# BMS_Slave.net
KiCad netlist of a schematic drawn in Altium Designer
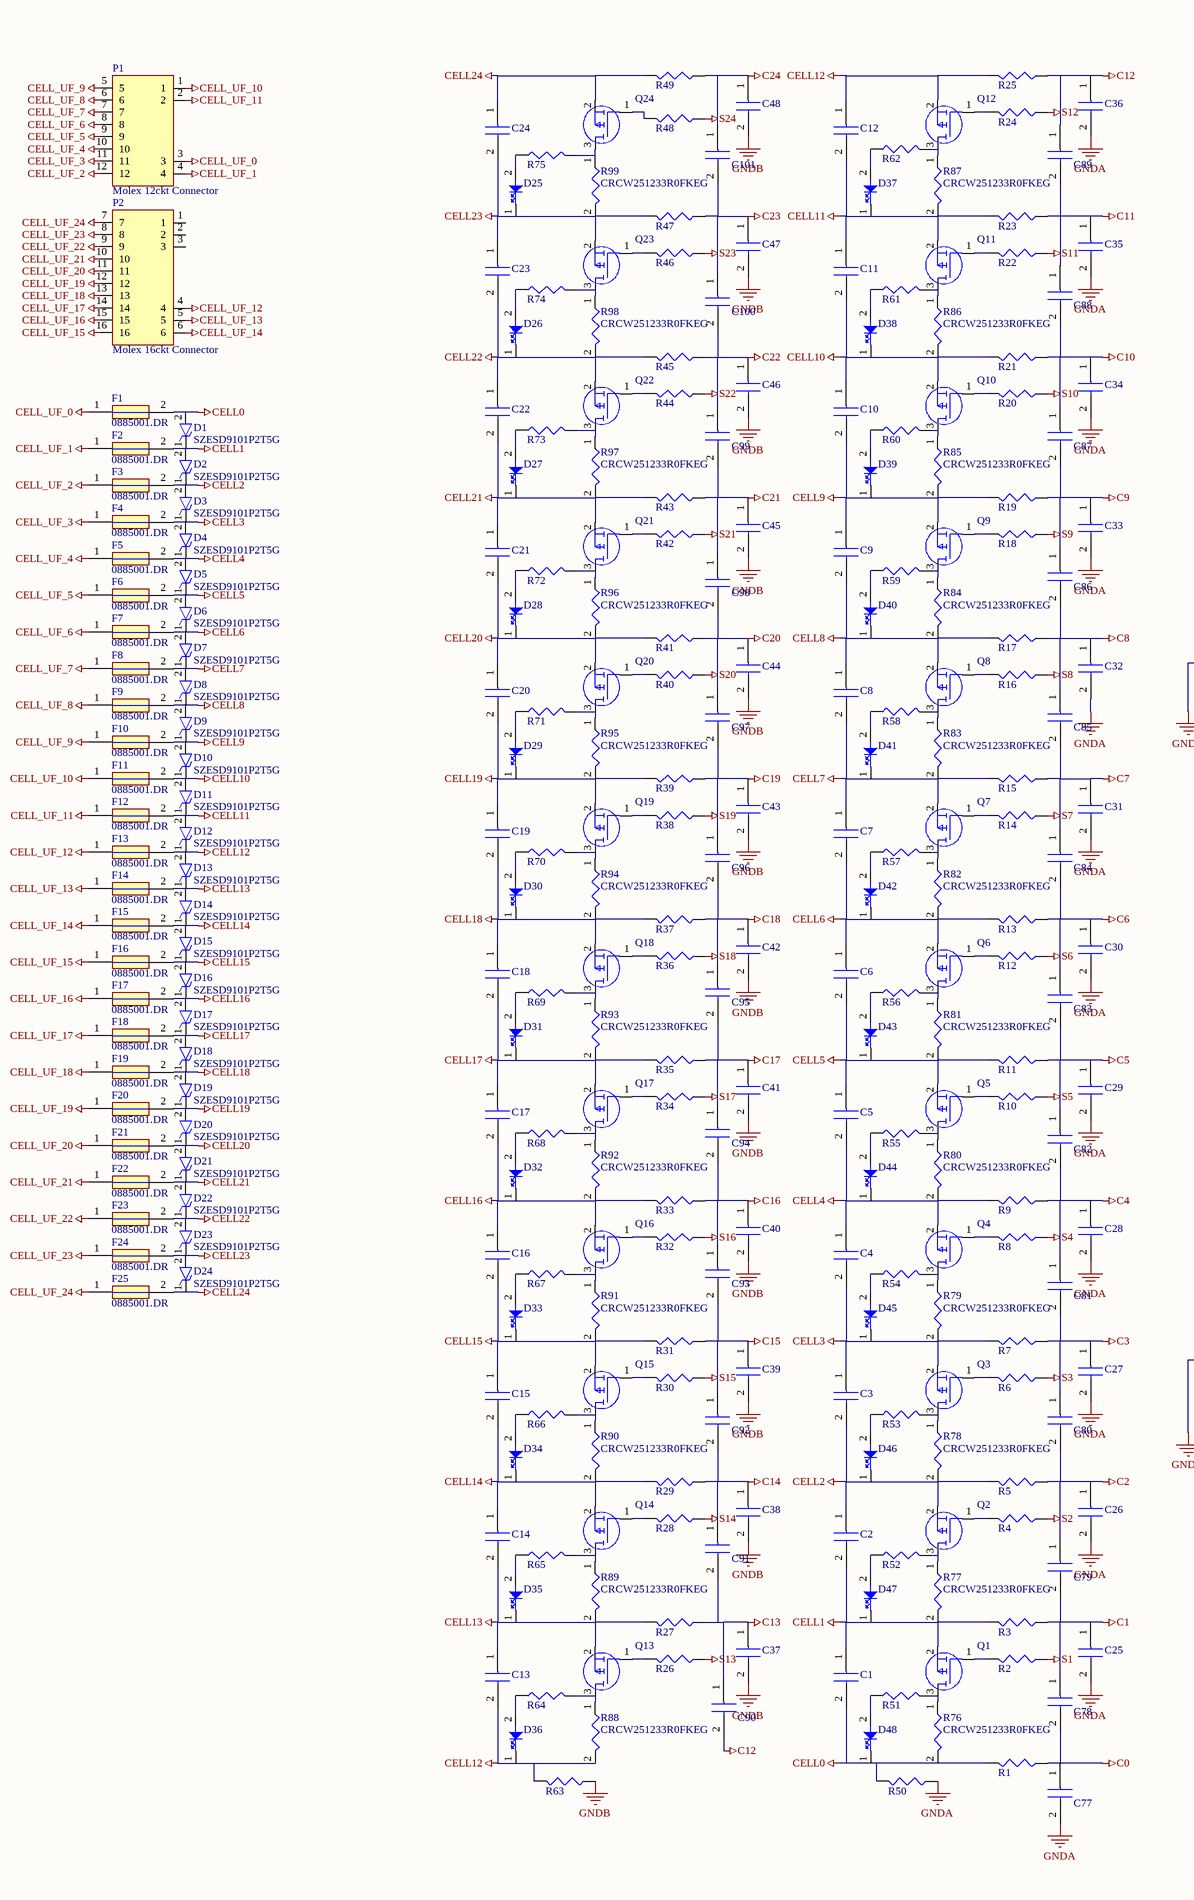
[diagram p0: BMS_Slave.SchDoc, left]
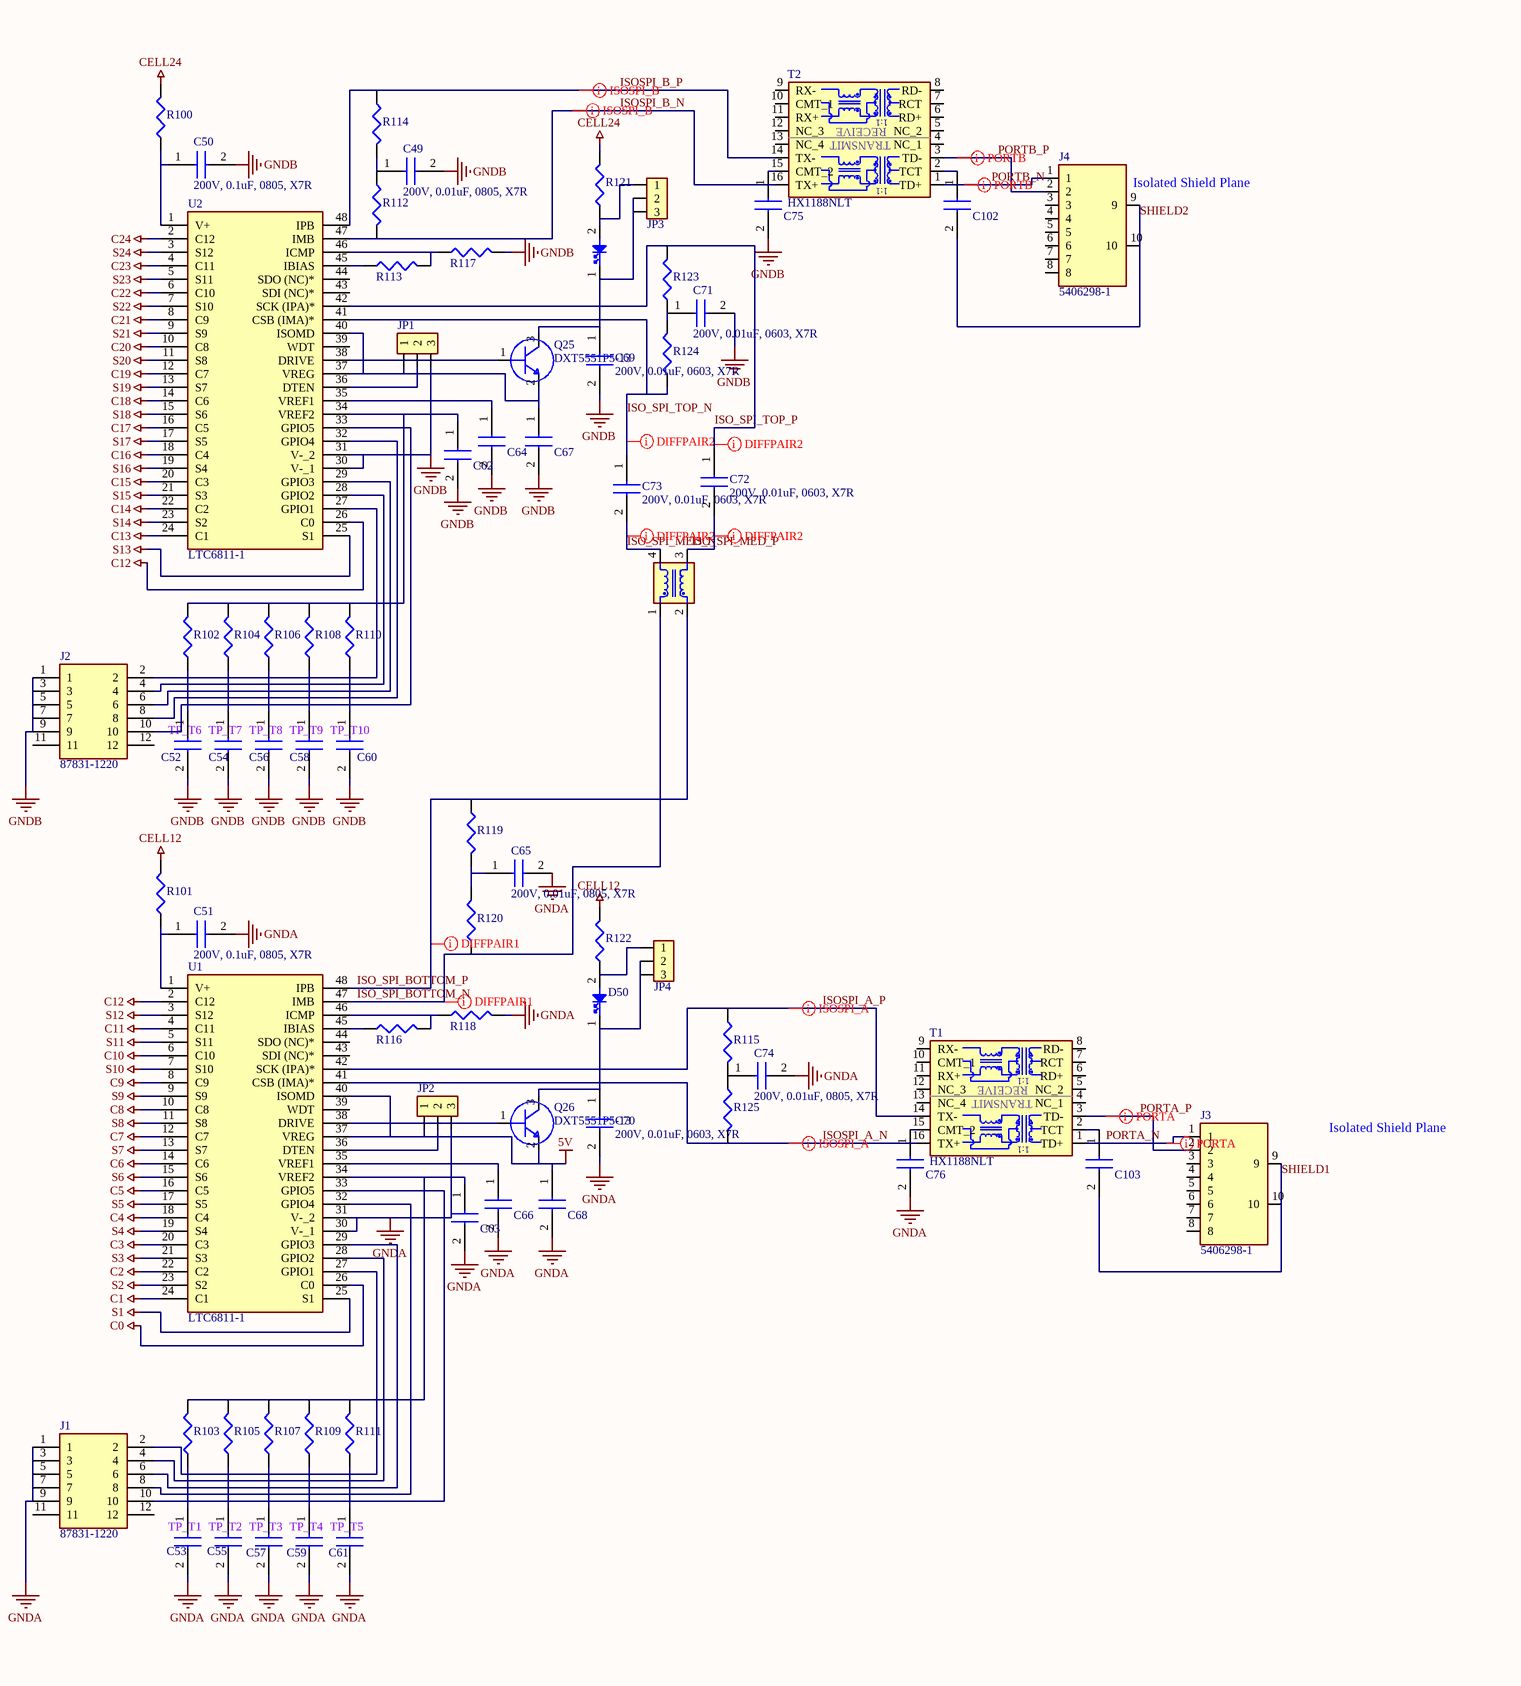
[diagram p1: BMS_Slave.SchDoc, right]

(export (version "E")
  (design (tool "Eeschema 10.0.6"))
  (components
    (comp (ref "C1")
      (value "25V 0.1uF X7R 0805 10%, MLCC")
      (footprint "CAPC2012X88N")
      (fields
        (field (name "MANUFACTURER_PART_NUMBER") "C0805C103K2RACTU")
        (field (name "MOUSER PART NUMBER") "80-C0805C103K2R")
      )
      (libsource (lib "BMS_Slave") (part "C0805C103K2RACTU"))
    )
    (comp (ref "C2")
      (value "25V 0.1uF X7R 0805 10%, MLCC")
      (footprint "CAPC2012X88N")
      (fields
        (field (name "MANUFACTURER_PART_NUMBER") "C0805C103K2RACTU")
        (field (name "MOUSER PART NUMBER") "80-C0805C103K2R")
      )
      (libsource (lib "BMS_Slave") (part "C0805C103K2RACTU"))
    )
    (comp (ref "C3")
      (value "25V 0.1uF X7R 0805 10%, MLCC")
      (footprint "CAPC2012X88N")
      (fields
        (field (name "MANUFACTURER_PART_NUMBER") "C0805C103K2RACTU")
        (field (name "MOUSER PART NUMBER") "80-C0805C103K2R")
      )
      (libsource (lib "BMS_Slave") (part "C0805C103K2RACTU"))
    )
    (comp (ref "C4")
      (value "25V 0.1uF X7R 0805 10%, MLCC")
      (footprint "CAPC2012X88N")
      (fields
        (field (name "MANUFACTURER_PART_NUMBER") "C0805C103K2RACTU")
        (field (name "MOUSER PART NUMBER") "80-C0805C103K2R")
      )
      (libsource (lib "BMS_Slave") (part "C0805C103K2RACTU"))
    )
    (comp (ref "C5")
      (value "25V 0.1uF X7R 0805 10%, MLCC")
      (footprint "CAPC2012X88N")
      (fields
        (field (name "MANUFACTURER_PART_NUMBER") "C0805C103K2RACTU")
        (field (name "MOUSER PART NUMBER") "80-C0805C103K2R")
      )
      (libsource (lib "BMS_Slave") (part "C0805C103K2RACTU"))
    )
    (comp (ref "C6")
      (value "25V 0.1uF X7R 0805 10%, MLCC")
      (footprint "CAPC2012X88N")
      (fields
        (field (name "MANUFACTURER_PART_NUMBER") "C0805C103K2RACTU")
        (field (name "MOUSER PART NUMBER") "80-C0805C103K2R")
      )
      (libsource (lib "BMS_Slave") (part "C0805C103K2RACTU"))
    )
    (comp (ref "C7")
      (value "25V 0.1uF X7R 0805 10%, MLCC")
      (footprint "CAPC2012X88N")
      (fields
        (field (name "MANUFACTURER_PART_NUMBER") "C0805C103K2RACTU")
        (field (name "MOUSER PART NUMBER") "80-C0805C103K2R")
      )
      (libsource (lib "BMS_Slave") (part "C0805C103K2RACTU"))
    )
    (comp (ref "C8")
      (value "25V 0.1uF X7R 0805 10%, MLCC")
      (footprint "CAPC2012X88N")
      (fields
        (field (name "MANUFACTURER_PART_NUMBER") "C0805C103K2RACTU")
        (field (name "MOUSER PART NUMBER") "80-C0805C103K2R")
      )
      (libsource (lib "BMS_Slave") (part "C0805C103K2RACTU"))
    )
    (comp (ref "C9")
      (value "25V 0.1uF X7R 0805 10%, MLCC")
      (footprint "CAPC2012X88N")
      (fields
        (field (name "MANUFACTURER_PART_NUMBER") "C0805C103K2RACTU")
        (field (name "MOUSER PART NUMBER") "80-C0805C103K2R")
      )
      (libsource (lib "BMS_Slave") (part "C0805C103K2RACTU"))
    )
    (comp (ref "C10")
      (value "25V 0.1uF X7R 0805 10%, MLCC")
      (footprint "CAPC2012X88N")
      (fields
        (field (name "MANUFACTURER_PART_NUMBER") "C0805C103K2RACTU")
        (field (name "MOUSER PART NUMBER") "80-C0805C103K2R")
      )
      (libsource (lib "BMS_Slave") (part "C0805C103K2RACTU"))
    )
    (comp (ref "C11")
      (value "25V 0.1uF X7R 0805 10%, MLCC")
      (footprint "CAPC2012X88N")
      (fields
        (field (name "MANUFACTURER_PART_NUMBER") "C0805C103K2RACTU")
        (field (name "MOUSER PART NUMBER") "80-C0805C103K2R")
      )
      (libsource (lib "BMS_Slave") (part "C0805C103K2RACTU"))
    )
    (comp (ref "C12")
      (value "25V 0.1uF X7R 0805 10%, MLCC")
      (footprint "CAPC2012X88N")
      (fields
        (field (name "MANUFACTURER_PART_NUMBER") "C0805C103K2RACTU")
        (field (name "MOUSER PART NUMBER") "80-C0805C103K2R")
      )
      (libsource (lib "BMS_Slave") (part "C0805C103K2RACTU"))
    )
    (comp (ref "C13")
      (value "25V 0.1uF X7R 0805 10%, MLCC")
      (footprint "CAPC2012X88N")
      (fields
        (field (name "MANUFACTURER_PART_NUMBER") "C0805C103K2RACTU")
        (field (name "MOUSER PART NUMBER") "80-C0805C103K2R")
      )
      (libsource (lib "BMS_Slave") (part "C0805C103K2RACTU"))
    )
    (comp (ref "C14")
      (value "25V 0.1uF X7R 0805 10%, MLCC")
      (footprint "CAPC2012X88N")
      (fields
        (field (name "MANUFACTURER_PART_NUMBER") "C0805C103K2RACTU")
        (field (name "MOUSER PART NUMBER") "80-C0805C103K2R")
      )
      (libsource (lib "BMS_Slave") (part "C0805C103K2RACTU"))
    )
    (comp (ref "C15")
      (value "25V 0.1uF X7R 0805 10%, MLCC")
      (footprint "CAPC2012X88N")
      (fields
        (field (name "MANUFACTURER_PART_NUMBER") "C0805C103K2RACTU")
        (field (name "MOUSER PART NUMBER") "80-C0805C103K2R")
      )
      (libsource (lib "BMS_Slave") (part "C0805C103K2RACTU"))
    )
    (comp (ref "C16")
      (value "25V 0.1uF X7R 0805 10%, MLCC")
      (footprint "CAPC2012X88N")
      (fields
        (field (name "MANUFACTURER_PART_NUMBER") "C0805C103K2RACTU")
        (field (name "MOUSER PART NUMBER") "80-C0805C103K2R")
      )
      (libsource (lib "BMS_Slave") (part "C0805C103K2RACTU"))
    )
    (comp (ref "C17")
      (value "25V 0.1uF X7R 0805 10%, MLCC")
      (footprint "CAPC2012X88N")
      (fields
        (field (name "MANUFACTURER_PART_NUMBER") "C0805C103K2RACTU")
        (field (name "MOUSER PART NUMBER") "80-C0805C103K2R")
      )
      (libsource (lib "BMS_Slave") (part "C0805C103K2RACTU"))
    )
    (comp (ref "C18")
      (value "25V 0.1uF X7R 0805 10%, MLCC")
      (footprint "CAPC2012X88N")
      (fields
        (field (name "MANUFACTURER_PART_NUMBER") "C0805C103K2RACTU")
        (field (name "MOUSER PART NUMBER") "80-C0805C103K2R")
      )
      (libsource (lib "BMS_Slave") (part "C0805C103K2RACTU"))
    )
    (comp (ref "C19")
      (value "25V 0.1uF X7R 0805 10%, MLCC")
      (footprint "CAPC2012X88N")
      (fields
        (field (name "MANUFACTURER_PART_NUMBER") "C0805C103K2RACTU")
        (field (name "MOUSER PART NUMBER") "80-C0805C103K2R")
      )
      (libsource (lib "BMS_Slave") (part "C0805C103K2RACTU"))
    )
    (comp (ref "C20")
      (value "25V 0.1uF X7R 0805 10%, MLCC")
      (footprint "CAPC2012X88N")
      (fields
        (field (name "MANUFACTURER_PART_NUMBER") "C0805C103K2RACTU")
        (field (name "MOUSER PART NUMBER") "80-C0805C103K2R")
      )
      (libsource (lib "BMS_Slave") (part "C0805C103K2RACTU"))
    )
    (comp (ref "C21")
      (value "25V 0.1uF X7R 0805 10%, MLCC")
      (footprint "CAPC2012X88N")
      (fields
        (field (name "MANUFACTURER_PART_NUMBER") "C0805C103K2RACTU")
        (field (name "MOUSER PART NUMBER") "80-C0805C103K2R")
      )
      (libsource (lib "BMS_Slave") (part "C0805C103K2RACTU"))
    )
    (comp (ref "C22")
      (value "25V 0.1uF X7R 0805 10%, MLCC")
      (footprint "CAPC2012X88N")
      (fields
        (field (name "MANUFACTURER_PART_NUMBER") "C0805C103K2RACTU")
        (field (name "MOUSER PART NUMBER") "80-C0805C103K2R")
      )
      (libsource (lib "BMS_Slave") (part "C0805C103K2RACTU"))
    )
    (comp (ref "C23")
      (value "25V 0.1uF X7R 0805 10%, MLCC")
      (footprint "CAPC2012X88N")
      (fields
        (field (name "MANUFACTURER_PART_NUMBER") "C0805C103K2RACTU")
        (field (name "MOUSER PART NUMBER") "80-C0805C103K2R")
      )
      (libsource (lib "BMS_Slave") (part "C0805C103K2RACTU"))
    )
    (comp (ref "C24")
      (value "25V 0.1uF X7R 0805 10%, MLCC")
      (footprint "CAPC2012X88N")
      (fields
        (field (name "MANUFACTURER_PART_NUMBER") "C0805C103K2RACTU")
        (field (name "MOUSER PART NUMBER") "80-C0805C103K2R")
      )
      (libsource (lib "BMS_Slave") (part "C0805C103K2RACTU"))
    )
    (comp (ref "C25")
      (value "200V, 0.01uF, 0805, X7R")
      (footprint "BMS_Slave:CAPC2012X88N")
      (description "Capacitor")
      (fields
        (field (name "MANUFACTURER_PART_NUMBER") "C0805C103K2RACTU")
        (field (name "MOUSER PART NUMBER") "80-C0805C103K2R")
      )
      (libsource (lib "BMS_Slave") (part "C0805C103K2RACTU"))
    )
    (comp (ref "C26")
      (value "200V, 0.01uF, 0805, X7R")
      (footprint "BMS_Slave:CAPC2012X88N")
      (description "Capacitor")
      (fields
        (field (name "MANUFACTURER_PART_NUMBER") "C0805C103K2RACTU")
        (field (name "MOUSER PART NUMBER") "80-C0805C103K2R")
      )
      (libsource (lib "BMS_Slave") (part "C0805C103K2RACTU"))
    )
    (comp (ref "C27")
      (value "200V, 0.01uF, 0805, X7R")
      (footprint "BMS_Slave:CAPC2012X88N")
      (description "Capacitor")
      (fields
        (field (name "MANUFACTURER_PART_NUMBER") "C0805C103K2RACTU")
        (field (name "MOUSER PART NUMBER") "80-C0805C103K2R")
      )
      (libsource (lib "BMS_Slave") (part "C0805C103K2RACTU"))
    )
    (comp (ref "C28")
      (value "200V, 0.01uF, 0805, X7R")
      (footprint "BMS_Slave:CAPC2012X88N")
      (description "Capacitor")
      (fields
        (field (name "MANUFACTURER_PART_NUMBER") "C0805C103K2RACTU")
        (field (name "MOUSER PART NUMBER") "80-C0805C103K2R")
      )
      (libsource (lib "BMS_Slave") (part "C0805C103K2RACTU"))
    )
    (comp (ref "C29")
      (value "200V, 0.01uF, 0805, X7R")
      (footprint "BMS_Slave:CAPC2012X88N")
      (description "Capacitor")
      (fields
        (field (name "MANUFACTURER_PART_NUMBER") "C0805C103K2RACTU")
        (field (name "MOUSER PART NUMBER") "80-C0805C103K2R")
      )
      (libsource (lib "BMS_Slave") (part "C0805C103K2RACTU"))
    )
    (comp (ref "C30")
      (value "200V, 0.01uF, 0805, X7R")
      (footprint "BMS_Slave:CAPC2012X88N")
      (description "Capacitor")
      (fields
        (field (name "MANUFACTURER_PART_NUMBER") "C0805C103K2RACTU")
        (field (name "MOUSER PART NUMBER") "80-C0805C103K2R")
      )
      (libsource (lib "BMS_Slave") (part "C0805C103K2RACTU"))
    )
    (comp (ref "C31")
      (value "200V, 0.01uF, 0805, X7R")
      (footprint "BMS_Slave:CAPC2012X88N")
      (description "Capacitor")
      (fields
        (field (name "MANUFACTURER_PART_NUMBER") "C0805C103K2RACTU")
        (field (name "MOUSER PART NUMBER") "80-C0805C103K2R")
      )
      (libsource (lib "BMS_Slave") (part "C0805C103K2RACTU"))
    )
    (comp (ref "C32")
      (value "200V, 0.01uF, 0805, X7R")
      (footprint "BMS_Slave:CAPC2012X88N")
      (description "Capacitor")
      (fields
        (field (name "MANUFACTURER_PART_NUMBER") "C0805C103K2RACTU")
        (field (name "MOUSER PART NUMBER") "80-C0805C103K2R")
      )
      (libsource (lib "BMS_Slave") (part "C0805C103K2RACTU"))
    )
    (comp (ref "C33")
      (value "200V, 0.01uF, 0805, X7R")
      (footprint "BMS_Slave:CAPC2012X88N")
      (description "Capacitor")
      (fields
        (field (name "MANUFACTURER_PART_NUMBER") "C0805C103K2RACTU")
        (field (name "MOUSER PART NUMBER") "80-C0805C103K2R")
      )
      (libsource (lib "BMS_Slave") (part "C0805C103K2RACTU"))
    )
    (comp (ref "C34")
      (value "200V, 0.01uF, 0805, X7R")
      (footprint "BMS_Slave:CAPC2012X88N")
      (description "Capacitor")
      (fields
        (field (name "MANUFACTURER_PART_NUMBER") "C0805C103K2RACTU")
        (field (name "MOUSER PART NUMBER") "80-C0805C103K2R")
      )
      (libsource (lib "BMS_Slave") (part "C0805C103K2RACTU"))
    )
    (comp (ref "C35")
      (value "200V, 0.01uF, 0805, X7R")
      (footprint "BMS_Slave:CAPC2012X88N")
      (description "Capacitor")
      (fields
        (field (name "MANUFACTURER_PART_NUMBER") "C0805C103K2RACTU")
        (field (name "MOUSER PART NUMBER") "80-C0805C103K2R")
      )
      (libsource (lib "BMS_Slave") (part "C0805C103K2RACTU"))
    )
    (comp (ref "C36")
      (value "200V, 0.01uF, 0805, X7R")
      (footprint "BMS_Slave:CAPC2012X88N")
      (description "Capacitor")
      (fields
        (field (name "MANUFACTURER_PART_NUMBER") "C0805C103K2RACTU")
        (field (name "MOUSER PART NUMBER") "80-C0805C103K2R")
      )
      (libsource (lib "BMS_Slave") (part "C0805C103K2RACTU"))
    )
    (comp (ref "C37")
      (value "200V, 0.01uF, 0805, X7R")
      (footprint "BMS_Slave:CAPC2012X88N")
      (description "Capacitor")
      (fields
        (field (name "MANUFACTURER_PART_NUMBER") "C0805C103K2RACTU")
        (field (name "MOUSER PART NUMBER") "80-C0805C103K2R")
      )
      (libsource (lib "BMS_Slave") (part "C0805C103K2RACTU"))
    )
    (comp (ref "C38")
      (value "200V, 0.01uF, 0805, X7R")
      (footprint "BMS_Slave:CAPC2012X88N")
      (description "Capacitor")
      (fields
        (field (name "MANUFACTURER_PART_NUMBER") "C0805C103K2RACTU")
        (field (name "MOUSER PART NUMBER") "80-C0805C103K2R")
      )
      (libsource (lib "BMS_Slave") (part "C0805C103K2RACTU"))
    )
    (comp (ref "C39")
      (value "200V, 0.01uF, 0805, X7R")
      (footprint "BMS_Slave:CAPC2012X88N")
      (description "Capacitor")
      (fields
        (field (name "MANUFACTURER_PART_NUMBER") "C0805C103K2RACTU")
        (field (name "MOUSER PART NUMBER") "80-C0805C103K2R")
      )
      (libsource (lib "BMS_Slave") (part "C0805C103K2RACTU"))
    )
    (comp (ref "C40")
      (value "200V, 0.01uF, 0805, X7R")
      (footprint "BMS_Slave:CAPC2012X88N")
      (description "Capacitor")
      (fields
        (field (name "MANUFACTURER_PART_NUMBER") "C0805C103K2RACTU")
        (field (name "MOUSER PART NUMBER") "80-C0805C103K2R")
      )
      (libsource (lib "BMS_Slave") (part "C0805C103K2RACTU"))
    )
    (comp (ref "C41")
      (value "200V, 0.01uF, 0805, X7R")
      (footprint "BMS_Slave:CAPC2012X88N")
      (description "Capacitor")
      (fields
        (field (name "MANUFACTURER_PART_NUMBER") "C0805C103K2RACTU")
        (field (name "MOUSER PART NUMBER") "80-C0805C103K2R")
      )
      (libsource (lib "BMS_Slave") (part "C0805C103K2RACTU"))
    )
    (comp (ref "C42")
      (value "200V, 0.01uF, 0805, X7R")
      (footprint "BMS_Slave:CAPC2012X88N")
      (description "Capacitor")
      (fields
        (field (name "MANUFACTURER_PART_NUMBER") "C0805C103K2RACTU")
        (field (name "MOUSER PART NUMBER") "80-C0805C103K2R")
      )
      (libsource (lib "BMS_Slave") (part "C0805C103K2RACTU"))
    )
    (comp (ref "C43")
      (value "200V, 0.01uF, 0805, X7R")
      (footprint "BMS_Slave:CAPC2012X88N")
      (description "Capacitor")
      (fields
        (field (name "MANUFACTURER_PART_NUMBER") "C0805C103K2RACTU")
        (field (name "MOUSER PART NUMBER") "80-C0805C103K2R")
      )
      (libsource (lib "BMS_Slave") (part "C0805C103K2RACTU"))
    )
    (comp (ref "C44")
      (value "200V, 0.01uF, 0805, X7R")
      (footprint "BMS_Slave:CAPC2012X88N")
      (description "Capacitor")
      (fields
        (field (name "MANUFACTURER_PART_NUMBER") "C0805C103K2RACTU")
        (field (name "MOUSER PART NUMBER") "80-C0805C103K2R")
      )
      (libsource (lib "BMS_Slave") (part "C0805C103K2RACTU"))
    )
    (comp (ref "C45")
      (value "200V, 0.01uF, 0805, X7R")
      (footprint "BMS_Slave:CAPC2012X88N")
      (description "Capacitor")
      (fields
        (field (name "MANUFACTURER_PART_NUMBER") "C0805C103K2RACTU")
        (field (name "MOUSER PART NUMBER") "80-C0805C103K2R")
      )
      (libsource (lib "BMS_Slave") (part "C0805C103K2RACTU"))
    )
    (comp (ref "C46")
      (value "200V, 0.01uF, 0805, X7R")
      (footprint "BMS_Slave:CAPC2012X88N")
      (description "Capacitor")
      (fields
        (field (name "MANUFACTURER_PART_NUMBER") "C0805C103K2RACTU")
        (field (name "MOUSER PART NUMBER") "80-C0805C103K2R")
      )
      (libsource (lib "BMS_Slave") (part "C0805C103K2RACTU"))
    )
    (comp (ref "C47")
      (value "200V, 0.01uF, 0805, X7R")
      (footprint "BMS_Slave:CAPC2012X88N")
      (description "Capacitor")
      (fields
        (field (name "MANUFACTURER_PART_NUMBER") "C0805C103K2RACTU")
        (field (name "MOUSER PART NUMBER") "80-C0805C103K2R")
      )
      (libsource (lib "BMS_Slave") (part "C0805C103K2RACTU"))
    )
    (comp (ref "C48")
      (value "200V, 0.01uF, 0805, X7R")
      (footprint "BMS_Slave:CAPC2012X88N")
      (description "Capacitor")
      (fields
        (field (name "MANUFACTURER_PART_NUMBER") "C0805C103K2RACTU")
        (field (name "MOUSER PART NUMBER") "80-C0805C103K2R")
      )
      (libsource (lib "BMS_Slave") (part "C0805C103K2RACTU"))
    )
    (comp (ref "C49")
      (value "200V, 0.01uF, 0805, X7R")
      (footprint "CAPC2012X88N")
      (description "Capacitor")
      (fields
        (field (name "MANUFACTURER_PART_NUMBER") "C0805C103K2RACTU")
        (field (name "MOUSER PART NUMBER") "80-C0805C103K2R")
      )
      (libsource (lib "BMS_Slave") (part "C0805C103K2RACTU"))
    )
    (comp (ref "C50")
      (value "200V, 0.1uF, 0805, X7R")
      (footprint "CAPC2012X88N")
      (description "Capacitor")
      (fields
        (field (name "MANUFACTURER_PART_NUMBER") "C0805C103K2RACTU")
        (field (name "MOUSER PART NUMBER") "80-C0805C103K2R")
      )
      (libsource (lib "BMS_Slave") (part "C0805C103K2RACTU"))
    )
    (comp (ref "C51")
      (value "200V, 0.1uF, 0805, X7R")
      (footprint "CAPC2012X88N")
      (description "Capacitor")
      (fields
        (field (name "MANUFACTURER_PART_NUMBER") "C0805C103K2RACTU")
        (field (name "MOUSER PART NUMBER") "80-C0805C103K2R")
      )
      (libsource (lib "BMS_Slave") (part "C0805C103K2RACTU"))
    )
    (comp (ref "C52")
      (value "CGA3E1X7R1E105K080AC")
      (footprint "BMS_Slave:CAPC1608X90N")
      (description "0603 25V 1uF X7R 10% AEC-Q200")
      (fields
        (field (name "MANUFACTURER_PART_NUMBER") "CGA3E1X7R1C105K080AC")
        (field (name "MOUSER PART NUMBER") "810-CGA3E1X7R1C105AC")
      )
      (libsource (lib "BMS_Slave") (part "CGA3E1X7R1E105K080AC"))
    )
    (comp (ref "C53")
      (value "CGA3E1X7R1E105K080AC")
      (footprint "BMS_Slave:CAPC1608X90N")
      (description "0603 25V 1uF X7R 10% AEC-Q200")
      (fields
        (field (name "MANUFACTURER_PART_NUMBER") "CGA3E1X7R1C105K080AC")
        (field (name "MOUSER PART NUMBER") "810-CGA3E1X7R1C105AC")
      )
      (libsource (lib "BMS_Slave") (part "CGA3E1X7R1E105K080AC"))
    )
    (comp (ref "C54")
      (value "CGA3E1X7R1E105K080AC")
      (footprint "BMS_Slave:CAPC1608X90N")
      (description "0603 25V 1uF X7R 10% AEC-Q200")
      (fields
        (field (name "MANUFACTURER_PART_NUMBER") "CGA3E1X7R1C105K080AC")
        (field (name "MOUSER PART NUMBER") "810-CGA3E1X7R1C105AC")
      )
      (libsource (lib "BMS_Slave") (part "CGA3E1X7R1E105K080AC"))
    )
    (comp (ref "C55")
      (value "CGA3E1X7R1E105K080AC")
      (footprint "BMS_Slave:CAPC1608X90N")
      (description "0603 25V 1uF X7R 10% AEC-Q200")
      (fields
        (field (name "MANUFACTURER_PART_NUMBER") "CGA3E1X7R1C105K080AC")
        (field (name "MOUSER PART NUMBER") "810-CGA3E1X7R1C105AC")
      )
      (libsource (lib "BMS_Slave") (part "CGA3E1X7R1E105K080AC"))
    )
    (comp (ref "C56")
      (value "CGA3E1X7R1E105K080AC")
      (footprint "BMS_Slave:CAPC1608X90N")
      (description "0603 25V 1uF X7R 10% AEC-Q200")
      (fields
        (field (name "MANUFACTURER_PART_NUMBER") "CGA3E1X7R1C105K080AC")
        (field (name "MOUSER PART NUMBER") "810-CGA3E1X7R1C105AC")
      )
      (libsource (lib "BMS_Slave") (part "CGA3E1X7R1E105K080AC"))
    )
    (comp (ref "C57")
      (value "CGA3E1X7R1E105K080AC")
      (footprint "BMS_Slave:CAPC1608X90N")
      (description "0603 25V 1uF X7R 10% AEC-Q200")
      (fields
        (field (name "MANUFACTURER_PART_NUMBER") "CGA3E1X7R1C105K080AC")
        (field (name "MOUSER PART NUMBER") "810-CGA3E1X7R1C105AC")
      )
      (libsource (lib "BMS_Slave") (part "CGA3E1X7R1E105K080AC"))
    )
    (comp (ref "C58")
      (value "CGA3E1X7R1E105K080AC")
      (footprint "BMS_Slave:CAPC1608X90N")
      (description "0603 25V 1uF X7R 10% AEC-Q200")
      (fields
        (field (name "MANUFACTURER_PART_NUMBER") "CGA3E1X7R1C105K080AC")
        (field (name "MOUSER PART NUMBER") "810-CGA3E1X7R1C105AC")
      )
      (libsource (lib "BMS_Slave") (part "CGA3E1X7R1E105K080AC"))
    )
    (comp (ref "C59")
      (value "CGA3E1X7R1E105K080AC")
      (footprint "BMS_Slave:CAPC1608X90N")
      (description "0603 25V 1uF X7R 10% AEC-Q200")
      (fields
        (field (name "MANUFACTURER_PART_NUMBER") "CGA3E1X7R1C105K080AC")
        (field (name "MOUSER PART NUMBER") "810-CGA3E1X7R1C105AC")
      )
      (libsource (lib "BMS_Slave") (part "CGA3E1X7R1E105K080AC"))
    )
    (comp (ref "C60")
      (value "CGA3E1X7R1E105K080AC")
      (footprint "BMS_Slave:CAPC1608X90N")
      (description "0603 25V 1uF X7R 10% AEC-Q200")
      (fields
        (field (name "MANUFACTURER_PART_NUMBER") "CGA3E1X7R1C105K080AC")
        (field (name "MOUSER PART NUMBER") "810-CGA3E1X7R1C105AC")
      )
      (libsource (lib "BMS_Slave") (part "CGA3E1X7R1E105K080AC"))
    )
    (comp (ref "C61")
      (value "CGA3E1X7R1E105K080AC")
      (footprint "BMS_Slave:CAPC1608X90N")
      (description "0603 25V 1uF X7R 10% AEC-Q200")
      (fields
        (field (name "MANUFACTURER_PART_NUMBER") "CGA3E1X7R1C105K080AC")
        (field (name "MOUSER PART NUMBER") "810-CGA3E1X7R1C105AC")
      )
      (libsource (lib "BMS_Slave") (part "CGA3E1X7R1E105K080AC"))
    )
    (comp (ref "C62")
      (value "CGA3E1X7R1E105K080AC")
      (footprint "BMS_Slave:CAPC1608X90N")
      (description "0603 25V 1uF X7R 10% AEC-Q200")
      (fields
        (field (name "MANUFACTURER_PART_NUMBER") "CGA3E1X7R1C105K080AC")
        (field (name "MOUSER PART NUMBER") "810-CGA3E1X7R1C105AC")
      )
      (libsource (lib "BMS_Slave") (part "CGA3E1X7R1E105K080AC"))
    )
    (comp (ref "C63")
      (value "CGA3E1X7R1E105K080AC")
      (footprint "BMS_Slave:CAPC1608X90N")
      (description "0603 25V 1uF X7R 10% AEC-Q200")
      (fields
        (field (name "MANUFACTURER_PART_NUMBER") "CGA3E1X7R1C105K080AC")
        (field (name "MOUSER PART NUMBER") "810-CGA3E1X7R1C105AC")
      )
      (libsource (lib "BMS_Slave") (part "CGA3E1X7R1E105K080AC"))
    )
    (comp (ref "C64")
      (value "CGA3E1X7R1E105K080AC")
      (footprint "BMS_Slave:CAPC1608X90N")
      (description "0603 25V 1uF X7R 10% AEC-Q200")
      (fields
        (field (name "MANUFACTURER_PART_NUMBER") "CGA3E1X7R1C105K080AC")
        (field (name "MOUSER PART NUMBER") "810-CGA3E1X7R1C105AC")
      )
      (libsource (lib "BMS_Slave") (part "CGA3E1X7R1E105K080AC"))
    )
    (comp (ref "C65")
      (value "200V, 0.01uF, 0805, X7R")
      (footprint "CAPC2012X88N")
      (description "Capacitor")
      (fields
        (field (name "MANUFACTURER_PART_NUMBER") "C0805C103K2RACTU")
        (field (name "MOUSER PART NUMBER") "80-C0805C103K2R")
      )
      (libsource (lib "BMS_Slave") (part "C0805C103K2RACTU"))
    )
    (comp (ref "C66")
      (value "CGA3E1X7R1E105K080AC")
      (footprint "BMS_Slave:CAPC1608X90N")
      (description "0603 25V 1uF X7R 10% AEC-Q200")
      (fields
        (field (name "MANUFACTURER_PART_NUMBER") "CGA3E1X7R1C105K080AC")
        (field (name "MOUSER PART NUMBER") "810-CGA3E1X7R1C105AC")
      )
      (libsource (lib "BMS_Slave") (part "CGA3E1X7R1E105K080AC"))
    )
    (comp (ref "C67")
      (value "CGA3E1X7R1E105K080AC")
      (footprint "BMS_Slave:CAPC1608X90N")
      (description "0603 25V 1uF X7R 10% AEC-Q200")
      (fields
        (field (name "MANUFACTURER_PART_NUMBER") "CGA3E1X7R1C105K080AC")
        (field (name "MOUSER PART NUMBER") "810-CGA3E1X7R1C105AC")
      )
      (libsource (lib "BMS_Slave") (part "CGA3E1X7R1E105K080AC"))
    )
    (comp (ref "C68")
      (value "CGA3E1X7R1E105K080AC")
      (footprint "BMS_Slave:CAPC1608X90N")
      (description "0603 25V 1uF X7R 10% AEC-Q200")
      (fields
        (field (name "MANUFACTURER_PART_NUMBER") "CGA3E1X7R1C105K080AC")
        (field (name "MOUSER PART NUMBER") "810-CGA3E1X7R1C105AC")
      )
      (libsource (lib "BMS_Slave") (part "CGA3E1X7R1E105K080AC"))
    )
    (comp (ref "C69")
      (value "200V, 0.01uF, 0603, X7R")
      (footprint "CAPC2012X88N")
      (description "Capacitor")
      (fields
        (field (name "MANUFACTURER_PART_NUMBER") "C0805C103K2RACTU")
        (field (name "MOUSER PART NUMBER") "80-C0805C103K2R")
      )
      (libsource (lib "BMS_Slave") (part "C0805C103K2RACTU"))
    )
    (comp (ref "C70")
      (value "200V, 0.01uF, 0603, X7R")
      (footprint "CAPC2012X88N")
      (description "Capacitor")
      (fields
        (field (name "MANUFACTURER_PART_NUMBER") "C0805C103K2RACTU")
        (field (name "MOUSER PART NUMBER") "80-C0805C103K2R")
      )
      (libsource (lib "BMS_Slave") (part "C0805C103K2RACTU"))
    )
    (comp (ref "C71")
      (value "200V, 0.01uF, 0603, X7R")
      (footprint "CAPC2012X88N")
      (description "Capacitor")
      (fields
        (field (name "MANUFACTURER_PART_NUMBER") "C0805C103K2RACTU")
        (field (name "MOUSER PART NUMBER") "80-C0805C103K2R")
      )
      (libsource (lib "BMS_Slave") (part "C0805C103K2RACTU"))
    )
    (comp (ref "C72")
      (value "200V, 0.01uF, 0603, X7R")
      (footprint "CAPC2012X88N")
      (description "Capacitor")
      (fields
        (field (name "MANUFACTURER_PART_NUMBER") "C0805C103K2RACTU")
        (field (name "MOUSER PART NUMBER") "80-C0805C103K2R")
      )
      (libsource (lib "BMS_Slave") (part "C0805C103K2RACTU"))
    )
    (comp (ref "C73")
      (value "200V, 0.01uF, 0603, X7R")
      (footprint "CAPC2012X88N")
      (description "Capacitor")
      (fields
        (field (name "MANUFACTURER_PART_NUMBER") "C0805C103K2RACTU")
        (field (name "MOUSER PART NUMBER") "80-C0805C103K2R")
      )
      (libsource (lib "BMS_Slave") (part "C0805C103K2RACTU"))
    )
    (comp (ref "C74")
      (value "200V, 0.01uF, 0805, X7R")
      (footprint "CAPC2012X88N")
      (description "Capacitor")
      (fields
        (field (name "MANUFACTURER_PART_NUMBER") "C0805C103K2RACTU")
        (field (name "MOUSER PART NUMBER") "80-C0805C103K2R")
      )
      (libsource (lib "BMS_Slave") (part "C0805C103K2RACTU"))
    )
    (comp (ref "C75")
      (value "200V, 0.01uF, 0603, X7R")
      (footprint "CAPC1608X85N")
      (description "200V, 0.01uF, 0603, X7R, 10%, Capacitor")
      (fields
        (field (name "MANUFACTURER_PART_NUMBER") "C0805X103M2RACAUTO")
        (field (name "MOUSER PART NUMBER") "80-C0805X103M2RAUTO")
      )
      (libsource (lib "BMS_Slave") (part "C0603C103K2RECTU"))
    )
    (comp (ref "C76")
      (value "200V, 0.01uF, 0603, X7R")
      (footprint "CAPC1608X85N")
      (description "200V, 0.01uF, 0603, X7R, 10%, Capacitor")
      (fields
        (field (name "MANUFACTURER_PART_NUMBER") "C0805X103M2RACAUTO")
        (field (name "MOUSER PART NUMBER") "80-C0805X103M2RAUTO")
      )
      (libsource (lib "BMS_Slave") (part "C0603C103K2RECTU_1"))
    )
    (comp (ref "C77")
      (value "200V, 0.01uF, 0603, X7R")
      (footprint "CAPC1608X85N")
      (description "200V, 0.01uF, 0603, X7R, 10%, Capacitor")
      (fields
        (field (name "MANUFACTURER_PART_NUMBER") "C0805X103M2RACAUTO")
        (field (name "MOUSER PART NUMBER") "80-C0805X103M2RAUTO")
      )
      (libsource (lib "BMS_Slave") (part "C0603C103K2RECTU"))
    )
    (comp (ref "C78")
      (value "200V, 0.01uF, 0603, X7R")
      (footprint "CAPC1608X85N")
      (description "200V, 0.01uF, 0603, X7R, 10%, Capacitor")
      (fields
        (field (name "MANUFACTURER_PART_NUMBER") "C0805X103M2RACAUTO")
        (field (name "MOUSER PART NUMBER") "80-C0805X103M2RAUTO")
      )
      (libsource (lib "BMS_Slave") (part "C0603C103K2RECTU"))
    )
    (comp (ref "C79")
      (value "200V, 0.01uF, 0603, X7R")
      (footprint "CAPC1608X85N")
      (description "200V, 0.01uF, 0603, X7R, 10%, Capacitor")
      (fields
        (field (name "MANUFACTURER_PART_NUMBER") "C0805X103M2RACAUTO")
        (field (name "MOUSER PART NUMBER") "80-C0805X103M2RAUTO")
      )
      (libsource (lib "BMS_Slave") (part "C0603C103K2RECTU"))
    )
    (comp (ref "C80")
      (value "200V, 0.01uF, 0603, X7R")
      (footprint "CAPC1608X85N")
      (description "200V, 0.01uF, 0603, X7R, 10%, Capacitor")
      (fields
        (field (name "MANUFACTURER_PART_NUMBER") "C0805X103M2RACAUTO")
        (field (name "MOUSER PART NUMBER") "80-C0805X103M2RAUTO")
      )
      (libsource (lib "BMS_Slave") (part "C0603C103K2RECTU"))
    )
    (comp (ref "C81")
      (value "200V, 0.01uF, 0603, X7R")
      (footprint "CAPC1608X85N")
      (description "200V, 0.01uF, 0603, X7R, 10%, Capacitor")
      (fields
        (field (name "MANUFACTURER_PART_NUMBER") "C0805X103M2RACAUTO")
        (field (name "MOUSER PART NUMBER") "80-C0805X103M2RAUTO")
      )
      (libsource (lib "BMS_Slave") (part "C0603C103K2RECTU"))
    )
    (comp (ref "C82")
      (value "200V, 0.01uF, 0603, X7R")
      (footprint "CAPC1608X85N")
      (description "200V, 0.01uF, 0603, X7R, 10%, Capacitor")
      (fields
        (field (name "MANUFACTURER_PART_NUMBER") "C0805X103M2RACAUTO")
        (field (name "MOUSER PART NUMBER") "80-C0805X103M2RAUTO")
      )
      (libsource (lib "BMS_Slave") (part "C0603C103K2RECTU"))
    )
    (comp (ref "C83")
      (value "200V, 0.01uF, 0603, X7R")
      (footprint "CAPC1608X85N")
      (description "200V, 0.01uF, 0603, X7R, 10%, Capacitor")
      (fields
        (field (name "MANUFACTURER_PART_NUMBER") "C0805X103M2RACAUTO")
        (field (name "MOUSER PART NUMBER") "80-C0805X103M2RAUTO")
      )
      (libsource (lib "BMS_Slave") (part "C0603C103K2RECTU"))
    )
    (comp (ref "C84")
      (value "200V, 0.01uF, 0603, X7R")
      (footprint "CAPC1608X85N")
      (description "200V, 0.01uF, 0603, X7R, 10%, Capacitor")
      (fields
        (field (name "MANUFACTURER_PART_NUMBER") "C0805X103M2RACAUTO")
        (field (name "MOUSER PART NUMBER") "80-C0805X103M2RAUTO")
      )
      (libsource (lib "BMS_Slave") (part "C0603C103K2RECTU"))
    )
    (comp (ref "C85")
      (value "200V, 0.01uF, 0603, X7R")
      (footprint "CAPC1608X85N")
      (description "200V, 0.01uF, 0603, X7R, 10%, Capacitor")
      (fields
        (field (name "MANUFACTURER_PART_NUMBER") "C0805X103M2RACAUTO")
        (field (name "MOUSER PART NUMBER") "80-C0805X103M2RAUTO")
      )
      (libsource (lib "BMS_Slave") (part "C0603C103K2RECTU"))
    )
    (comp (ref "C86")
      (value "200V, 0.01uF, 0603, X7R")
      (footprint "CAPC1608X85N")
      (description "200V, 0.01uF, 0603, X7R, 10%, Capacitor")
      (fields
        (field (name "MANUFACTURER_PART_NUMBER") "C0805X103M2RACAUTO")
        (field (name "MOUSER PART NUMBER") "80-C0805X103M2RAUTO")
      )
      (libsource (lib "BMS_Slave") (part "C0603C103K2RECTU"))
    )
    (comp (ref "C87")
      (value "200V, 0.01uF, 0603, X7R")
      (footprint "CAPC1608X85N")
      (description "200V, 0.01uF, 0603, X7R, 10%, Capacitor")
      (fields
        (field (name "MANUFACTURER_PART_NUMBER") "C0805X103M2RACAUTO")
        (field (name "MOUSER PART NUMBER") "80-C0805X103M2RAUTO")
      )
      (libsource (lib "BMS_Slave") (part "C0603C103K2RECTU"))
    )
    (comp (ref "C88")
      (value "200V, 0.01uF, 0603, X7R")
      (footprint "CAPC1608X85N")
      (description "200V, 0.01uF, 0603, X7R, 10%, Capacitor")
      (fields
        (field (name "MANUFACTURER_PART_NUMBER") "C0805X103M2RACAUTO")
        (field (name "MOUSER PART NUMBER") "80-C0805X103M2RAUTO")
      )
      (libsource (lib "BMS_Slave") (part "C0603C103K2RECTU"))
    )
    (comp (ref "C89")
      (value "200V, 0.01uF, 0603, X7R")
      (footprint "CAPC1608X85N")
      (description "200V, 0.01uF, 0603, X7R, 10%, Capacitor")
      (fields
        (field (name "MANUFACTURER_PART_NUMBER") "C0805X103M2RACAUTO")
        (field (name "MOUSER PART NUMBER") "80-C0805X103M2RAUTO")
      )
      (libsource (lib "BMS_Slave") (part "C0603C103K2RECTU"))
    )
    (comp (ref "C90")
      (value "200V, 0.01uF, 0603, X7R")
      (footprint "CAPC1608X85N")
      (description "200V, 0.01uF, 0603, X7R, 10%, Capacitor")
      (fields
        (field (name "MANUFACTURER_PART_NUMBER") "C0805X103M2RACAUTO")
        (field (name "MOUSER PART NUMBER") "80-C0805X103M2RAUTO")
      )
      (libsource (lib "BMS_Slave") (part "C0603C103K2RECTU"))
    )
    (comp (ref "C91")
      (value "200V, 0.01uF, 0603, X7R")
      (footprint "CAPC1608X85N")
      (description "200V, 0.01uF, 0603, X7R, 10%, Capacitor")
      (fields
        (field (name "MANUFACTURER_PART_NUMBER") "C0805X103M2RACAUTO")
        (field (name "MOUSER PART NUMBER") "80-C0805X103M2RAUTO")
      )
      (libsource (lib "BMS_Slave") (part "C0603C103K2RECTU"))
    )
    (comp (ref "C92")
      (value "200V, 0.01uF, 0603, X7R")
      (footprint "CAPC1608X85N")
      (description "200V, 0.01uF, 0603, X7R, 10%, Capacitor")
      (fields
        (field (name "MANUFACTURER_PART_NUMBER") "C0805X103M2RACAUTO")
        (field (name "MOUSER PART NUMBER") "80-C0805X103M2RAUTO")
      )
      (libsource (lib "BMS_Slave") (part "C0603C103K2RECTU"))
    )
    (comp (ref "C93")
      (value "200V, 0.01uF, 0603, X7R")
      (footprint "CAPC1608X85N")
      (description "200V, 0.01uF, 0603, X7R, 10%, Capacitor")
      (fields
        (field (name "MANUFACTURER_PART_NUMBER") "C0805X103M2RACAUTO")
        (field (name "MOUSER PART NUMBER") "80-C0805X103M2RAUTO")
      )
      (libsource (lib "BMS_Slave") (part "C0603C103K2RECTU"))
    )
    (comp (ref "C94")
      (value "200V, 0.01uF, 0603, X7R")
      (footprint "CAPC1608X85N")
      (description "200V, 0.01uF, 0603, X7R, 10%, Capacitor")
      (fields
        (field (name "MANUFACTURER_PART_NUMBER") "C0805X103M2RACAUTO")
        (field (name "MOUSER PART NUMBER") "80-C0805X103M2RAUTO")
      )
      (libsource (lib "BMS_Slave") (part "C0603C103K2RECTU"))
    )
    (comp (ref "C95")
      (value "200V, 0.01uF, 0603, X7R")
      (footprint "CAPC1608X85N")
      (description "200V, 0.01uF, 0603, X7R, 10%, Capacitor")
      (fields
        (field (name "MANUFACTURER_PART_NUMBER") "C0805X103M2RACAUTO")
        (field (name "MOUSER PART NUMBER") "80-C0805X103M2RAUTO")
      )
      (libsource (lib "BMS_Slave") (part "C0603C103K2RECTU"))
    )
    (comp (ref "C96")
      (value "200V, 0.01uF, 0603, X7R")
      (footprint "CAPC1608X85N")
      (description "200V, 0.01uF, 0603, X7R, 10%, Capacitor")
      (fields
        (field (name "MANUFACTURER_PART_NUMBER") "C0805X103M2RACAUTO")
        (field (name "MOUSER PART NUMBER") "80-C0805X103M2RAUTO")
      )
      (libsource (lib "BMS_Slave") (part "C0603C103K2RECTU"))
    )
    (comp (ref "C97")
      (value "200V, 0.01uF, 0603, X7R")
      (footprint "CAPC1608X85N")
      (description "200V, 0.01uF, 0603, X7R, 10%, Capacitor")
      (fields
        (field (name "MANUFACTURER_PART_NUMBER") "C0805X103M2RACAUTO")
        (field (name "MOUSER PART NUMBER") "80-C0805X103M2RAUTO")
      )
      (libsource (lib "BMS_Slave") (part "C0603C103K2RECTU"))
    )
    (comp (ref "C98")
      (value "200V, 0.01uF, 0603, X7R")
      (footprint "CAPC1608X85N")
      (description "200V, 0.01uF, 0603, X7R, 10%, Capacitor")
      (fields
        (field (name "MANUFACTURER_PART_NUMBER") "C0805X103M2RACAUTO")
        (field (name "MOUSER PART NUMBER") "80-C0805X103M2RAUTO")
      )
      (libsource (lib "BMS_Slave") (part "C0603C103K2RECTU"))
    )
    (comp (ref "C99")
      (value "200V, 0.01uF, 0603, X7R")
      (footprint "CAPC1608X85N")
      (description "200V, 0.01uF, 0603, X7R, 10%, Capacitor")
      (fields
        (field (name "MANUFACTURER_PART_NUMBER") "C0805X103M2RACAUTO")
        (field (name "MOUSER PART NUMBER") "80-C0805X103M2RAUTO")
      )
      (libsource (lib "BMS_Slave") (part "C0603C103K2RECTU"))
    )
    (comp (ref "C100")
      (value "200V, 0.01uF, 0603, X7R")
      (footprint "CAPC1608X85N")
      (description "200V, 0.01uF, 0603, X7R, 10%, Capacitor")
      (fields
        (field (name "MANUFACTURER_PART_NUMBER") "C0805X103M2RACAUTO")
        (field (name "MOUSER PART NUMBER") "80-C0805X103M2RAUTO")
      )
      (libsource (lib "BMS_Slave") (part "C0603C103K2RECTU"))
    )
    (comp (ref "C101")
      (value "200V, 0.01uF, 0603, X7R")
      (footprint "CAPC1608X85N")
      (description "200V, 0.01uF, 0603, X7R, 10%, Capacitor")
      (fields
        (field (name "MANUFACTURER_PART_NUMBER") "C0805X103M2RACAUTO")
        (field (name "MOUSER PART NUMBER") "80-C0805X103M2RAUTO")
      )
      (libsource (lib "BMS_Slave") (part "C0603C103K2RECTU"))
    )
    (comp (ref "C102")
      (value "200V, 0.01uF, 0603, X7R")
      (footprint "CAPC1608X85N")
      (description "200V, 0.01uF, 0603, X7R, 10%, Capacitor")
      (fields
        (field (name "MANUFACTURER_PART_NUMBER") "C0805X103M2RACAUTO")
        (field (name "MOUSER PART NUMBER") "80-C0805X103M2RAUTO")
      )
      (libsource (lib "BMS_Slave") (part "C0603C103K2RECTU"))
    )
    (comp (ref "C103")
      (value "200V, 0.01uF, 0603, X7R")
      (footprint "CAPC1608X85N")
      (description "200V, 0.01uF, 0603, X7R, 10%, Capacitor")
      (fields
        (field (name "MANUFACTURER_PART_NUMBER") "C0805X103M2RACAUTO")
        (field (name "MOUSER PART NUMBER") "80-C0805X103M2RAUTO")
      )
      (libsource (lib "BMS_Slave") (part "C0603C103K2RECTU"))
    )
    (comp (ref "D1")
      (value "SZESD9101P2T5G")
      (footprint "SODFL1006X40N")
      (description "TVS Diode (Uni-directional)")
      (fields (field (name "MOUSER PART NUMBER") "863-SZESD9101P2T5G"))
      (libsource (lib "BMS_Slave") (part "SZESD9101P2T5G"))
    )
    (comp (ref "D2")
      (value "SZESD9101P2T5G")
      (footprint "SODFL1006X40N")
      (description "TVS Diode (Uni-directional)")
      (fields (field (name "MOUSER PART NUMBER") "863-SZESD9101P2T5G"))
      (libsource (lib "BMS_Slave") (part "SZESD9101P2T5G"))
    )
    (comp (ref "D3")
      (value "SZESD9101P2T5G")
      (footprint "SODFL1006X40N")
      (description "TVS Diode (Uni-directional)")
      (fields (field (name "MOUSER PART NUMBER") "863-SZESD9101P2T5G"))
      (libsource (lib "BMS_Slave") (part "SZESD9101P2T5G"))
    )
    (comp (ref "D4")
      (value "SZESD9101P2T5G")
      (footprint "SODFL1006X40N")
      (description "TVS Diode (Uni-directional)")
      (fields (field (name "MOUSER PART NUMBER") "863-SZESD9101P2T5G"))
      (libsource (lib "BMS_Slave") (part "SZESD9101P2T5G"))
    )
    (comp (ref "D5")
      (value "SZESD9101P2T5G")
      (footprint "SODFL1006X40N")
      (description "TVS Diode (Uni-directional)")
      (fields (field (name "MOUSER PART NUMBER") "863-SZESD9101P2T5G"))
      (libsource (lib "BMS_Slave") (part "SZESD9101P2T5G"))
    )
    (comp (ref "D6")
      (value "SZESD9101P2T5G")
      (footprint "SODFL1006X40N")
      (description "TVS Diode (Uni-directional)")
      (fields (field (name "MOUSER PART NUMBER") "863-SZESD9101P2T5G"))
      (libsource (lib "BMS_Slave") (part "SZESD9101P2T5G"))
    )
    (comp (ref "D7")
      (value "SZESD9101P2T5G")
      (footprint "SODFL1006X40N")
      (description "TVS Diode (Uni-directional)")
      (fields (field (name "MOUSER PART NUMBER") "863-SZESD9101P2T5G"))
      (libsource (lib "BMS_Slave") (part "SZESD9101P2T5G"))
    )
    (comp (ref "D8")
      (value "SZESD9101P2T5G")
      (footprint "SODFL1006X40N")
      (description "TVS Diode (Uni-directional)")
      (fields (field (name "MOUSER PART NUMBER") "863-SZESD9101P2T5G"))
      (libsource (lib "BMS_Slave") (part "SZESD9101P2T5G"))
    )
    (comp (ref "D9")
      (value "SZESD9101P2T5G")
      (footprint "SODFL1006X40N")
      (description "TVS Diode (Uni-directional)")
      (fields (field (name "MOUSER PART NUMBER") "863-SZESD9101P2T5G"))
      (libsource (lib "BMS_Slave") (part "SZESD9101P2T5G"))
    )
    (comp (ref "D10")
      (value "SZESD9101P2T5G")
      (footprint "SODFL1006X40N")
      (description "TVS Diode (Uni-directional)")
      (fields (field (name "MOUSER PART NUMBER") "863-SZESD9101P2T5G"))
      (libsource (lib "BMS_Slave") (part "SZESD9101P2T5G"))
    )
    (comp (ref "D11")
      (value "SZESD9101P2T5G")
      (footprint "SODFL1006X40N")
      (description "TVS Diode (Uni-directional)")
      (fields (field (name "MOUSER PART NUMBER") "863-SZESD9101P2T5G"))
      (libsource (lib "BMS_Slave") (part "SZESD9101P2T5G"))
    )
    (comp (ref "D12")
      (value "SZESD9101P2T5G")
      (footprint "SODFL1006X40N")
      (description "TVS Diode (Uni-directional)")
      (fields (field (name "MOUSER PART NUMBER") "863-SZESD9101P2T5G"))
      (libsource (lib "BMS_Slave") (part "SZESD9101P2T5G"))
    )
    (comp (ref "D13")
      (value "SZESD9101P2T5G")
      (footprint "SODFL1006X40N")
      (description "TVS Diode (Uni-directional)")
      (fields (field (name "MOUSER PART NUMBER") "863-SZESD9101P2T5G"))
      (libsource (lib "BMS_Slave") (part "SZESD9101P2T5G"))
    )
    (comp (ref "D14")
      (value "SZESD9101P2T5G")
      (footprint "SODFL1006X40N")
      (description "TVS Diode (Uni-directional)")
      (fields (field (name "MOUSER PART NUMBER") "863-SZESD9101P2T5G"))
      (libsource (lib "BMS_Slave") (part "SZESD9101P2T5G"))
    )
    (comp (ref "D15")
      (value "SZESD9101P2T5G")
      (footprint "SODFL1006X40N")
      (description "TVS Diode (Uni-directional)")
      (fields (field (name "MOUSER PART NUMBER") "863-SZESD9101P2T5G"))
      (libsource (lib "BMS_Slave") (part "SZESD9101P2T5G"))
    )
    (comp (ref "D16")
      (value "SZESD9101P2T5G")
      (footprint "SODFL1006X40N")
      (description "TVS Diode (Uni-directional)")
      (fields (field (name "MOUSER PART NUMBER") "863-SZESD9101P2T5G"))
      (libsource (lib "BMS_Slave") (part "SZESD9101P2T5G"))
    )
    (comp (ref "D17")
      (value "SZESD9101P2T5G")
      (footprint "SODFL1006X40N")
      (description "TVS Diode (Uni-directional)")
      (fields (field (name "MOUSER PART NUMBER") "863-SZESD9101P2T5G"))
      (libsource (lib "BMS_Slave") (part "SZESD9101P2T5G"))
    )
    (comp (ref "D18")
      (value "SZESD9101P2T5G")
      (footprint "SODFL1006X40N")
      (description "TVS Diode (Uni-directional)")
      (fields (field (name "MOUSER PART NUMBER") "863-SZESD9101P2T5G"))
      (libsource (lib "BMS_Slave") (part "SZESD9101P2T5G"))
    )
    (comp (ref "D19")
      (value "SZESD9101P2T5G")
      (footprint "SODFL1006X40N")
      (description "TVS Diode (Uni-directional)")
      (fields (field (name "MOUSER PART NUMBER") "863-SZESD9101P2T5G"))
      (libsource (lib "BMS_Slave") (part "SZESD9101P2T5G"))
    )
    (comp (ref "D20")
      (value "SZESD9101P2T5G")
      (footprint "SODFL1006X40N")
      (description "TVS Diode (Uni-directional)")
      (fields (field (name "MOUSER PART NUMBER") "863-SZESD9101P2T5G"))
      (libsource (lib "BMS_Slave") (part "SZESD9101P2T5G"))
    )
    (comp (ref "D21")
      (value "SZESD9101P2T5G")
      (footprint "SODFL1006X40N")
      (description "TVS Diode (Uni-directional)")
      (fields (field (name "MOUSER PART NUMBER") "863-SZESD9101P2T5G"))
      (libsource (lib "BMS_Slave") (part "SZESD9101P2T5G"))
    )
    (comp (ref "D22")
      (value "SZESD9101P2T5G")
      (footprint "SODFL1006X40N")
      (description "TVS Diode (Uni-directional)")
      (fields (field (name "MOUSER PART NUMBER") "863-SZESD9101P2T5G"))
      (libsource (lib "BMS_Slave") (part "SZESD9101P2T5G"))
    )
    (comp (ref "D23")
      (value "SZESD9101P2T5G")
      (footprint "SODFL1006X40N")
      (description "TVS Diode (Uni-directional)")
      (fields (field (name "MOUSER PART NUMBER") "863-SZESD9101P2T5G"))
      (libsource (lib "BMS_Slave") (part "SZESD9101P2T5G"))
    )
    (comp (ref "D24")
      (value "SZESD9101P2T5G")
      (footprint "SODFL1006X40N")
      (description "TVS Diode (Uni-directional)")
      (fields (field (name "MOUSER PART NUMBER") "863-SZESD9101P2T5G"))
      (libsource (lib "BMS_Slave") (part "SZESD9101P2T5G"))
    )
    (comp (ref "D25")
      (value "SML-210VTT86")
      (footprint "SamacSys:LEDC2012X80N")
      (description "LED")
      (fields
        (field (name "MOUSER PART NUMBER") "755-SML-210VTT86")
        (field (name "RS PART NUMBER") "7007893P")
      )
      (libsource (lib "BMS_Slave") (part "SML-210VTT86"))
    )
    (comp (ref "D26")
      (value "SML-210VTT86")
      (footprint "SamacSys:LEDC2012X80N")
      (description "LED")
      (fields
        (field (name "MOUSER PART NUMBER") "755-SML-210VTT86")
        (field (name "RS PART NUMBER") "7007893P")
      )
      (libsource (lib "BMS_Slave") (part "SML-210VTT86"))
    )
    (comp (ref "D27")
      (value "SML-210VTT86")
      (footprint "SamacSys:LEDC2012X80N")
      (description "LED")
      (fields
        (field (name "MOUSER PART NUMBER") "755-SML-210VTT86")
        (field (name "RS PART NUMBER") "7007893P")
      )
      (libsource (lib "BMS_Slave") (part "SML-210VTT86"))
    )
    (comp (ref "D28")
      (value "SML-210VTT86")
      (footprint "SamacSys:LEDC2012X80N")
      (description "LED")
      (fields
        (field (name "MOUSER PART NUMBER") "755-SML-210VTT86")
        (field (name "RS PART NUMBER") "7007893P")
      )
      (libsource (lib "BMS_Slave") (part "SML-210VTT86"))
    )
    (comp (ref "D29")
      (value "SML-210VTT86")
      (footprint "SamacSys:LEDC2012X80N")
      (description "LED")
      (fields
        (field (name "MOUSER PART NUMBER") "755-SML-210VTT86")
        (field (name "RS PART NUMBER") "7007893P")
      )
      (libsource (lib "BMS_Slave") (part "SML-210VTT86"))
    )
    (comp (ref "D30")
      (value "SML-210VTT86")
      (footprint "SamacSys:LEDC2012X80N")
      (description "LED")
      (fields
        (field (name "MOUSER PART NUMBER") "755-SML-210VTT86")
        (field (name "RS PART NUMBER") "7007893P")
      )
      (libsource (lib "BMS_Slave") (part "SML-210VTT86"))
    )
    (comp (ref "D31")
      (value "SML-210VTT86")
      (footprint "SamacSys:LEDC2012X80N")
      (description "LED")
      (fields
        (field (name "MOUSER PART NUMBER") "755-SML-210VTT86")
        (field (name "RS PART NUMBER") "7007893P")
      )
      (libsource (lib "BMS_Slave") (part "SML-210VTT86"))
    )
    (comp (ref "D32")
      (value "SML-210VTT86")
      (footprint "SamacSys:LEDC2012X80N")
      (description "LED")
      (fields
        (field (name "MOUSER PART NUMBER") "755-SML-210VTT86")
        (field (name "RS PART NUMBER") "7007893P")
      )
      (libsource (lib "BMS_Slave") (part "SML-210VTT86"))
    )
    (comp (ref "D33")
      (value "SML-210VTT86")
      (footprint "SamacSys:LEDC2012X80N")
      (description "LED")
      (fields
        (field (name "MOUSER PART NUMBER") "755-SML-210VTT86")
        (field (name "RS PART NUMBER") "7007893P")
      )
      (libsource (lib "BMS_Slave") (part "SML-210VTT86"))
    )
    (comp (ref "D34")
      (value "SML-210VTT86")
      (footprint "SamacSys:LEDC2012X80N")
      (description "LED")
      (fields
        (field (name "MOUSER PART NUMBER") "755-SML-210VTT86")
        (field (name "RS PART NUMBER") "7007893P")
      )
      (libsource (lib "BMS_Slave") (part "SML-210VTT86"))
    )
    (comp (ref "D35")
      (value "SML-210VTT86")
      (footprint "SamacSys:LEDC2012X80N")
      (description "LED")
      (fields
        (field (name "MOUSER PART NUMBER") "755-SML-210VTT86")
        (field (name "RS PART NUMBER") "7007893P")
      )
      (libsource (lib "BMS_Slave") (part "SML-210VTT86"))
    )
    (comp (ref "D36")
      (value "SML-210VTT86")
      (footprint "SamacSys:LEDC2012X80N")
      (description "LED")
      (fields
        (field (name "MOUSER PART NUMBER") "755-SML-210VTT86")
        (field (name "RS PART NUMBER") "7007893P")
      )
      (libsource (lib "BMS_Slave") (part "SML-210VTT86"))
    )
    (comp (ref "D37")
      (value "SML-210VTT86")
      (footprint "SamacSys:LEDC2012X80N")
      (description "LED")
      (fields
        (field (name "MOUSER PART NUMBER") "755-SML-210VTT86")
        (field (name "RS PART NUMBER") "7007893P")
      )
      (libsource (lib "BMS_Slave") (part "SML-210VTT86"))
    )
    (comp (ref "D38")
      (value "SML-210VTT86")
      (footprint "SamacSys:LEDC2012X80N")
      (description "LED")
      (fields
        (field (name "MOUSER PART NUMBER") "755-SML-210VTT86")
        (field (name "RS PART NUMBER") "7007893P")
      )
      (libsource (lib "BMS_Slave") (part "SML-210VTT86"))
    )
    (comp (ref "D39")
      (value "SML-210VTT86")
      (footprint "SamacSys:LEDC2012X80N")
      (description "LED")
      (fields
        (field (name "MOUSER PART NUMBER") "755-SML-210VTT86")
        (field (name "RS PART NUMBER") "7007893P")
      )
      (libsource (lib "BMS_Slave") (part "SML-210VTT86"))
    )
    (comp (ref "D40")
      (value "SML-210VTT86")
      (footprint "SamacSys:LEDC2012X80N")
      (description "LED")
      (fields
        (field (name "MOUSER PART NUMBER") "755-SML-210VTT86")
        (field (name "RS PART NUMBER") "7007893P")
      )
      (libsource (lib "BMS_Slave") (part "SML-210VTT86"))
    )
    (comp (ref "D41")
      (value "SML-210VTT86")
      (footprint "SamacSys:LEDC2012X80N")
      (description "LED")
      (fields
        (field (name "MOUSER PART NUMBER") "755-SML-210VTT86")
        (field (name "RS PART NUMBER") "7007893P")
      )
      (libsource (lib "BMS_Slave") (part "SML-210VTT86"))
    )
    (comp (ref "D42")
      (value "SML-210VTT86")
      (footprint "SamacSys:LEDC2012X80N")
      (description "LED")
      (fields
        (field (name "MOUSER PART NUMBER") "755-SML-210VTT86")
        (field (name "RS PART NUMBER") "7007893P")
      )
      (libsource (lib "BMS_Slave") (part "SML-210VTT86"))
    )
    (comp (ref "D43")
      (value "SML-210VTT86")
      (footprint "SamacSys:LEDC2012X80N")
      (description "LED")
      (fields
        (field (name "MOUSER PART NUMBER") "755-SML-210VTT86")
        (field (name "RS PART NUMBER") "7007893P")
      )
      (libsource (lib "BMS_Slave") (part "SML-210VTT86"))
    )
    (comp (ref "D44")
      (value "SML-210VTT86")
      (footprint "SamacSys:LEDC2012X80N")
      (description "LED")
      (fields
        (field (name "MOUSER PART NUMBER") "755-SML-210VTT86")
        (field (name "RS PART NUMBER") "7007893P")
      )
      (libsource (lib "BMS_Slave") (part "SML-210VTT86"))
    )
    (comp (ref "D45")
      (value "SML-210VTT86")
      (footprint "SamacSys:LEDC2012X80N")
      (description "LED")
      (fields
        (field (name "MOUSER PART NUMBER") "755-SML-210VTT86")
        (field (name "RS PART NUMBER") "7007893P")
      )
      (libsource (lib "BMS_Slave") (part "SML-210VTT86"))
    )
    (comp (ref "D46")
      (value "SML-210VTT86")
      (footprint "SamacSys:LEDC2012X80N")
      (description "LED")
      (fields
        (field (name "MOUSER PART NUMBER") "755-SML-210VTT86")
        (field (name "RS PART NUMBER") "7007893P")
      )
      (libsource (lib "BMS_Slave") (part "SML-210VTT86"))
    )
    (comp (ref "D47")
      (value "SML-210VTT86")
      (footprint "SamacSys:LEDC2012X80N")
      (description "LED")
      (fields
        (field (name "MOUSER PART NUMBER") "755-SML-210VTT86")
        (field (name "RS PART NUMBER") "7007893P")
      )
      (libsource (lib "BMS_Slave") (part "SML-210VTT86"))
    )
    (comp (ref "D48")
      (value "SML-210VTT86")
      (footprint "SamacSys:LEDC2012X80N")
      (description "LED")
      (fields
        (field (name "MOUSER PART NUMBER") "755-SML-210VTT86")
        (field (name "RS PART NUMBER") "7007893P")
      )
      (libsource (lib "BMS_Slave") (part "SML-210VTT86"))
    )
    (comp (ref "D49")
      (value "SML-210VTT86")
      (footprint "SamacSys:LEDC2012X80N")
      (description "LED")
      (fields
        (field (name "MOUSER PART NUMBER") "755-SML-210VTT86")
        (field (name "RS PART NUMBER") "7007893P")
      )
      (libsource (lib "BMS_Slave") (part "SML-210VTT86"))
    )
    (comp (ref "D50")
      (value "SML-210VTT86")
      (footprint "SamacSys:LEDC2012X80N")
      (description "LED")
      (fields
        (field (name "MOUSER PART NUMBER") "755-SML-210VTT86")
        (field (name "RS PART NUMBER") "7007893P")
      )
      (libsource (lib "BMS_Slave") (part "SML-210VTT86"))
    )
    (comp (ref "F1")
      (value "0885001.DR")
      (footprint "0679L0250-05_fuse_SMD")
      (description "Fuse")
      (fields (field (name "MOUSER PART NUMBER") "576-0885001.DR"))
      (libsource (lib "BMS_Slave") (part "0885001.DR"))
    )
    (comp (ref "F2")
      (value "0885001.DR")
      (footprint "0679L0250-05_fuse_SMD")
      (description "Fuse")
      (fields (field (name "MOUSER PART NUMBER") "576-0885001.DR"))
      (libsource (lib "BMS_Slave") (part "0885001.DR"))
    )
    (comp (ref "F3")
      (value "0885001.DR")
      (footprint "0679L0250-05_fuse_SMD")
      (description "Fuse")
      (fields (field (name "MOUSER PART NUMBER") "576-0885001.DR"))
      (libsource (lib "BMS_Slave") (part "0885001.DR"))
    )
    (comp (ref "F4")
      (value "0885001.DR")
      (footprint "0679L0250-05_fuse_SMD")
      (description "Fuse")
      (fields (field (name "MOUSER PART NUMBER") "576-0885001.DR"))
      (libsource (lib "BMS_Slave") (part "0885001.DR"))
    )
    (comp (ref "F5")
      (value "0885001.DR")
      (footprint "0679L0250-05_fuse_SMD")
      (description "Fuse")
      (fields (field (name "MOUSER PART NUMBER") "576-0885001.DR"))
      (libsource (lib "BMS_Slave") (part "0885001.DR"))
    )
    (comp (ref "F6")
      (value "0885001.DR")
      (footprint "0679L0250-05_fuse_SMD")
      (description "Fuse")
      (fields (field (name "MOUSER PART NUMBER") "576-0885001.DR"))
      (libsource (lib "BMS_Slave") (part "0885001.DR"))
    )
    (comp (ref "F7")
      (value "0885001.DR")
      (footprint "0679L0250-05_fuse_SMD")
      (description "Fuse")
      (fields (field (name "MOUSER PART NUMBER") "576-0885001.DR"))
      (libsource (lib "BMS_Slave") (part "0885001.DR"))
    )
    (comp (ref "F8")
      (value "0885001.DR")
      (footprint "0679L0250-05_fuse_SMD")
      (description "Fuse")
      (fields (field (name "MOUSER PART NUMBER") "576-0885001.DR"))
      (libsource (lib "BMS_Slave") (part "0885001.DR"))
    )
    (comp (ref "F9")
      (value "0885001.DR")
      (footprint "0679L0250-05_fuse_SMD")
      (description "Fuse")
      (fields (field (name "MOUSER PART NUMBER") "576-0885001.DR"))
      (libsource (lib "BMS_Slave") (part "0885001.DR"))
    )
    (comp (ref "F10")
      (value "0885001.DR")
      (footprint "0679L0250-05_fuse_SMD")
      (description "Fuse")
      (fields (field (name "MOUSER PART NUMBER") "576-0885001.DR"))
      (libsource (lib "BMS_Slave") (part "0885001.DR"))
    )
    (comp (ref "F11")
      (value "0885001.DR")
      (footprint "0679L0250-05_fuse_SMD")
      (description "Fuse")
      (fields (field (name "MOUSER PART NUMBER") "576-0885001.DR"))
      (libsource (lib "BMS_Slave") (part "0885001.DR"))
    )
    (comp (ref "F12")
      (value "0885001.DR")
      (footprint "0679L0250-05_fuse_SMD")
      (description "Fuse")
      (fields (field (name "MOUSER PART NUMBER") "576-0885001.DR"))
      (libsource (lib "BMS_Slave") (part "0885001.DR"))
    )
    (comp (ref "F13")
      (value "0885001.DR")
      (footprint "0679L0250-05_fuse_SMD")
      (description "Fuse")
      (fields (field (name "MOUSER PART NUMBER") "576-0885001.DR"))
      (libsource (lib "BMS_Slave") (part "0885001.DR"))
    )
    (comp (ref "F14")
      (value "0885001.DR")
      (footprint "0679L0250-05_fuse_SMD")
      (description "Fuse")
      (fields (field (name "MOUSER PART NUMBER") "576-0885001.DR"))
      (libsource (lib "BMS_Slave") (part "0885001.DR"))
    )
    (comp (ref "F15")
      (value "0885001.DR")
      (footprint "0679L0250-05_fuse_SMD")
      (description "Fuse")
      (fields (field (name "MOUSER PART NUMBER") "576-0885001.DR"))
      (libsource (lib "BMS_Slave") (part "0885001.DR"))
    )
    (comp (ref "F16")
      (value "0885001.DR")
      (footprint "0679L0250-05_fuse_SMD")
      (description "Fuse")
      (fields (field (name "MOUSER PART NUMBER") "576-0885001.DR"))
      (libsource (lib "BMS_Slave") (part "0885001.DR"))
    )
    (comp (ref "F17")
      (value "0885001.DR")
      (footprint "0679L0250-05_fuse_SMD")
      (description "Fuse")
      (fields (field (name "MOUSER PART NUMBER") "576-0885001.DR"))
      (libsource (lib "BMS_Slave") (part "0885001.DR"))
    )
    (comp (ref "F18")
      (value "0885001.DR")
      (footprint "0679L0250-05_fuse_SMD")
      (description "Fuse")
      (fields (field (name "MOUSER PART NUMBER") "576-0885001.DR"))
      (libsource (lib "BMS_Slave") (part "0885001.DR"))
    )
    (comp (ref "F19")
      (value "0885001.DR")
      (footprint "0679L0250-05_fuse_SMD")
      (description "Fuse")
      (fields (field (name "MOUSER PART NUMBER") "576-0885001.DR"))
      (libsource (lib "BMS_Slave") (part "0885001.DR"))
    )
    (comp (ref "F20")
      (value "0885001.DR")
      (footprint "0679L0250-05_fuse_SMD")
      (description "Fuse")
      (fields (field (name "MOUSER PART NUMBER") "576-0885001.DR"))
      (libsource (lib "BMS_Slave") (part "0885001.DR"))
    )
    (comp (ref "F21")
      (value "0885001.DR")
      (footprint "0679L0250-05_fuse_SMD")
      (description "Fuse")
      (fields (field (name "MOUSER PART NUMBER") "576-0885001.DR"))
      (libsource (lib "BMS_Slave") (part "0885001.DR"))
    )
    (comp (ref "F22")
      (value "0885001.DR")
      (footprint "0679L0250-05_fuse_SMD")
      (description "Fuse")
      (fields (field (name "MOUSER PART NUMBER") "576-0885001.DR"))
      (libsource (lib "BMS_Slave") (part "0885001.DR"))
    )
    (comp (ref "F23")
      (value "0885001.DR")
      (footprint "0679L0250-05_fuse_SMD")
      (description "Fuse")
      (fields (field (name "MOUSER PART NUMBER") "576-0885001.DR"))
      (libsource (lib "BMS_Slave") (part "0885001.DR"))
    )
    (comp (ref "F24")
      (value "0885001.DR")
      (footprint "0679L0250-05_fuse_SMD")
      (description "Fuse")
      (fields (field (name "MOUSER PART NUMBER") "576-0885001.DR"))
      (libsource (lib "BMS_Slave") (part "0885001.DR"))
    )
    (comp (ref "F25")
      (value "0885001.DR")
      (footprint "0679L0250-05_fuse_SMD")
      (description "Fuse")
      (fields (field (name "MOUSER PART NUMBER") "576-0885001.DR"))
      (libsource (lib "BMS_Slave") (part "0885001.DR"))
    )
    (comp (ref "FL1")
      (value "ACT45B-101-2P-TL003")
      (footprint "BMS_Slave:ACT45B1012PTL003")
      (description "Filter")
      (fields (field (name "MOUSER PART NUMBER") "810-ACT45B1012PTL003"))
      (libsource (lib "BMS_Slave") (part "ACT45B-101-2P-TL003"))
    )
    (comp (ref "J1")
      (value "87831-1220")
      (footprint "BMS_Slave:SHDR12W55P200_2X6_1465X630X640P")
      (description "Connector")
      (fields (field (name "MOUSER PART NUMBER") "538-87831-1220"))
      (libsource (lib "BMS_Slave") (part "87831-1220"))
    )
    (comp (ref "J2")
      (value "87831-1220")
      (footprint "BMS_Slave:SHDR12W55P200_2X6_1465X630X640P")
      (description "Connector")
      (fields (field (name "MOUSER PART NUMBER") "538-87831-1220"))
      (libsource (lib "BMS_Slave") (part "87831-1220"))
    )
    (comp (ref "J3")
      (value "5406298-1")
      (footprint "BMS_Slave:54062981")
      (description "Connector")
      (fields (field (name "MOUSER PART NUMBER") "571-5406298-1"))
      (libsource (lib "BMS_Slave") (part "5406298-1"))
    )
    (comp (ref "J4")
      (value "5406298-1")
      (footprint "BMS_Slave:54062981")
      (description "Connector")
      (fields (field (name "MOUSER PART NUMBER") "571-5406298-1"))
      (libsource (lib "BMS_Slave") (part "5406298-1"))
    )
    (comp (ref "JP1")
      (value "2355045-3")
      (footprint "BMS_Slave:23550453")
      (description "2mm, 3POS Jumper Socket")
      (fields (field (name "MOUSER PART NUMBER") "571-2355045-3"))
      (libsource (lib "") (part "2355045-3_1"))
    )
    (comp (ref "JP2")
      (value "2355045-3")
      (footprint "BMS_Slave:23550453")
      (description "2mm, 3POS Jumper Socket")
      (fields (field (name "MOUSER PART NUMBER") "571-2355045-3"))
      (libsource (lib "") (part "2355045-3_1"))
    )
    (comp (ref "JP3")
      (value "2355045-3")
      (footprint "BMS_Slave:23550453")
      (description "2mm, 3POS Jumper Socket")
      (fields (field (name "MOUSER PART NUMBER") "571-2355045-3"))
      (libsource (lib "BMS_Slave") (part "2355045-3"))
    )
    (comp (ref "JP4")
      (value "2355045-3")
      (footprint "BMS_Slave:23550453")
      (description "2mm, 3POS Jumper Socket")
      (fields (field (name "MOUSER PART NUMBER") "571-2355045-3"))
      (libsource (lib "BMS_Slave") (part "2355045-3"))
    )
    (comp (ref "P1")
      (value "Molex 12ckt Connector")
      (footprint "34826-0125")
      (description "Molex Mini50, 12ckt")
      (libsource (lib "BMS_Slave") (part "34826-0125"))
    )
    (comp (ref "P2")
      (value "Molex 16ckt Connector")
      (footprint "34826-0160")
      (description "Molex Mini50, 16ckt")
      (libsource (lib "BMS_Slave") (part "34826-0160"))
    )
    (comp (ref "Q1")
      (value "BSS308PE_H6327")
      (footprint "BMS_Slave:SOT95P260X110-3N")
      (description "MOSFET (P-Channel)")
      (fields
        (field (name "MANUFACTURER_PART_NUMBER") "BSS308PE H6327")
        (field (name "MOUSER PART NUMBER") "726-BSS308PEH6327")
      )
      (libsource (lib "BMS_Slave") (part "BSS308PE_H6327"))
    )
    (comp (ref "Q2")
      (value "BSS308PE_H6327")
      (footprint "BMS_Slave:SOT95P260X110-3N")
      (description "MOSFET (P-Channel)")
      (fields
        (field (name "MANUFACTURER_PART_NUMBER") "BSS308PE H6327")
        (field (name "MOUSER PART NUMBER") "726-BSS308PEH6327")
      )
      (libsource (lib "BMS_Slave") (part "BSS308PE_H6327"))
    )
    (comp (ref "Q3")
      (value "BSS308PE_H6327")
      (footprint "BMS_Slave:SOT95P260X110-3N")
      (description "MOSFET (P-Channel)")
      (fields
        (field (name "MANUFACTURER_PART_NUMBER") "BSS308PE H6327")
        (field (name "MOUSER PART NUMBER") "726-BSS308PEH6327")
      )
      (libsource (lib "BMS_Slave") (part "BSS308PE_H6327"))
    )
    (comp (ref "Q4")
      (value "BSS308PE_H6327")
      (footprint "BMS_Slave:SOT95P260X110-3N")
      (description "MOSFET (P-Channel)")
      (fields
        (field (name "MANUFACTURER_PART_NUMBER") "BSS308PE H6327")
        (field (name "MOUSER PART NUMBER") "726-BSS308PEH6327")
      )
      (libsource (lib "BMS_Slave") (part "BSS308PE_H6327"))
    )
    (comp (ref "Q5")
      (value "BSS308PE_H6327")
      (footprint "BMS_Slave:SOT95P260X110-3N")
      (description "MOSFET (P-Channel)")
      (fields
        (field (name "MANUFACTURER_PART_NUMBER") "BSS308PE H6327")
        (field (name "MOUSER PART NUMBER") "726-BSS308PEH6327")
      )
      (libsource (lib "BMS_Slave") (part "BSS308PE_H6327"))
    )
    (comp (ref "Q6")
      (value "BSS308PE_H6327")
      (footprint "BMS_Slave:SOT95P260X110-3N")
      (description "MOSFET (P-Channel)")
      (fields
        (field (name "MANUFACTURER_PART_NUMBER") "BSS308PE H6327")
        (field (name "MOUSER PART NUMBER") "726-BSS308PEH6327")
      )
      (libsource (lib "BMS_Slave") (part "BSS308PE_H6327"))
    )
    (comp (ref "Q7")
      (value "BSS308PE_H6327")
      (footprint "BMS_Slave:SOT95P260X110-3N")
      (description "MOSFET (P-Channel)")
      (fields
        (field (name "MANUFACTURER_PART_NUMBER") "BSS308PE H6327")
        (field (name "MOUSER PART NUMBER") "726-BSS308PEH6327")
      )
      (libsource (lib "BMS_Slave") (part "BSS308PE_H6327"))
    )
    (comp (ref "Q8")
      (value "BSS308PE_H6327")
      (footprint "BMS_Slave:SOT95P260X110-3N")
      (description "MOSFET (P-Channel)")
      (fields
        (field (name "MANUFACTURER_PART_NUMBER") "BSS308PE H6327")
        (field (name "MOUSER PART NUMBER") "726-BSS308PEH6327")
      )
      (libsource (lib "BMS_Slave") (part "BSS308PE_H6327"))
    )
    (comp (ref "Q9")
      (value "BSS308PE_H6327")
      (footprint "BMS_Slave:SOT95P260X110-3N")
      (description "MOSFET (P-Channel)")
      (fields
        (field (name "MANUFACTURER_PART_NUMBER") "BSS308PE H6327")
        (field (name "MOUSER PART NUMBER") "726-BSS308PEH6327")
      )
      (libsource (lib "BMS_Slave") (part "BSS308PE_H6327"))
    )
    (comp (ref "Q10")
      (value "BSS308PE_H6327")
      (footprint "BMS_Slave:SOT95P260X110-3N")
      (description "MOSFET (P-Channel)")
      (fields
        (field (name "MANUFACTURER_PART_NUMBER") "BSS308PE H6327")
        (field (name "MOUSER PART NUMBER") "726-BSS308PEH6327")
      )
      (libsource (lib "BMS_Slave") (part "BSS308PE_H6327"))
    )
    (comp (ref "Q11")
      (value "BSS308PE_H6327")
      (footprint "BMS_Slave:SOT95P260X110-3N")
      (description "MOSFET (P-Channel)")
      (fields
        (field (name "MANUFACTURER_PART_NUMBER") "BSS308PE H6327")
        (field (name "MOUSER PART NUMBER") "726-BSS308PEH6327")
      )
      (libsource (lib "BMS_Slave") (part "BSS308PE_H6327"))
    )
    (comp (ref "Q12")
      (value "BSS308PE_H6327")
      (footprint "BMS_Slave:SOT95P260X110-3N")
      (description "MOSFET (P-Channel)")
      (fields
        (field (name "MANUFACTURER_PART_NUMBER") "BSS308PE H6327")
        (field (name "MOUSER PART NUMBER") "726-BSS308PEH6327")
      )
      (libsource (lib "BMS_Slave") (part "BSS308PE_H6327"))
    )
    (comp (ref "Q13")
      (value "BSS308PE_H6327")
      (footprint "BMS_Slave:SOT95P260X110-3N")
      (description "MOSFET (P-Channel)")
      (fields
        (field (name "MANUFACTURER_PART_NUMBER") "BSS308PE H6327")
        (field (name "MOUSER PART NUMBER") "726-BSS308PEH6327")
      )
      (libsource (lib "BMS_Slave") (part "BSS308PE_H6327"))
    )
    (comp (ref "Q14")
      (value "BSS308PE_H6327")
      (footprint "BMS_Slave:SOT95P260X110-3N")
      (description "MOSFET (P-Channel)")
      (fields
        (field (name "MANUFACTURER_PART_NUMBER") "BSS308PE H6327")
        (field (name "MOUSER PART NUMBER") "726-BSS308PEH6327")
      )
      (libsource (lib "BMS_Slave") (part "BSS308PE_H6327"))
    )
    (comp (ref "Q15")
      (value "BSS308PE_H6327")
      (footprint "BMS_Slave:SOT95P260X110-3N")
      (description "MOSFET (P-Channel)")
      (fields
        (field (name "MANUFACTURER_PART_NUMBER") "BSS308PE H6327")
        (field (name "MOUSER PART NUMBER") "726-BSS308PEH6327")
      )
      (libsource (lib "BMS_Slave") (part "BSS308PE_H6327"))
    )
    (comp (ref "Q16")
      (value "BSS308PE_H6327")
      (footprint "BMS_Slave:SOT95P260X110-3N")
      (description "MOSFET (P-Channel)")
      (fields
        (field (name "MANUFACTURER_PART_NUMBER") "BSS308PE H6327")
        (field (name "MOUSER PART NUMBER") "726-BSS308PEH6327")
      )
      (libsource (lib "BMS_Slave") (part "BSS308PE_H6327"))
    )
    (comp (ref "Q17")
      (value "BSS308PE_H6327")
      (footprint "BMS_Slave:SOT95P260X110-3N")
      (description "MOSFET (P-Channel)")
      (fields
        (field (name "MANUFACTURER_PART_NUMBER") "BSS308PE H6327")
        (field (name "MOUSER PART NUMBER") "726-BSS308PEH6327")
      )
      (libsource (lib "BMS_Slave") (part "BSS308PE_H6327"))
    )
    (comp (ref "Q18")
      (value "BSS308PE_H6327")
      (footprint "BMS_Slave:SOT95P260X110-3N")
      (description "MOSFET (P-Channel)")
      (fields
        (field (name "MANUFACTURER_PART_NUMBER") "BSS308PE H6327")
        (field (name "MOUSER PART NUMBER") "726-BSS308PEH6327")
      )
      (libsource (lib "BMS_Slave") (part "BSS308PE_H6327"))
    )
    (comp (ref "Q19")
      (value "BSS308PE_H6327")
      (footprint "BMS_Slave:SOT95P260X110-3N")
      (description "MOSFET (P-Channel)")
      (fields
        (field (name "MANUFACTURER_PART_NUMBER") "BSS308PE H6327")
        (field (name "MOUSER PART NUMBER") "726-BSS308PEH6327")
      )
      (libsource (lib "BMS_Slave") (part "BSS308PE_H6327"))
    )
    (comp (ref "Q20")
      (value "BSS308PE_H6327")
      (footprint "BMS_Slave:SOT95P260X110-3N")
      (description "MOSFET (P-Channel)")
      (fields
        (field (name "MANUFACTURER_PART_NUMBER") "BSS308PE H6327")
        (field (name "MOUSER PART NUMBER") "726-BSS308PEH6327")
      )
      (libsource (lib "BMS_Slave") (part "BSS308PE_H6327"))
    )
    (comp (ref "Q21")
      (value "BSS308PE_H6327")
      (footprint "BMS_Slave:SOT95P260X110-3N")
      (description "MOSFET (P-Channel)")
      (fields
        (field (name "MANUFACTURER_PART_NUMBER") "BSS308PE H6327")
        (field (name "MOUSER PART NUMBER") "726-BSS308PEH6327")
      )
      (libsource (lib "BMS_Slave") (part "BSS308PE_H6327"))
    )
    (comp (ref "Q22")
      (value "BSS308PE_H6327")
      (footprint "BMS_Slave:SOT95P260X110-3N")
      (description "MOSFET (P-Channel)")
      (fields
        (field (name "MANUFACTURER_PART_NUMBER") "BSS308PE H6327")
        (field (name "MOUSER PART NUMBER") "726-BSS308PEH6327")
      )
      (libsource (lib "BMS_Slave") (part "BSS308PE_H6327"))
    )
    (comp (ref "Q23")
      (value "BSS308PE_H6327")
      (footprint "BMS_Slave:SOT95P260X110-3N")
      (description "MOSFET (P-Channel)")
      (fields
        (field (name "MANUFACTURER_PART_NUMBER") "BSS308PE H6327")
        (field (name "MOUSER PART NUMBER") "726-BSS308PEH6327")
      )
      (libsource (lib "BMS_Slave") (part "BSS308PE_H6327"))
    )
    (comp (ref "Q24")
      (value "BSS308PE_H6327")
      (footprint "BMS_Slave:SOT95P260X110-3N")
      (description "MOSFET (P-Channel)")
      (fields
        (field (name "MANUFACTURER_PART_NUMBER") "BSS308PE H6327")
        (field (name "MOUSER PART NUMBER") "726-BSS308PEH6327")
      )
      (libsource (lib "BMS_Slave") (part "BSS308PE_H6327"))
    )
    (comp (ref "Q25")
      (value "DXT5551P5-13")
      (footprint "BMS_Slave:DXT5551P513")
      (description "Transistor BJT NPN")
      (fields (field (name "MOUSER PART NUMBER") "522-DXT5551P5-13"))
      (libsource (lib "BMS_Slave") (part "DXT5551P5-13"))
    )
    (comp (ref "Q26")
      (value "DXT5551P5-13")
      (footprint "BMS_Slave:DXT5551P513")
      (description "Transistor BJT NPN")
      (fields (field (name "MOUSER PART NUMBER") "522-DXT5551P5-13"))
      (libsource (lib "BMS_Slave") (part "DXT5551P5-13"))
    )
    (comp (ref "R1")
      (value "100R")
      (footprint "BMS_Slave:RESC1608X55N")
      (description "Res Thick Film 0603 1/8W ±100ppm/°C Molded SMD Paper T/R")
      (fields
        (field (name "MANUFACTURER") "Vishay")
        (field (name "MANUFACTURER PART NUMBER") "CRCW080510K0FKEAC")
      )
      (libsource (lib "BMS_Slave") (part "CRCW060310K0FKEAC"))
    )
    (comp (ref "R2")
      (value "3.3k")
      (footprint "BMS_Slave:RESC1608X55N")
      (description "Res Thick Film 0603 1/8W ±100ppm/°C Molded SMD Paper T/R")
      (fields
        (field (name "MANUFACTURER") "Vishay")
        (field (name "MANUFACTURER PART NUMBER") "CRCW080510K0FKEAC")
      )
      (libsource (lib "BMS_Slave") (part "CRCW060310K0FKEAC"))
    )
    (comp (ref "R3")
      (value "100R")
      (footprint "BMS_Slave:RESC1608X55N")
      (description "Res Thick Film 0603 1/8W ±100ppm/°C Molded SMD Paper T/R")
      (fields
        (field (name "MANUFACTURER") "Vishay")
        (field (name "MANUFACTURER PART NUMBER") "CRCW080510K0FKEAC")
      )
      (libsource (lib "BMS_Slave") (part "CRCW060310K0FKEAC"))
    )
    (comp (ref "R4")
      (value "3.3k")
      (footprint "BMS_Slave:RESC1608X55N")
      (description "Res Thick Film 0603 1/8W ±100ppm/°C Molded SMD Paper T/R")
      (fields
        (field (name "MANUFACTURER") "Vishay")
        (field (name "MANUFACTURER PART NUMBER") "CRCW080510K0FKEAC")
      )
      (libsource (lib "BMS_Slave") (part "CRCW060310K0FKEAC"))
    )
    (comp (ref "R5")
      (value "100R")
      (footprint "BMS_Slave:RESC1608X55N")
      (description "Res Thick Film 0603 1/8W ±100ppm/°C Molded SMD Paper T/R")
      (fields
        (field (name "MANUFACTURER") "Vishay")
        (field (name "MANUFACTURER PART NUMBER") "CRCW080510K0FKEAC")
      )
      (libsource (lib "BMS_Slave") (part "CRCW060310K0FKEAC"))
    )
    (comp (ref "R6")
      (value "3.3k")
      (footprint "BMS_Slave:RESC1608X55N")
      (description "Res Thick Film 0603 1/8W ±100ppm/°C Molded SMD Paper T/R")
      (fields
        (field (name "MANUFACTURER") "Vishay")
        (field (name "MANUFACTURER PART NUMBER") "CRCW080510K0FKEAC")
      )
      (libsource (lib "BMS_Slave") (part "CRCW060310K0FKEAC"))
    )
    (comp (ref "R7")
      (value "100R")
      (footprint "BMS_Slave:RESC1608X55N")
      (description "Res Thick Film 0603 1/8W ±100ppm/°C Molded SMD Paper T/R")
      (fields
        (field (name "MANUFACTURER") "Vishay")
        (field (name "MANUFACTURER PART NUMBER") "CRCW080510K0FKEAC")
      )
      (libsource (lib "BMS_Slave") (part "CRCW060310K0FKEAC"))
    )
    (comp (ref "R8")
      (value "3.3k")
      (footprint "BMS_Slave:RESC1608X55N")
      (description "Res Thick Film 0603 1/8W ±100ppm/°C Molded SMD Paper T/R")
      (fields
        (field (name "MANUFACTURER") "Vishay")
        (field (name "MANUFACTURER PART NUMBER") "CRCW080510K0FKEAC")
      )
      (libsource (lib "BMS_Slave") (part "CRCW060310K0FKEAC"))
    )
    (comp (ref "R9")
      (value "100R")
      (footprint "BMS_Slave:RESC1608X55N")
      (description "Res Thick Film 0603 1/8W ±100ppm/°C Molded SMD Paper T/R")
      (fields
        (field (name "MANUFACTURER") "Vishay")
        (field (name "MANUFACTURER PART NUMBER") "CRCW080510K0FKEAC")
      )
      (libsource (lib "BMS_Slave") (part "CRCW060310K0FKEAC"))
    )
    (comp (ref "R10")
      (value "3.3k")
      (footprint "BMS_Slave:RESC1608X55N")
      (description "Res Thick Film 0603 1/8W ±100ppm/°C Molded SMD Paper T/R")
      (fields
        (field (name "MANUFACTURER") "Vishay")
        (field (name "MANUFACTURER PART NUMBER") "CRCW080510K0FKEAC")
      )
      (libsource (lib "BMS_Slave") (part "CRCW060310K0FKEAC"))
    )
    (comp (ref "R11")
      (value "100R")
      (footprint "BMS_Slave:RESC1608X55N")
      (description "Res Thick Film 0603 1/8W ±100ppm/°C Molded SMD Paper T/R")
      (fields
        (field (name "MANUFACTURER") "Vishay")
        (field (name "MANUFACTURER PART NUMBER") "CRCW080510K0FKEAC")
      )
      (libsource (lib "BMS_Slave") (part "CRCW060310K0FKEAC"))
    )
    (comp (ref "R12")
      (value "3.3k")
      (footprint "BMS_Slave:RESC1608X55N")
      (description "Res Thick Film 0603 1/8W ±100ppm/°C Molded SMD Paper T/R")
      (fields
        (field (name "MANUFACTURER") "Vishay")
        (field (name "MANUFACTURER PART NUMBER") "CRCW080510K0FKEAC")
      )
      (libsource (lib "BMS_Slave") (part "CRCW060310K0FKEAC"))
    )
    (comp (ref "R13")
      (value "100R")
      (footprint "BMS_Slave:RESC1608X55N")
      (description "Res Thick Film 0603 1/8W ±100ppm/°C Molded SMD Paper T/R")
      (fields
        (field (name "MANUFACTURER") "Vishay")
        (field (name "MANUFACTURER PART NUMBER") "CRCW080510K0FKEAC")
      )
      (libsource (lib "BMS_Slave") (part "CRCW060310K0FKEAC"))
    )
    (comp (ref "R14")
      (value "3.3k")
      (footprint "BMS_Slave:RESC1608X55N")
      (description "Res Thick Film 0603 1/8W ±100ppm/°C Molded SMD Paper T/R")
      (fields
        (field (name "MANUFACTURER") "Vishay")
        (field (name "MANUFACTURER PART NUMBER") "CRCW080510K0FKEAC")
      )
      (libsource (lib "BMS_Slave") (part "CRCW060310K0FKEAC"))
    )
    (comp (ref "R15")
      (value "100R")
      (footprint "BMS_Slave:RESC1608X55N")
      (description "Res Thick Film 0603 1/8W ±100ppm/°C Molded SMD Paper T/R")
      (fields
        (field (name "MANUFACTURER") "Vishay")
        (field (name "MANUFACTURER PART NUMBER") "CRCW080510K0FKEAC")
      )
      (libsource (lib "BMS_Slave") (part "CRCW060310K0FKEAC"))
    )
    (comp (ref "R16")
      (value "3.3k")
      (footprint "BMS_Slave:RESC1608X55N")
      (description "Res Thick Film 0603 1/8W ±100ppm/°C Molded SMD Paper T/R")
      (fields
        (field (name "MANUFACTURER") "Vishay")
        (field (name "MANUFACTURER PART NUMBER") "CRCW080510K0FKEAC")
      )
      (libsource (lib "BMS_Slave") (part "CRCW060310K0FKEAC"))
    )
    (comp (ref "R17")
      (value "100R")
      (footprint "BMS_Slave:RESC1608X55N")
      (description "Res Thick Film 0603 1/8W ±100ppm/°C Molded SMD Paper T/R")
      (fields
        (field (name "MANUFACTURER") "Vishay")
        (field (name "MANUFACTURER PART NUMBER") "CRCW080510K0FKEAC")
      )
      (libsource (lib "BMS_Slave") (part "CRCW060310K0FKEAC"))
    )
    (comp (ref "R18")
      (value "3.3k")
      (footprint "BMS_Slave:RESC1608X55N")
      (description "Res Thick Film 0603 1/8W ±100ppm/°C Molded SMD Paper T/R")
      (fields
        (field (name "MANUFACTURER") "Vishay")
        (field (name "MANUFACTURER PART NUMBER") "CRCW080510K0FKEAC")
      )
      (libsource (lib "BMS_Slave") (part "CRCW060310K0FKEAC"))
    )
    (comp (ref "R19")
      (value "100R")
      (footprint "BMS_Slave:RESC1608X55N")
      (description "Res Thick Film 0603 1/8W ±100ppm/°C Molded SMD Paper T/R")
      (fields
        (field (name "MANUFACTURER") "Vishay")
        (field (name "MANUFACTURER PART NUMBER") "CRCW080510K0FKEAC")
      )
      (libsource (lib "BMS_Slave") (part "CRCW060310K0FKEAC"))
    )
    (comp (ref "R20")
      (value "3.3k")
      (footprint "BMS_Slave:RESC1608X55N")
      (description "Res Thick Film 0603 1/8W ±100ppm/°C Molded SMD Paper T/R")
      (fields
        (field (name "MANUFACTURER") "Vishay")
        (field (name "MANUFACTURER PART NUMBER") "CRCW080510K0FKEAC")
      )
      (libsource (lib "BMS_Slave") (part "CRCW060310K0FKEAC"))
    )
    (comp (ref "R21")
      (value "100R")
      (footprint "BMS_Slave:RESC1608X55N")
      (description "Res Thick Film 0603 1/8W ±100ppm/°C Molded SMD Paper T/R")
      (fields
        (field (name "MANUFACTURER") "Vishay")
        (field (name "MANUFACTURER PART NUMBER") "CRCW080510K0FKEAC")
      )
      (libsource (lib "BMS_Slave") (part "CRCW060310K0FKEAC"))
    )
    (comp (ref "R22")
      (value "3.3k")
      (footprint "BMS_Slave:RESC1608X55N")
      (description "Res Thick Film 0603 1/8W ±100ppm/°C Molded SMD Paper T/R")
      (fields
        (field (name "MANUFACTURER") "Vishay")
        (field (name "MANUFACTURER PART NUMBER") "CRCW080510K0FKEAC")
      )
      (libsource (lib "BMS_Slave") (part "CRCW060310K0FKEAC"))
    )
    (comp (ref "R23")
      (value "100R")
      (footprint "BMS_Slave:RESC1608X55N")
      (description "Res Thick Film 0603 1/8W ±100ppm/°C Molded SMD Paper T/R")
      (fields
        (field (name "MANUFACTURER") "Vishay")
        (field (name "MANUFACTURER PART NUMBER") "CRCW080510K0FKEAC")
      )
      (libsource (lib "BMS_Slave") (part "CRCW060310K0FKEAC"))
    )
    (comp (ref "R24")
      (value "3.3k")
      (footprint "BMS_Slave:RESC1608X55N")
      (description "Res Thick Film 0603 1/8W ±100ppm/°C Molded SMD Paper T/R")
      (fields
        (field (name "MANUFACTURER") "Vishay")
        (field (name "MANUFACTURER PART NUMBER") "CRCW080510K0FKEAC")
      )
      (libsource (lib "BMS_Slave") (part "CRCW060310K0FKEAC"))
    )
    (comp (ref "R25")
      (value "100R")
      (footprint "BMS_Slave:RESC1608X55N")
      (description "Res Thick Film 0603 1/8W ±100ppm/°C Molded SMD Paper T/R")
      (fields
        (field (name "MANUFACTURER") "Vishay")
        (field (name "MANUFACTURER PART NUMBER") "CRCW080510K0FKEAC")
      )
      (libsource (lib "BMS_Slave") (part "CRCW060310K0FKEAC"))
    )
    (comp (ref "R26")
      (value "3.3k")
      (footprint "BMS_Slave:RESC1608X55N")
      (description "Res Thick Film 0603 1/8W ±100ppm/°C Molded SMD Paper T/R")
      (fields
        (field (name "MANUFACTURER") "Vishay")
        (field (name "MANUFACTURER PART NUMBER") "CRCW080510K0FKEAC")
      )
      (libsource (lib "BMS_Slave") (part "CRCW060310K0FKEAC"))
    )
    (comp (ref "R27")
      (value "100R")
      (footprint "BMS_Slave:RESC1608X55N")
      (description "Res Thick Film 0603 1/8W ±100ppm/°C Molded SMD Paper T/R")
      (fields
        (field (name "MANUFACTURER") "Vishay")
        (field (name "MANUFACTURER PART NUMBER") "CRCW080510K0FKEAC")
      )
      (libsource (lib "BMS_Slave") (part "CRCW060310K0FKEAC"))
    )
    (comp (ref "R28")
      (value "3.3k")
      (footprint "BMS_Slave:RESC1608X55N")
      (description "Res Thick Film 0603 1/8W ±100ppm/°C Molded SMD Paper T/R")
      (fields
        (field (name "MANUFACTURER") "Vishay")
        (field (name "MANUFACTURER PART NUMBER") "CRCW080510K0FKEAC")
      )
      (libsource (lib "BMS_Slave") (part "CRCW060310K0FKEAC"))
    )
    (comp (ref "R29")
      (value "100R")
      (footprint "BMS_Slave:RESC1608X55N")
      (description "Res Thick Film 0603 1/8W ±100ppm/°C Molded SMD Paper T/R")
      (fields
        (field (name "MANUFACTURER") "Vishay")
        (field (name "MANUFACTURER PART NUMBER") "CRCW080510K0FKEAC")
      )
      (libsource (lib "BMS_Slave") (part "CRCW060310K0FKEAC"))
    )
    (comp (ref "R30")
      (value "3.3k")
      (footprint "BMS_Slave:RESC1608X55N")
      (description "Res Thick Film 0603 1/8W ±100ppm/°C Molded SMD Paper T/R")
      (fields
        (field (name "MANUFACTURER") "Vishay")
        (field (name "MANUFACTURER PART NUMBER") "CRCW080510K0FKEAC")
      )
      (libsource (lib "BMS_Slave") (part "CRCW060310K0FKEAC"))
    )
    (comp (ref "R31")
      (value "100R")
      (footprint "BMS_Slave:RESC1608X55N")
      (description "Res Thick Film 0603 1/8W ±100ppm/°C Molded SMD Paper T/R")
      (fields
        (field (name "MANUFACTURER") "Vishay")
        (field (name "MANUFACTURER PART NUMBER") "CRCW080510K0FKEAC")
      )
      (libsource (lib "BMS_Slave") (part "CRCW060310K0FKEAC"))
    )
    (comp (ref "R32")
      (value "3.3k")
      (footprint "BMS_Slave:RESC1608X55N")
      (description "Res Thick Film 0603 1/8W ±100ppm/°C Molded SMD Paper T/R")
      (fields
        (field (name "MANUFACTURER") "Vishay")
        (field (name "MANUFACTURER PART NUMBER") "CRCW080510K0FKEAC")
      )
      (libsource (lib "BMS_Slave") (part "CRCW060310K0FKEAC"))
    )
    (comp (ref "R33")
      (value "100R")
      (footprint "BMS_Slave:RESC1608X55N")
      (description "Res Thick Film 0603 1/8W ±100ppm/°C Molded SMD Paper T/R")
      (fields
        (field (name "MANUFACTURER") "Vishay")
        (field (name "MANUFACTURER PART NUMBER") "CRCW080510K0FKEAC")
      )
      (libsource (lib "BMS_Slave") (part "CRCW060310K0FKEAC"))
    )
    (comp (ref "R34")
      (value "3.3k")
      (footprint "BMS_Slave:RESC1608X55N")
      (description "Res Thick Film 0603 1/8W ±100ppm/°C Molded SMD Paper T/R")
      (fields
        (field (name "MANUFACTURER") "Vishay")
        (field (name "MANUFACTURER PART NUMBER") "CRCW080510K0FKEAC")
      )
      (libsource (lib "BMS_Slave") (part "CRCW060310K0FKEAC"))
    )
    (comp (ref "R35")
      (value "100R")
      (footprint "BMS_Slave:RESC1608X55N")
      (description "Res Thick Film 0603 1/8W ±100ppm/°C Molded SMD Paper T/R")
      (fields
        (field (name "MANUFACTURER") "Vishay")
        (field (name "MANUFACTURER PART NUMBER") "CRCW080510K0FKEAC")
      )
      (libsource (lib "BMS_Slave") (part "CRCW060310K0FKEAC"))
    )
    (comp (ref "R36")
      (value "3.3k")
      (footprint "BMS_Slave:RESC1608X55N")
      (description "Res Thick Film 0603 1/8W ±100ppm/°C Molded SMD Paper T/R")
      (fields
        (field (name "MANUFACTURER") "Vishay")
        (field (name "MANUFACTURER PART NUMBER") "CRCW080510K0FKEAC")
      )
      (libsource (lib "BMS_Slave") (part "CRCW060310K0FKEAC"))
    )
    (comp (ref "R37")
      (value "100R")
      (footprint "BMS_Slave:RESC1608X55N")
      (description "Res Thick Film 0603 1/8W ±100ppm/°C Molded SMD Paper T/R")
      (fields
        (field (name "MANUFACTURER") "Vishay")
        (field (name "MANUFACTURER PART NUMBER") "CRCW080510K0FKEAC")
      )
      (libsource (lib "BMS_Slave") (part "CRCW060310K0FKEAC"))
    )
    (comp (ref "R38")
      (value "3.3k")
      (footprint "BMS_Slave:RESC1608X55N")
      (description "Res Thick Film 0603 1/8W ±100ppm/°C Molded SMD Paper T/R")
      (fields
        (field (name "MANUFACTURER") "Vishay")
        (field (name "MANUFACTURER PART NUMBER") "CRCW080510K0FKEAC")
      )
      (libsource (lib "BMS_Slave") (part "CRCW060310K0FKEAC"))
    )
    (comp (ref "R39")
      (value "100R")
      (footprint "BMS_Slave:RESC1608X55N")
      (description "Res Thick Film 0603 1/8W ±100ppm/°C Molded SMD Paper T/R")
      (fields
        (field (name "MANUFACTURER") "Vishay")
        (field (name "MANUFACTURER PART NUMBER") "CRCW080510K0FKEAC")
      )
      (libsource (lib "BMS_Slave") (part "CRCW060310K0FKEAC"))
    )
    (comp (ref "R40")
      (value "3.3k")
      (footprint "BMS_Slave:RESC1608X55N")
      (description "Res Thick Film 0603 1/8W ±100ppm/°C Molded SMD Paper T/R")
      (fields
        (field (name "MANUFACTURER") "Vishay")
        (field (name "MANUFACTURER PART NUMBER") "CRCW080510K0FKEAC")
      )
      (libsource (lib "BMS_Slave") (part "CRCW060310K0FKEAC"))
    )
    (comp (ref "R41")
      (value "100R")
      (footprint "BMS_Slave:RESC1608X55N")
      (description "Res Thick Film 0603 1/8W ±100ppm/°C Molded SMD Paper T/R")
      (fields
        (field (name "MANUFACTURER") "Vishay")
        (field (name "MANUFACTURER PART NUMBER") "CRCW080510K0FKEAC")
      )
      (libsource (lib "BMS_Slave") (part "CRCW060310K0FKEAC"))
    )
    (comp (ref "R42")
      (value "3.3k")
      (footprint "BMS_Slave:RESC1608X55N")
      (description "Res Thick Film 0603 1/8W ±100ppm/°C Molded SMD Paper T/R")
      (fields
        (field (name "MANUFACTURER") "Vishay")
        (field (name "MANUFACTURER PART NUMBER") "CRCW080510K0FKEAC")
      )
      (libsource (lib "BMS_Slave") (part "CRCW060310K0FKEAC"))
    )
    (comp (ref "R43")
      (value "100R")
      (footprint "BMS_Slave:RESC1608X55N")
      (description "Res Thick Film 0603 1/8W ±100ppm/°C Molded SMD Paper T/R")
      (fields
        (field (name "MANUFACTURER") "Vishay")
        (field (name "MANUFACTURER PART NUMBER") "CRCW080510K0FKEAC")
      )
      (libsource (lib "BMS_Slave") (part "CRCW060310K0FKEAC"))
    )
    (comp (ref "R44")
      (value "3.3k")
      (footprint "BMS_Slave:RESC1608X55N")
      (description "Res Thick Film 0603 1/8W ±100ppm/°C Molded SMD Paper T/R")
      (fields
        (field (name "MANUFACTURER") "Vishay")
        (field (name "MANUFACTURER PART NUMBER") "CRCW080510K0FKEAC")
      )
      (libsource (lib "BMS_Slave") (part "CRCW060310K0FKEAC"))
    )
    (comp (ref "R45")
      (value "100R")
      (footprint "BMS_Slave:RESC1608X55N")
      (description "Res Thick Film 0603 1/8W ±100ppm/°C Molded SMD Paper T/R")
      (fields
        (field (name "MANUFACTURER") "Vishay")
        (field (name "MANUFACTURER PART NUMBER") "CRCW080510K0FKEAC")
      )
      (libsource (lib "BMS_Slave") (part "CRCW060310K0FKEAC"))
    )
    (comp (ref "R46")
      (value "3.3k")
      (footprint "BMS_Slave:RESC1608X55N")
      (description "Res Thick Film 0603 1/8W ±100ppm/°C Molded SMD Paper T/R")
      (fields
        (field (name "MANUFACTURER") "Vishay")
        (field (name "MANUFACTURER PART NUMBER") "CRCW080510K0FKEAC")
      )
      (libsource (lib "BMS_Slave") (part "CRCW060310K0FKEAC"))
    )
    (comp (ref "R47")
      (value "100R")
      (footprint "BMS_Slave:RESC1608X55N")
      (description "Res Thick Film 0603 1/8W ±100ppm/°C Molded SMD Paper T/R")
      (fields
        (field (name "MANUFACTURER") "Vishay")
        (field (name "MANUFACTURER PART NUMBER") "CRCW080510K0FKEAC")
      )
      (libsource (lib "BMS_Slave") (part "CRCW060310K0FKEAC"))
    )
    (comp (ref "R48")
      (value "3.3k")
      (footprint "BMS_Slave:RESC1608X55N")
      (description "Res Thick Film 0603 1/8W ±100ppm/°C Molded SMD Paper T/R")
      (fields
        (field (name "MANUFACTURER") "Vishay")
        (field (name "MANUFACTURER PART NUMBER") "CRCW080510K0FKEAC")
      )
      (libsource (lib "BMS_Slave") (part "CRCW060310K0FKEAC"))
    )
    (comp (ref "R49")
      (value "100R")
      (footprint "BMS_Slave:RESC1608X55N")
      (description "Res Thick Film 0603 1/8W ±100ppm/°C Molded SMD Paper T/R")
      (fields
        (field (name "MANUFACTURER") "Vishay")
        (field (name "MANUFACTURER PART NUMBER") "CRCW080510K0FKEAC")
      )
      (libsource (lib "BMS_Slave") (part "CRCW060310K0FKEAC"))
    )
    (comp (ref "R50")
      (value "0R")
      (footprint "BMS_Slave:RESC1608X55N")
      (description "Res Thick Film 0603 1/8W ±100ppm/°C Molded SMD Paper T/R")
      (fields
        (field (name "MANUFACTURER") "Vishay")
        (field (name "MANUFACTURER PART NUMBER") "CRCW080510K0FKEAC")
      )
      (libsource (lib "BMS_Slave") (part "CRCW060310K0FKEAC"))
    )
    (comp (ref "R51")
      (value "475R")
      (footprint "BMS_Slave:RESC1608X55N")
      (description "Res Thick Film 0603 1/8W ±100ppm/°C Molded SMD Paper T/R")
      (fields
        (field (name "MANUFACTURER") "Vishay")
        (field (name "MANUFACTURER PART NUMBER") "CRCW080510K0FKEAC")
      )
      (libsource (lib "BMS_Slave") (part "CRCW060310K0FKEAC"))
    )
    (comp (ref "R52")
      (value "475R")
      (footprint "BMS_Slave:RESC1608X55N")
      (description "Res Thick Film 0603 1/8W ±100ppm/°C Molded SMD Paper T/R")
      (fields
        (field (name "MANUFACTURER") "Vishay")
        (field (name "MANUFACTURER PART NUMBER") "CRCW080510K0FKEAC")
      )
      (libsource (lib "BMS_Slave") (part "CRCW060310K0FKEAC"))
    )
    (comp (ref "R53")
      (value "475R")
      (footprint "BMS_Slave:RESC1608X55N")
      (description "Res Thick Film 0603 1/8W ±100ppm/°C Molded SMD Paper T/R")
      (fields
        (field (name "MANUFACTURER") "Vishay")
        (field (name "MANUFACTURER PART NUMBER") "CRCW080510K0FKEAC")
      )
      (libsource (lib "BMS_Slave") (part "CRCW060310K0FKEAC"))
    )
    (comp (ref "R54")
      (value "475R")
      (footprint "BMS_Slave:RESC1608X55N")
      (description "Res Thick Film 0603 1/8W ±100ppm/°C Molded SMD Paper T/R")
      (fields
        (field (name "MANUFACTURER") "Vishay")
        (field (name "MANUFACTURER PART NUMBER") "CRCW080510K0FKEAC")
      )
      (libsource (lib "BMS_Slave") (part "CRCW060310K0FKEAC"))
    )
    (comp (ref "R55")
      (value "475R")
      (footprint "BMS_Slave:RESC1608X55N")
      (description "Res Thick Film 0603 1/8W ±100ppm/°C Molded SMD Paper T/R")
      (fields
        (field (name "MANUFACTURER") "Vishay")
        (field (name "MANUFACTURER PART NUMBER") "CRCW080510K0FKEAC")
      )
      (libsource (lib "BMS_Slave") (part "CRCW060310K0FKEAC"))
    )
    (comp (ref "R56")
      (value "475R")
      (footprint "BMS_Slave:RESC1608X55N")
      (description "Res Thick Film 0603 1/8W ±100ppm/°C Molded SMD Paper T/R")
      (fields
        (field (name "MANUFACTURER") "Vishay")
        (field (name "MANUFACTURER PART NUMBER") "CRCW080510K0FKEAC")
      )
      (libsource (lib "BMS_Slave") (part "CRCW060310K0FKEAC"))
    )
    (comp (ref "R57")
      (value "475R")
      (footprint "BMS_Slave:RESC1608X55N")
      (description "Res Thick Film 0603 1/8W ±100ppm/°C Molded SMD Paper T/R")
      (fields
        (field (name "MANUFACTURER") "Vishay")
        (field (name "MANUFACTURER PART NUMBER") "CRCW080510K0FKEAC")
      )
      (libsource (lib "BMS_Slave") (part "CRCW060310K0FKEAC"))
    )
    (comp (ref "R58")
      (value "475R")
      (footprint "BMS_Slave:RESC1608X55N")
      (description "Res Thick Film 0603 1/8W ±100ppm/°C Molded SMD Paper T/R")
      (fields
        (field (name "MANUFACTURER") "Vishay")
        (field (name "MANUFACTURER PART NUMBER") "CRCW080510K0FKEAC")
      )
      (libsource (lib "BMS_Slave") (part "CRCW060310K0FKEAC"))
    )
    (comp (ref "R59")
      (value "475R")
      (footprint "BMS_Slave:RESC1608X55N")
      (description "Res Thick Film 0603 1/8W ±100ppm/°C Molded SMD Paper T/R")
      (fields
        (field (name "MANUFACTURER") "Vishay")
        (field (name "MANUFACTURER PART NUMBER") "CRCW080510K0FKEAC")
      )
      (libsource (lib "BMS_Slave") (part "CRCW060310K0FKEAC"))
    )
    (comp (ref "R60")
      (value "475R")
      (footprint "BMS_Slave:RESC1608X55N")
      (description "Res Thick Film 0603 1/8W ±100ppm/°C Molded SMD Paper T/R")
      (fields
        (field (name "MANUFACTURER") "Vishay")
        (field (name "MANUFACTURER PART NUMBER") "CRCW080510K0FKEAC")
      )
      (libsource (lib "BMS_Slave") (part "CRCW060310K0FKEAC"))
    )
    (comp (ref "R61")
      (value "475R")
      (footprint "BMS_Slave:RESC1608X55N")
      (description "Res Thick Film 0603 1/8W ±100ppm/°C Molded SMD Paper T/R")
      (fields
        (field (name "MANUFACTURER") "Vishay")
        (field (name "MANUFACTURER PART NUMBER") "CRCW080510K0FKEAC")
      )
      (libsource (lib "BMS_Slave") (part "CRCW060310K0FKEAC"))
    )
    (comp (ref "R62")
      (value "475R")
      (footprint "BMS_Slave:RESC1608X55N")
      (description "Res Thick Film 0603 1/8W ±100ppm/°C Molded SMD Paper T/R")
      (fields
        (field (name "MANUFACTURER") "Vishay")
        (field (name "MANUFACTURER PART NUMBER") "CRCW080510K0FKEAC")
      )
      (libsource (lib "BMS_Slave") (part "CRCW060310K0FKEAC"))
    )
    (comp (ref "R63")
      (value "0R")
      (footprint "BMS_Slave:RESC1608X55N")
      (description "Res Thick Film 0603 1/8W ±100ppm/°C Molded SMD Paper T/R")
      (fields
        (field (name "MANUFACTURER") "Vishay")
        (field (name "MANUFACTURER PART NUMBER") "CRCW080510K0FKEAC")
      )
      (libsource (lib "BMS_Slave") (part "CRCW060310K0FKEAC"))
    )
    (comp (ref "R64")
      (value "475R")
      (footprint "BMS_Slave:RESC1608X55N")
      (description "Res Thick Film 0603 1/8W ±100ppm/°C Molded SMD Paper T/R")
      (fields
        (field (name "MANUFACTURER") "Vishay")
        (field (name "MANUFACTURER PART NUMBER") "CRCW080510K0FKEAC")
      )
      (libsource (lib "BMS_Slave") (part "CRCW060310K0FKEAC"))
    )
    (comp (ref "R65")
      (value "475R")
      (footprint "BMS_Slave:RESC1608X55N")
      (description "Res Thick Film 0603 1/8W ±100ppm/°C Molded SMD Paper T/R")
      (fields
        (field (name "MANUFACTURER") "Vishay")
        (field (name "MANUFACTURER PART NUMBER") "CRCW080510K0FKEAC")
      )
      (libsource (lib "BMS_Slave") (part "CRCW060310K0FKEAC"))
    )
    (comp (ref "R66")
      (value "475R")
      (footprint "BMS_Slave:RESC1608X55N")
      (description "Res Thick Film 0603 1/8W ±100ppm/°C Molded SMD Paper T/R")
      (fields
        (field (name "MANUFACTURER") "Vishay")
        (field (name "MANUFACTURER PART NUMBER") "CRCW080510K0FKEAC")
      )
      (libsource (lib "BMS_Slave") (part "CRCW060310K0FKEAC"))
    )
    (comp (ref "R67")
      (value "475R")
      (footprint "BMS_Slave:RESC1608X55N")
      (description "Res Thick Film 0603 1/8W ±100ppm/°C Molded SMD Paper T/R")
      (fields
        (field (name "MANUFACTURER") "Vishay")
        (field (name "MANUFACTURER PART NUMBER") "CRCW080510K0FKEAC")
      )
      (libsource (lib "BMS_Slave") (part "CRCW060310K0FKEAC"))
    )
    (comp (ref "R68")
      (value "475R")
      (footprint "BMS_Slave:RESC1608X55N")
      (description "Res Thick Film 0603 1/8W ±100ppm/°C Molded SMD Paper T/R")
      (fields
        (field (name "MANUFACTURER") "Vishay")
        (field (name "MANUFACTURER PART NUMBER") "CRCW080510K0FKEAC")
      )
      (libsource (lib "BMS_Slave") (part "CRCW060310K0FKEAC"))
    )
    (comp (ref "R69")
      (value "475R")
      (footprint "BMS_Slave:RESC1608X55N")
      (description "Res Thick Film 0603 1/8W ±100ppm/°C Molded SMD Paper T/R")
      (fields
        (field (name "MANUFACTURER") "Vishay")
        (field (name "MANUFACTURER PART NUMBER") "CRCW080510K0FKEAC")
      )
      (libsource (lib "BMS_Slave") (part "CRCW060310K0FKEAC"))
    )
    (comp (ref "R70")
      (value "475R")
      (footprint "BMS_Slave:RESC1608X55N")
      (description "Res Thick Film 0603 1/8W ±100ppm/°C Molded SMD Paper T/R")
      (fields
        (field (name "MANUFACTURER") "Vishay")
        (field (name "MANUFACTURER PART NUMBER") "CRCW080510K0FKEAC")
      )
      (libsource (lib "BMS_Slave") (part "CRCW060310K0FKEAC"))
    )
    (comp (ref "R71")
      (value "475R")
      (footprint "BMS_Slave:RESC1608X55N")
      (description "Res Thick Film 0603 1/8W ±100ppm/°C Molded SMD Paper T/R")
      (fields
        (field (name "MANUFACTURER") "Vishay")
        (field (name "MANUFACTURER PART NUMBER") "CRCW080510K0FKEAC")
      )
      (libsource (lib "BMS_Slave") (part "CRCW060310K0FKEAC"))
    )
    (comp (ref "R72")
      (value "475R")
      (footprint "BMS_Slave:RESC1608X55N")
      (description "Res Thick Film 0603 1/8W ±100ppm/°C Molded SMD Paper T/R")
      (fields
        (field (name "MANUFACTURER") "Vishay")
        (field (name "MANUFACTURER PART NUMBER") "CRCW080510K0FKEAC")
      )
      (libsource (lib "BMS_Slave") (part "CRCW060310K0FKEAC"))
    )
    (comp (ref "R73")
      (value "475R")
      (footprint "BMS_Slave:RESC1608X55N")
      (description "Res Thick Film 0603 1/8W ±100ppm/°C Molded SMD Paper T/R")
      (fields
        (field (name "MANUFACTURER") "Vishay")
        (field (name "MANUFACTURER PART NUMBER") "CRCW080510K0FKEAC")
      )
      (libsource (lib "BMS_Slave") (part "CRCW060310K0FKEAC"))
    )
    (comp (ref "R74")
      (value "475R")
      (footprint "BMS_Slave:RESC1608X55N")
      (description "Res Thick Film 0603 1/8W ±100ppm/°C Molded SMD Paper T/R")
      (fields
        (field (name "MANUFACTURER") "Vishay")
        (field (name "MANUFACTURER PART NUMBER") "CRCW080510K0FKEAC")
      )
      (libsource (lib "BMS_Slave") (part "CRCW060310K0FKEAC"))
    )
    (comp (ref "R75")
      (value "475R")
      (footprint "BMS_Slave:RESC1608X55N")
      (description "Res Thick Film 0603 1/8W ±100ppm/°C Molded SMD Paper T/R")
      (fields
        (field (name "MANUFACTURER") "Vishay")
        (field (name "MANUFACTURER PART NUMBER") "CRCW080510K0FKEAC")
      )
      (libsource (lib "BMS_Slave") (part "CRCW060310K0FKEAC"))
    )
    (comp (ref "R76")
      (value "CRCW251233R0FKEG")
      (footprint "BMS_Slave:RESC6332X70N")
      (description "33Ohm, 1%, 1W, Resistor")
      (libsource (lib "BMS_Slave") (part "CRCW251233R0FKEG"))
    )
    (comp (ref "R77")
      (value "CRCW251233R0FKEG")
      (footprint "BMS_Slave:RESC6332X70N")
      (description "33Ohm, 1%, 1W, Resistor")
      (libsource (lib "BMS_Slave") (part "CRCW251233R0FKEG"))
    )
    (comp (ref "R78")
      (value "CRCW251233R0FKEG")
      (footprint "BMS_Slave:RESC6332X70N")
      (description "33Ohm, 1%, 1W, Resistor")
      (libsource (lib "BMS_Slave") (part "CRCW251233R0FKEG"))
    )
    (comp (ref "R79")
      (value "CRCW251233R0FKEG")
      (footprint "BMS_Slave:RESC6332X70N")
      (description "33Ohm, 1%, 1W, Resistor")
      (libsource (lib "BMS_Slave") (part "CRCW251233R0FKEG"))
    )
    (comp (ref "R80")
      (value "CRCW251233R0FKEG")
      (footprint "BMS_Slave:RESC6332X70N")
      (description "33Ohm, 1%, 1W, Resistor")
      (libsource (lib "BMS_Slave") (part "CRCW251233R0FKEG"))
    )
    (comp (ref "R81")
      (value "CRCW251233R0FKEG")
      (footprint "BMS_Slave:RESC6332X70N")
      (description "33Ohm, 1%, 1W, Resistor")
      (libsource (lib "BMS_Slave") (part "CRCW251233R0FKEG"))
    )
    (comp (ref "R82")
      (value "CRCW251233R0FKEG")
      (footprint "BMS_Slave:RESC6332X70N")
      (description "33Ohm, 1%, 1W, Resistor")
      (libsource (lib "BMS_Slave") (part "CRCW251233R0FKEG"))
    )
    (comp (ref "R83")
      (value "CRCW251233R0FKEG")
      (footprint "BMS_Slave:RESC6332X70N")
      (description "33Ohm, 1%, 1W, Resistor")
      (libsource (lib "BMS_Slave") (part "CRCW251233R0FKEG"))
    )
    (comp (ref "R84")
      (value "CRCW251233R0FKEG")
      (footprint "BMS_Slave:RESC6332X70N")
      (description "33Ohm, 1%, 1W, Resistor")
      (libsource (lib "BMS_Slave") (part "CRCW251233R0FKEG"))
    )
    (comp (ref "R85")
      (value "CRCW251233R0FKEG")
      (footprint "BMS_Slave:RESC6332X70N")
      (description "33Ohm, 1%, 1W, Resistor")
      (libsource (lib "BMS_Slave") (part "CRCW251233R0FKEG"))
    )
    (comp (ref "R86")
      (value "CRCW251233R0FKEG")
      (footprint "BMS_Slave:RESC6332X70N")
      (description "33Ohm, 1%, 1W, Resistor")
      (libsource (lib "BMS_Slave") (part "CRCW251233R0FKEG"))
    )
    (comp (ref "R87")
      (value "CRCW251233R0FKEG")
      (footprint "BMS_Slave:RESC6332X70N")
      (description "33Ohm, 1%, 1W, Resistor")
      (libsource (lib "BMS_Slave") (part "CRCW251233R0FKEG"))
    )
    (comp (ref "R88")
      (value "CRCW251233R0FKEG")
      (footprint "BMS_Slave:RESC6332X70N")
      (description "33Ohm, 1%, 1W, Resistor")
      (libsource (lib "BMS_Slave") (part "CRCW251233R0FKEG"))
    )
    (comp (ref "R89")
      (value "CRCW251233R0FKEG")
      (footprint "BMS_Slave:RESC6332X70N")
      (description "33Ohm, 1%, 1W, Resistor")
      (libsource (lib "BMS_Slave") (part "CRCW251233R0FKEG"))
    )
    (comp (ref "R90")
      (value "CRCW251233R0FKEG")
      (footprint "BMS_Slave:RESC6332X70N")
      (description "33Ohm, 1%, 1W, Resistor")
      (libsource (lib "BMS_Slave") (part "CRCW251233R0FKEG"))
    )
    (comp (ref "R91")
      (value "CRCW251233R0FKEG")
      (footprint "BMS_Slave:RESC6332X70N")
      (description "33Ohm, 1%, 1W, Resistor")
      (libsource (lib "BMS_Slave") (part "CRCW251233R0FKEG"))
    )
    (comp (ref "R92")
      (value "CRCW251233R0FKEG")
      (footprint "BMS_Slave:RESC6332X70N")
      (description "33Ohm, 1%, 1W, Resistor")
      (libsource (lib "BMS_Slave") (part "CRCW251233R0FKEG"))
    )
    (comp (ref "R93")
      (value "CRCW251233R0FKEG")
      (footprint "BMS_Slave:RESC6332X70N")
      (description "33Ohm, 1%, 1W, Resistor")
      (libsource (lib "BMS_Slave") (part "CRCW251233R0FKEG"))
    )
    (comp (ref "R94")
      (value "CRCW251233R0FKEG")
      (footprint "BMS_Slave:RESC6332X70N")
      (description "33Ohm, 1%, 1W, Resistor")
      (libsource (lib "BMS_Slave") (part "CRCW251233R0FKEG"))
    )
    (comp (ref "R95")
      (value "CRCW251233R0FKEG")
      (footprint "BMS_Slave:RESC6332X70N")
      (description "33Ohm, 1%, 1W, Resistor")
      (libsource (lib "BMS_Slave") (part "CRCW251233R0FKEG"))
    )
    (comp (ref "R96")
      (value "CRCW251233R0FKEG")
      (footprint "BMS_Slave:RESC6332X70N")
      (description "33Ohm, 1%, 1W, Resistor")
      (libsource (lib "BMS_Slave") (part "CRCW251233R0FKEG"))
    )
    (comp (ref "R97")
      (value "CRCW251233R0FKEG")
      (footprint "BMS_Slave:RESC6332X70N")
      (description "33Ohm, 1%, 1W, Resistor")
      (libsource (lib "BMS_Slave") (part "CRCW251233R0FKEG"))
    )
    (comp (ref "R98")
      (value "CRCW251233R0FKEG")
      (footprint "BMS_Slave:RESC6332X70N")
      (description "33Ohm, 1%, 1W, Resistor")
      (libsource (lib "BMS_Slave") (part "CRCW251233R0FKEG"))
    )
    (comp (ref "R99")
      (value "CRCW251233R0FKEG")
      (footprint "BMS_Slave:RESC6332X70N")
      (description "33Ohm, 1%, 1W, Resistor")
      (libsource (lib "BMS_Slave") (part "CRCW251233R0FKEG"))
    )
    (comp (ref "R100")
      (value "100R")
      (footprint "BMS_Slave:RESC1608X55N")
      (description "Res Thick Film 0603 1/8W ±100ppm/°C Molded SMD Paper T/R")
      (fields
        (field (name "MANUFACTURER") "Vishay")
        (field (name "MANUFACTURER PART NUMBER") "CRCW080510K0FKEAC")
      )
      (libsource (lib "BMS_Slave") (part "CRCW060310K0FKEAC"))
    )
    (comp (ref "R101")
      (value "100R")
      (footprint "BMS_Slave:RESC1608X55N")
      (description "Res Thick Film 0603 1/8W ±100ppm/°C Molded SMD Paper T/R")
      (fields
        (field (name "MANUFACTURER") "Vishay")
        (field (name "MANUFACTURER PART NUMBER") "CRCW080510K0FKEAC")
      )
      (libsource (lib "BMS_Slave") (part "CRCW060310K0FKEAC"))
    )
    (comp (ref "R102")
      (value "10k")
      (footprint "BMS_Slave:RESC1608X55N")
      (description "Res Thick Film 0603 1/8W ±100ppm/°C Molded SMD Paper T/R")
      (fields
        (field (name "MANUFACTURER") "Vishay")
        (field (name "MANUFACTURER PART NUMBER") "CRCW080510K0FKEAC")
      )
      (libsource (lib "BMS_Slave") (part "CRCW060310K0FKEAC"))
    )
    (comp (ref "R103")
      (value "10k")
      (footprint "BMS_Slave:RESC1608X55N")
      (description "Res Thick Film 0603 1/8W ±100ppm/°C Molded SMD Paper T/R")
      (fields
        (field (name "MANUFACTURER") "Vishay")
        (field (name "MANUFACTURER PART NUMBER") "CRCW080510K0FKEAC")
      )
      (libsource (lib "BMS_Slave") (part "CRCW060310K0FKEAC"))
    )
    (comp (ref "R104")
      (value "10k")
      (footprint "BMS_Slave:RESC1608X55N")
      (description "Res Thick Film 0603 1/8W ±100ppm/°C Molded SMD Paper T/R")
      (fields
        (field (name "MANUFACTURER") "Vishay")
        (field (name "MANUFACTURER PART NUMBER") "CRCW080510K0FKEAC")
      )
      (libsource (lib "BMS_Slave") (part "CRCW060310K0FKEAC"))
    )
    (comp (ref "R105")
      (value "10k")
      (footprint "BMS_Slave:RESC1608X55N")
      (description "Res Thick Film 0603 1/8W ±100ppm/°C Molded SMD Paper T/R")
      (fields
        (field (name "MANUFACTURER") "Vishay")
        (field (name "MANUFACTURER PART NUMBER") "CRCW080510K0FKEAC")
      )
      (libsource (lib "BMS_Slave") (part "CRCW060310K0FKEAC"))
    )
    (comp (ref "R106")
      (value "10k")
      (footprint "BMS_Slave:RESC1608X55N")
      (description "Res Thick Film 0603 1/8W ±100ppm/°C Molded SMD Paper T/R")
      (fields
        (field (name "MANUFACTURER") "Vishay")
        (field (name "MANUFACTURER PART NUMBER") "CRCW080510K0FKEAC")
      )
      (libsource (lib "BMS_Slave") (part "CRCW060310K0FKEAC"))
    )
    (comp (ref "R107")
      (value "10k")
      (footprint "BMS_Slave:RESC1608X55N")
      (description "Res Thick Film 0603 1/8W ±100ppm/°C Molded SMD Paper T/R")
      (fields
        (field (name "MANUFACTURER") "Vishay")
        (field (name "MANUFACTURER PART NUMBER") "CRCW080510K0FKEAC")
      )
      (libsource (lib "BMS_Slave") (part "CRCW060310K0FKEAC"))
    )
    (comp (ref "R108")
      (value "10k")
      (footprint "BMS_Slave:RESC1608X55N")
      (description "Res Thick Film 0603 1/8W ±100ppm/°C Molded SMD Paper T/R")
      (fields
        (field (name "MANUFACTURER") "Vishay")
        (field (name "MANUFACTURER PART NUMBER") "CRCW080510K0FKEAC")
      )
      (libsource (lib "BMS_Slave") (part "CRCW060310K0FKEAC"))
    )
    (comp (ref "R109")
      (value "10k")
      (footprint "BMS_Slave:RESC1608X55N")
      (description "Res Thick Film 0603 1/8W ±100ppm/°C Molded SMD Paper T/R")
      (fields
        (field (name "MANUFACTURER") "Vishay")
        (field (name "MANUFACTURER PART NUMBER") "CRCW080510K0FKEAC")
      )
      (libsource (lib "BMS_Slave") (part "CRCW060310K0FKEAC"))
    )
    (comp (ref "R110")
      (value "10k")
      (footprint "BMS_Slave:RESC1608X55N")
      (description "Res Thick Film 0603 1/8W ±100ppm/°C Molded SMD Paper T/R")
      (fields
        (field (name "MANUFACTURER") "Vishay")
        (field (name "MANUFACTURER PART NUMBER") "CRCW080510K0FKEAC")
      )
      (libsource (lib "BMS_Slave") (part "CRCW060310K0FKEAC"))
    )
    (comp (ref "R111")
      (value "10k")
      (footprint "BMS_Slave:RESC1608X55N")
      (description "Res Thick Film 0603 1/8W ±100ppm/°C Molded SMD Paper T/R")
      (fields
        (field (name "MANUFACTURER") "Vishay")
        (field (name "MANUFACTURER PART NUMBER") "CRCW080510K0FKEAC")
      )
      (libsource (lib "BMS_Slave") (part "CRCW060310K0FKEAC"))
    )
    (comp (ref "R112")
      (value "49.9R")
      (footprint "BMS_Slave:RESC1608X55N")
      (description "Res Thick Film 0603 1/8W ±100ppm/°C Molded SMD Paper T/R")
      (fields
        (field (name "MANUFACTURER") "Vishay")
        (field (name "MANUFACTURER PART NUMBER") "CRCW080510K0FKEAC")
      )
      (libsource (lib "BMS_Slave") (part "CRCW060310K0FKEAC"))
    )
    (comp (ref "R113")
      (value "1k")
      (footprint "BMS_Slave:RESC1608X55N")
      (description "Res Thick Film 0603 1/8W ±100ppm/°C Molded SMD Paper T/R")
      (fields
        (field (name "MANUFACTURER") "Vishay")
        (field (name "MANUFACTURER PART NUMBER") "CRCW080510K0FKEAC")
      )
      (libsource (lib "BMS_Slave") (part "CRCW060310K0FKEAC"))
    )
    (comp (ref "R114")
      (value "49.9R")
      (footprint "BMS_Slave:RESC1608X55N")
      (description "Res Thick Film 0603 1/8W ±100ppm/°C Molded SMD Paper T/R")
      (fields
        (field (name "MANUFACTURER") "Vishay")
        (field (name "MANUFACTURER PART NUMBER") "CRCW080510K0FKEAC")
      )
      (libsource (lib "BMS_Slave") (part "CRCW060310K0FKEAC"))
    )
    (comp (ref "R115")
      (value "49.9R")
      (footprint "BMS_Slave:RESC1608X55N")
      (description "Res Thick Film 0603 1/8W ±100ppm/°C Molded SMD Paper T/R")
      (fields
        (field (name "MANUFACTURER") "Vishay")
        (field (name "MANUFACTURER PART NUMBER") "CRCW080510K0FKEAC")
      )
      (libsource (lib "BMS_Slave") (part "CRCW060310K0FKEAC"))
    )
    (comp (ref "R116")
      (value "1k")
      (footprint "BMS_Slave:RESC1608X55N")
      (description "Res Thick Film 0603 1/8W ±100ppm/°C Molded SMD Paper T/R")
      (fields
        (field (name "MANUFACTURER") "Vishay")
        (field (name "MANUFACTURER PART NUMBER") "CRCW080510K0FKEAC")
      )
      (libsource (lib "BMS_Slave") (part "CRCW060310K0FKEAC"))
    )
    (comp (ref "R117")
      (value "1k")
      (footprint "BMS_Slave:RESC1608X55N")
      (description "Res Thick Film 0603 1/8W ±100ppm/°C Molded SMD Paper T/R")
      (fields
        (field (name "MANUFACTURER") "Vishay")
        (field (name "MANUFACTURER PART NUMBER") "CRCW080510K0FKEAC")
      )
      (libsource (lib "BMS_Slave") (part "CRCW060310K0FKEAC"))
    )
    (comp (ref "R118")
      (value "1k")
      (footprint "BMS_Slave:RESC1608X55N")
      (description "Res Thick Film 0603 1/8W ±100ppm/°C Molded SMD Paper T/R")
      (fields
        (field (name "MANUFACTURER") "Vishay")
        (field (name "MANUFACTURER PART NUMBER") "CRCW080510K0FKEAC")
      )
      (libsource (lib "BMS_Slave") (part "CRCW060310K0FKEAC"))
    )
    (comp (ref "R119")
      (value "49.9R")
      (footprint "BMS_Slave:RESC1608X55N")
      (description "Res Thick Film 0603 1/8W ±100ppm/°C Molded SMD Paper T/R")
      (fields
        (field (name "MANUFACTURER") "Vishay")
        (field (name "MANUFACTURER PART NUMBER") "CRCW080510K0FKEAC")
      )
      (libsource (lib "BMS_Slave") (part "CRCW060310K0FKEAC"))
    )
    (comp (ref "R120")
      (value "49.9R")
      (footprint "BMS_Slave:RESC1608X55N")
      (description "Res Thick Film 0603 1/8W ±100ppm/°C Molded SMD Paper T/R")
      (fields
        (field (name "MANUFACTURER") "Vishay")
        (field (name "MANUFACTURER PART NUMBER") "CRCW080510K0FKEAC")
      )
      (libsource (lib "BMS_Slave") (part "CRCW060310K0FKEAC"))
    )
    (comp (ref "R121")
      (value "100R")
      (footprint "BMS_Slave:RESC1608X55N")
      (description "Res Thick Film 0603 1/8W ±100ppm/°C Molded SMD Paper T/R")
      (fields
        (field (name "MANUFACTURER") "Vishay")
        (field (name "MANUFACTURER PART NUMBER") "CRCW080510K0FKEAC")
      )
      (libsource (lib "BMS_Slave") (part "CRCW060310K0FKEAC"))
    )
    (comp (ref "R122")
      (value "100R")
      (footprint "BMS_Slave:RESC1608X55N")
      (description "Res Thick Film 0603 1/8W ±100ppm/°C Molded SMD Paper T/R")
      (fields
        (field (name "MANUFACTURER") "Vishay")
        (field (name "MANUFACTURER PART NUMBER") "CRCW080510K0FKEAC")
      )
      (libsource (lib "BMS_Slave") (part "CRCW060310K0FKEAC"))
    )
    (comp (ref "R123")
      (value "49.9R")
      (footprint "BMS_Slave:RESC1608X55N")
      (description "Res Thick Film 0603 1/8W ±100ppm/°C Molded SMD Paper T/R")
      (fields
        (field (name "MANUFACTURER") "Vishay")
        (field (name "MANUFACTURER PART NUMBER") "CRCW080510K0FKEAC")
      )
      (libsource (lib "BMS_Slave") (part "CRCW060310K0FKEAC"))
    )
    (comp (ref "R124")
      (value "49.9R")
      (footprint "BMS_Slave:RESC1608X55N")
      (description "Res Thick Film 0603 1/8W ±100ppm/°C Molded SMD Paper T/R")
      (fields
        (field (name "MANUFACTURER") "Vishay")
        (field (name "MANUFACTURER PART NUMBER") "CRCW080510K0FKEAC")
      )
      (libsource (lib "BMS_Slave") (part "CRCW060310K0FKEAC"))
    )
    (comp (ref "R125")
      (value "49.9R")
      (footprint "BMS_Slave:RESC1608X55N")
      (description "Res Thick Film 0603 1/8W ±100ppm/°C Molded SMD Paper T/R")
      (fields
        (field (name "MANUFACTURER") "Vishay")
        (field (name "MANUFACTURER PART NUMBER") "CRCW080510K0FKEAC")
      )
      (libsource (lib "BMS_Slave") (part "CRCW060310K0FKEAC"))
    )
    (comp (ref "T1")
      (value "HX1188NLT")
      (footprint "BMS_Slave:HX1188NLT")
      (description "Transformer")
      (fields (field (name "MOUSER PART NUMBER") "673-HX1188NLT"))
      (libsource (lib "BMS_Slave") (part "HX1188NLT"))
    )
    (comp (ref "T2")
      (value "HX1188NLT")
      (footprint "BMS_Slave:HX1188NLT")
      (description "Transformer")
      (fields (field (name "MOUSER PART NUMBER") "673-HX1188NLT"))
      (libsource (lib "BMS_Slave") (part "HX1188NLT"))
    )
    (comp (ref "U1")
      (value "LTC6811-1")
      (footprint "SamacSys:SOP50P780X200-48N")
      (description "Integrated Circuit")
      (libsource (lib "BMS_Slave") (part "LTC6811-1"))
    )
    (comp (ref "U2")
      (value "LTC6811-1")
      (footprint "SamacSys:SOP50P780X200-48N")
      (description "Integrated Circuit")
      (libsource (lib "BMS_Slave") (part "LTC6811-1"))
    )
  )
  (nets
    (net (code "1") (name "/ISOSPI_A_N") (class "Default")
      (node (ref "R125") (pin "2") (pinfunction "2_2") (pintype "passive"))
      (node (ref "T1") (pin "16") (pinfunction "TX+_16") (pintype "passive"))
      (node (ref "U1") (pin "41") (pinfunction "CSB_(IMA)*_41") (pintype "passive"))
    )
    (net (code "2") (name "/ISOSPI_A_P") (class "Default")
      (node (ref "R115") (pin "1") (pinfunction "1_1") (pintype "passive"))
      (node (ref "T1") (pin "14") (pinfunction "TX-_14") (pintype "passive"))
      (node (ref "U1") (pin "42") (pinfunction "SCK_(IPA)*_42") (pintype "passive"))
    )
    (net (code "3") (name "/ISOSPI_B_N") (class "Default")
      (node (ref "R112") (pin "2") (pinfunction "2_2") (pintype "passive"))
      (node (ref "T2") (pin "16") (pinfunction "TX+_16") (pintype "passive"))
      (node (ref "U2") (pin "47") (pinfunction "IMB_47") (pintype "passive"))
    )
    (net (code "4") (name "/ISOSPI_B_P") (class "Default")
      (node (ref "R114") (pin "1") (pinfunction "1_1") (pintype "passive"))
      (node (ref "T2") (pin "14") (pinfunction "TX-_14") (pintype "passive"))
      (node (ref "U2") (pin "48") (pinfunction "IPB_48") (pintype "passive"))
    )
    (net (code "5") (name "/ISO_SPI_BOTTOM_N") (class "Default")
      (node (ref "FL1") (pin "1") (pinfunction "1_1") (pintype "passive"))
      (node (ref "R120") (pin "1") (pinfunction "1_1") (pintype "passive"))
      (node (ref "U1") (pin "47") (pinfunction "IMB_47") (pintype "passive"))
    )
    (net (code "6") (name "/ISO_SPI_BOTTOM_P") (class "Default")
      (node (ref "FL1") (pin "2") (pinfunction "2_2") (pintype "passive"))
      (node (ref "R119") (pin "1") (pinfunction "1_1") (pintype "passive"))
      (node (ref "U1") (pin "48") (pinfunction "IPB_48") (pintype "passive"))
    )
    (net (code "7") (name "/ISO_SPI_MED_N") (class "Default")
      (node (ref "C73") (pin "2") (pinfunction "2_2") (pintype "passive"))
      (node (ref "FL1") (pin "4") (pinfunction "4_4") (pintype "passive"))
    )
    (net (code "8") (name "/ISO_SPI_MED_P") (class "Default")
      (node (ref "C72") (pin "2") (pinfunction "2_2") (pintype "passive"))
      (node (ref "FL1") (pin "3") (pinfunction "3_3") (pintype "passive"))
    )
    (net (code "9") (name "/ISO_SPI_TOP_N") (class "Default")
      (node (ref "C73") (pin "1") (pinfunction "1_1") (pintype "passive"))
      (node (ref "R124") (pin "1") (pinfunction "1_1") (pintype "passive"))
      (node (ref "U2") (pin "41") (pinfunction "CSB_(IMA)*_41") (pintype "passive"))
    )
    (net (code "10") (name "/ISO_SPI_TOP_P") (class "Default")
      (node (ref "C72") (pin "1") (pinfunction "1_1") (pintype "passive"))
      (node (ref "R123") (pin "2") (pinfunction "2_2") (pintype "passive"))
      (node (ref "U2") (pin "42") (pinfunction "SCK_(IPA)*_42") (pintype "passive"))
    )
    (net (code "11") (name "/PORTA_N") (class "Default")
      (node (ref "J3") (pin "1") (pinfunction "1_1") (pintype "passive"))
      (node (ref "T1") (pin "1") (pinfunction "TD+_1") (pintype "passive"))
    )
    (net (code "12") (name "/PORTA_P") (class "Default")
      (node (ref "J3") (pin "2") (pinfunction "2_2") (pintype "passive"))
      (node (ref "T1") (pin "3") (pinfunction "TD-_3") (pintype "passive"))
    )
    (net (code "13") (name "/PORTB_N") (class "Default")
      (node (ref "J4") (pin "1") (pinfunction "1_1") (pintype "passive"))
      (node (ref "T2") (pin "1") (pinfunction "TD+_1") (pintype "passive"))
    )
    (net (code "14") (name "/PORTB_P") (class "Default")
      (node (ref "J4") (pin "2") (pinfunction "2_2") (pintype "passive"))
      (node (ref "T2") (pin "3") (pinfunction "TD-_3") (pintype "passive"))
    )
    (net (code "15") (name "/SHIELD1") (class "Default")
      (node (ref "C103") (pin "2") (pinfunction "2_2") (pintype "passive"))
      (node (ref "J3") (pin "10") (pinfunction "10_10") (pintype "passive"))
      (node (ref "J3") (pin "9") (pinfunction "9_9") (pintype "passive"))
    )
    (net (code "16") (name "/SHIELD2") (class "Default")
      (node (ref "C102") (pin "2") (pinfunction "2_2") (pintype "passive"))
      (node (ref "J4") (pin "10") (pinfunction "10_10") (pintype "passive"))
      (node (ref "J4") (pin "9") (pinfunction "9_9") (pintype "passive"))
    )
    (net (code "17") (name "5V") (class "Default")
      (node (ref "C68") (pin "1") (pinfunction "1_1") (pintype "passive"))
      (node (ref "JP2") (pin "1") (pinfunction "1_1") (pintype "passive"))
      (node (ref "Q26") (pin "2") (pinfunction "E_2") (pintype "passive"))
      (node (ref "U1") (pin "37") (pinfunction "VREG_37") (pintype "passive"))
      (node (ref "U1") (pin "40") (pinfunction "ISOMD_40") (pintype "passive"))
    )
    (net (code "18") (name "C0") (class "Default")
      (node (ref "C77") (pin "1") (pinfunction "1_1") (pintype "passive"))
      (node (ref "C78") (pin "2") (pinfunction "2_2") (pintype "passive"))
      (node (ref "R1") (pin "1") (pinfunction "1_1") (pintype "passive"))
      (node (ref "U1") (pin "26") (pinfunction "C0_26") (pintype "passive"))
    )
    (net (code "19") (name "C1") (class "Default")
      (node (ref "C25") (pin "1") (pinfunction "1_1") (pintype "passive"))
      (node (ref "C78") (pin "1") (pinfunction "1_1") (pintype "passive"))
      (node (ref "C79") (pin "2") (pinfunction "2_2") (pintype "passive"))
      (node (ref "R3") (pin "1") (pinfunction "1_1") (pintype "passive"))
      (node (ref "U1") (pin "24") (pinfunction "C1_24") (pintype "passive"))
    )
    (net (code "20") (name "C2") (class "Default")
      (node (ref "C26") (pin "1") (pinfunction "1_1") (pintype "passive"))
      (node (ref "C79") (pin "1") (pinfunction "1_1") (pintype "passive"))
      (node (ref "C80") (pin "2") (pinfunction "2_2") (pintype "passive"))
      (node (ref "R5") (pin "1") (pinfunction "1_1") (pintype "passive"))
      (node (ref "U1") (pin "22") (pinfunction "C2_22") (pintype "passive"))
    )
    (net (code "21") (name "C3") (class "Default")
      (node (ref "C27") (pin "1") (pinfunction "1_1") (pintype "passive"))
      (node (ref "C80") (pin "1") (pinfunction "1_1") (pintype "passive"))
      (node (ref "C81") (pin "2") (pinfunction "2_2") (pintype "passive"))
      (node (ref "R7") (pin "1") (pinfunction "1_1") (pintype "passive"))
      (node (ref "U1") (pin "20") (pinfunction "C3_20") (pintype "passive"))
    )
    (net (code "22") (name "C4") (class "Default")
      (node (ref "C28") (pin "1") (pinfunction "1_1") (pintype "passive"))
      (node (ref "C81") (pin "1") (pinfunction "1_1") (pintype "passive"))
      (node (ref "C82") (pin "2") (pinfunction "2_2") (pintype "passive"))
      (node (ref "R9") (pin "1") (pinfunction "1_1") (pintype "passive"))
      (node (ref "U1") (pin "18") (pinfunction "C4_18") (pintype "passive"))
    )
    (net (code "23") (name "C5") (class "Default")
      (node (ref "C29") (pin "1") (pinfunction "1_1") (pintype "passive"))
      (node (ref "C82") (pin "1") (pinfunction "1_1") (pintype "passive"))
      (node (ref "C83") (pin "2") (pinfunction "2_2") (pintype "passive"))
      (node (ref "R11") (pin "1") (pinfunction "1_1") (pintype "passive"))
      (node (ref "U1") (pin "16") (pinfunction "C5_16") (pintype "passive"))
    )
    (net (code "24") (name "C6") (class "Default")
      (node (ref "C30") (pin "1") (pinfunction "1_1") (pintype "passive"))
      (node (ref "C83") (pin "1") (pinfunction "1_1") (pintype "passive"))
      (node (ref "C84") (pin "2") (pinfunction "2_2") (pintype "passive"))
      (node (ref "R13") (pin "1") (pinfunction "1_1") (pintype "passive"))
      (node (ref "U1") (pin "14") (pinfunction "C6_14") (pintype "passive"))
    )
    (net (code "25") (name "C7") (class "Default")
      (node (ref "C31") (pin "1") (pinfunction "1_1") (pintype "passive"))
      (node (ref "C84") (pin "1") (pinfunction "1_1") (pintype "passive"))
      (node (ref "C85") (pin "2") (pinfunction "2_2") (pintype "passive"))
      (node (ref "R15") (pin "1") (pinfunction "1_1") (pintype "passive"))
      (node (ref "U1") (pin "12") (pinfunction "C7_12") (pintype "passive"))
    )
    (net (code "26") (name "C8") (class "Default")
      (node (ref "C32") (pin "1") (pinfunction "1_1") (pintype "passive"))
      (node (ref "C85") (pin "1") (pinfunction "1_1") (pintype "passive"))
      (node (ref "C86") (pin "2") (pinfunction "2_2") (pintype "passive"))
      (node (ref "R17") (pin "1") (pinfunction "1_1") (pintype "passive"))
      (node (ref "U1") (pin "10") (pinfunction "C8_10") (pintype "passive"))
    )
    (net (code "27") (name "C9") (class "Default")
      (node (ref "C33") (pin "1") (pinfunction "1_1") (pintype "passive"))
      (node (ref "C86") (pin "1") (pinfunction "1_1") (pintype "passive"))
      (node (ref "C87") (pin "2") (pinfunction "2_2") (pintype "passive"))
      (node (ref "R19") (pin "1") (pinfunction "1_1") (pintype "passive"))
      (node (ref "U1") (pin "8") (pinfunction "C9_8") (pintype "passive"))
    )
    (net (code "28") (name "C10") (class "Default")
      (node (ref "C34") (pin "1") (pinfunction "1_1") (pintype "passive"))
      (node (ref "C87") (pin "1") (pinfunction "1_1") (pintype "passive"))
      (node (ref "C88") (pin "2") (pinfunction "2_2") (pintype "passive"))
      (node (ref "R21") (pin "1") (pinfunction "1_1") (pintype "passive"))
      (node (ref "U1") (pin "6") (pinfunction "C10_6") (pintype "passive"))
    )
    (net (code "29") (name "C11") (class "Default")
      (node (ref "C35") (pin "1") (pinfunction "1_1") (pintype "passive"))
      (node (ref "C88") (pin "1") (pinfunction "1_1") (pintype "passive"))
      (node (ref "C89") (pin "2") (pinfunction "2_2") (pintype "passive"))
      (node (ref "R23") (pin "1") (pinfunction "1_1") (pintype "passive"))
      (node (ref "U1") (pin "4") (pinfunction "C11_4") (pintype "passive"))
    )
    (net (code "30") (name "C12") (class "Default")
      (node (ref "C36") (pin "1") (pinfunction "1_1") (pintype "passive"))
      (node (ref "C89") (pin "1") (pinfunction "1_1") (pintype "passive"))
      (node (ref "C90") (pin "2") (pinfunction "2_2") (pintype "passive"))
      (node (ref "R25") (pin "1") (pinfunction "1_1") (pintype "passive"))
      (node (ref "U1") (pin "2") (pinfunction "C12_2") (pintype "passive"))
      (node (ref "U2") (pin "26") (pinfunction "C0_26") (pintype "passive"))
    )
    (net (code "31") (name "C13") (class "Default")
      (node (ref "C37") (pin "1") (pinfunction "1_1") (pintype "passive"))
      (node (ref "C90") (pin "1") (pinfunction "1_1") (pintype "passive"))
      (node (ref "C91") (pin "2") (pinfunction "2_2") (pintype "passive"))
      (node (ref "R27") (pin "1") (pinfunction "1_1") (pintype "passive"))
      (node (ref "U2") (pin "24") (pinfunction "C1_24") (pintype "passive"))
    )
    (net (code "32") (name "C14") (class "Default")
      (node (ref "C38") (pin "1") (pinfunction "1_1") (pintype "passive"))
      (node (ref "C91") (pin "1") (pinfunction "1_1") (pintype "passive"))
      (node (ref "C92") (pin "2") (pinfunction "2_2") (pintype "passive"))
      (node (ref "R29") (pin "1") (pinfunction "1_1") (pintype "passive"))
      (node (ref "U2") (pin "22") (pinfunction "C2_22") (pintype "passive"))
    )
    (net (code "33") (name "C15") (class "Default")
      (node (ref "C39") (pin "1") (pinfunction "1_1") (pintype "passive"))
      (node (ref "C92") (pin "1") (pinfunction "1_1") (pintype "passive"))
      (node (ref "C93") (pin "2") (pinfunction "2_2") (pintype "passive"))
      (node (ref "R31") (pin "1") (pinfunction "1_1") (pintype "passive"))
      (node (ref "U2") (pin "20") (pinfunction "C3_20") (pintype "passive"))
    )
    (net (code "34") (name "C16") (class "Default")
      (node (ref "C40") (pin "1") (pinfunction "1_1") (pintype "passive"))
      (node (ref "C93") (pin "1") (pinfunction "1_1") (pintype "passive"))
      (node (ref "C94") (pin "2") (pinfunction "2_2") (pintype "passive"))
      (node (ref "R33") (pin "1") (pinfunction "1_1") (pintype "passive"))
      (node (ref "U2") (pin "18") (pinfunction "C4_18") (pintype "passive"))
    )
    (net (code "35") (name "C17") (class "Default")
      (node (ref "C41") (pin "1") (pinfunction "1_1") (pintype "passive"))
      (node (ref "C94") (pin "1") (pinfunction "1_1") (pintype "passive"))
      (node (ref "C95") (pin "2") (pinfunction "2_2") (pintype "passive"))
      (node (ref "R35") (pin "1") (pinfunction "1_1") (pintype "passive"))
      (node (ref "U2") (pin "16") (pinfunction "C5_16") (pintype "passive"))
    )
    (net (code "36") (name "C18") (class "Default")
      (node (ref "C42") (pin "1") (pinfunction "1_1") (pintype "passive"))
      (node (ref "C95") (pin "1") (pinfunction "1_1") (pintype "passive"))
      (node (ref "C96") (pin "2") (pinfunction "2_2") (pintype "passive"))
      (node (ref "R37") (pin "1") (pinfunction "1_1") (pintype "passive"))
      (node (ref "U2") (pin "14") (pinfunction "C6_14") (pintype "passive"))
    )
    (net (code "37") (name "C19") (class "Default")
      (node (ref "C43") (pin "1") (pinfunction "1_1") (pintype "passive"))
      (node (ref "C96") (pin "1") (pinfunction "1_1") (pintype "passive"))
      (node (ref "C97") (pin "2") (pinfunction "2_2") (pintype "passive"))
      (node (ref "R39") (pin "1") (pinfunction "1_1") (pintype "passive"))
      (node (ref "U2") (pin "12") (pinfunction "C7_12") (pintype "passive"))
    )
    (net (code "38") (name "C20") (class "Default")
      (node (ref "C44") (pin "1") (pinfunction "1_1") (pintype "passive"))
      (node (ref "C97") (pin "1") (pinfunction "1_1") (pintype "passive"))
      (node (ref "C98") (pin "2") (pinfunction "2_2") (pintype "passive"))
      (node (ref "R41") (pin "1") (pinfunction "1_1") (pintype "passive"))
      (node (ref "U2") (pin "10") (pinfunction "C8_10") (pintype "passive"))
    )
    (net (code "39") (name "C21") (class "Default")
      (node (ref "C45") (pin "1") (pinfunction "1_1") (pintype "passive"))
      (node (ref "C98") (pin "1") (pinfunction "1_1") (pintype "passive"))
      (node (ref "C99") (pin "2") (pinfunction "2_2") (pintype "passive"))
      (node (ref "R43") (pin "1") (pinfunction "1_1") (pintype "passive"))
      (node (ref "U2") (pin "8") (pinfunction "C9_8") (pintype "passive"))
    )
    (net (code "40") (name "C22") (class "Default")
      (node (ref "C100") (pin "2") (pinfunction "2_2") (pintype "passive"))
      (node (ref "C46") (pin "1") (pinfunction "1_1") (pintype "passive"))
      (node (ref "C99") (pin "1") (pinfunction "1_1") (pintype "passive"))
      (node (ref "R45") (pin "1") (pinfunction "1_1") (pintype "passive"))
      (node (ref "U2") (pin "6") (pinfunction "C10_6") (pintype "passive"))
    )
    (net (code "41") (name "C23") (class "Default")
      (node (ref "C100") (pin "1") (pinfunction "1_1") (pintype "passive"))
      (node (ref "C101") (pin "2") (pinfunction "2_2") (pintype "passive"))
      (node (ref "C47") (pin "1") (pinfunction "1_1") (pintype "passive"))
      (node (ref "R47") (pin "1") (pinfunction "1_1") (pintype "passive"))
      (node (ref "U2") (pin "4") (pinfunction "C11_4") (pintype "passive"))
    )
    (net (code "42") (name "C24") (class "Default")
      (node (ref "C101") (pin "1") (pinfunction "1_1") (pintype "passive"))
      (node (ref "C48") (pin "1") (pinfunction "1_1") (pintype "passive"))
      (node (ref "R49") (pin "1") (pinfunction "1_1") (pintype "passive"))
      (node (ref "U2") (pin "2") (pinfunction "C12_2") (pintype "passive"))
    )
    (net (code "43") (name "CELL0") (class "Default")
      (node (ref "C1") (pin "2") (pinfunction "2_2") (pintype "passive"))
      (node (ref "D1") (pin "2") (pinfunction "A_2") (pintype "passive"))
      (node (ref "D48") (pin "1") (pinfunction "1_1") (pintype "passive"))
      (node (ref "F1") (pin "2") (pinfunction "2_2") (pintype "passive"))
      (node (ref "R1") (pin "2") (pinfunction "2_2") (pintype "passive"))
      (node (ref "R50") (pin "2") (pinfunction "2_2") (pintype "passive"))
      (node (ref "R76") (pin "2") (pinfunction "2_2") (pintype "passive"))
    )
    (net (code "44") (name "CELL1") (class "Default")
      (node (ref "C1") (pin "1") (pinfunction "1_1") (pintype "passive"))
      (node (ref "C2") (pin "2") (pinfunction "2_2") (pintype "passive"))
      (node (ref "D1") (pin "1") (pinfunction "K_1") (pintype "passive"))
      (node (ref "D2") (pin "2") (pinfunction "A_2") (pintype "passive"))
      (node (ref "D47") (pin "1") (pinfunction "1_1") (pintype "passive"))
      (node (ref "F2") (pin "2") (pinfunction "2_2") (pintype "passive"))
      (node (ref "Q1") (pin "2") (pinfunction "S_2") (pintype "passive"))
      (node (ref "R3") (pin "2") (pinfunction "2_2") (pintype "passive"))
      (node (ref "R77") (pin "2") (pinfunction "2_2") (pintype "passive"))
    )
    (net (code "45") (name "CELL2") (class "Default")
      (node (ref "C2") (pin "1") (pinfunction "1_1") (pintype "passive"))
      (node (ref "C3") (pin "2") (pinfunction "2_2") (pintype "passive"))
      (node (ref "D2") (pin "1") (pinfunction "K_1") (pintype "passive"))
      (node (ref "D3") (pin "2") (pinfunction "A_2") (pintype "passive"))
      (node (ref "D46") (pin "1") (pinfunction "1_1") (pintype "passive"))
      (node (ref "F3") (pin "2") (pinfunction "2_2") (pintype "passive"))
      (node (ref "Q2") (pin "2") (pinfunction "S_2") (pintype "passive"))
      (node (ref "R5") (pin "2") (pinfunction "2_2") (pintype "passive"))
      (node (ref "R78") (pin "2") (pinfunction "2_2") (pintype "passive"))
    )
    (net (code "46") (name "CELL3") (class "Default")
      (node (ref "C3") (pin "1") (pinfunction "1_1") (pintype "passive"))
      (node (ref "C4") (pin "2") (pinfunction "2_2") (pintype "passive"))
      (node (ref "D3") (pin "1") (pinfunction "K_1") (pintype "passive"))
      (node (ref "D4") (pin "2") (pinfunction "A_2") (pintype "passive"))
      (node (ref "D45") (pin "1") (pinfunction "1_1") (pintype "passive"))
      (node (ref "F4") (pin "2") (pinfunction "2_2") (pintype "passive"))
      (node (ref "Q3") (pin "2") (pinfunction "S_2") (pintype "passive"))
      (node (ref "R7") (pin "2") (pinfunction "2_2") (pintype "passive"))
      (node (ref "R79") (pin "2") (pinfunction "2_2") (pintype "passive"))
    )
    (net (code "47") (name "CELL4") (class "Default")
      (node (ref "C4") (pin "1") (pinfunction "1_1") (pintype "passive"))
      (node (ref "C5") (pin "2") (pinfunction "2_2") (pintype "passive"))
      (node (ref "D4") (pin "1") (pinfunction "K_1") (pintype "passive"))
      (node (ref "D44") (pin "1") (pinfunction "1_1") (pintype "passive"))
      (node (ref "D5") (pin "2") (pinfunction "A_2") (pintype "passive"))
      (node (ref "F5") (pin "2") (pinfunction "2_2") (pintype "passive"))
      (node (ref "Q4") (pin "2") (pinfunction "S_2") (pintype "passive"))
      (node (ref "R80") (pin "2") (pinfunction "2_2") (pintype "passive"))
      (node (ref "R9") (pin "2") (pinfunction "2_2") (pintype "passive"))
    )
    (net (code "48") (name "CELL5") (class "Default")
      (node (ref "C5") (pin "1") (pinfunction "1_1") (pintype "passive"))
      (node (ref "C6") (pin "2") (pinfunction "2_2") (pintype "passive"))
      (node (ref "D43") (pin "1") (pinfunction "1_1") (pintype "passive"))
      (node (ref "D5") (pin "1") (pinfunction "K_1") (pintype "passive"))
      (node (ref "D6") (pin "2") (pinfunction "A_2") (pintype "passive"))
      (node (ref "F6") (pin "2") (pinfunction "2_2") (pintype "passive"))
      (node (ref "Q5") (pin "2") (pinfunction "S_2") (pintype "passive"))
      (node (ref "R11") (pin "2") (pinfunction "2_2") (pintype "passive"))
      (node (ref "R81") (pin "2") (pinfunction "2_2") (pintype "passive"))
    )
    (net (code "49") (name "CELL6") (class "Default")
      (node (ref "C6") (pin "1") (pinfunction "1_1") (pintype "passive"))
      (node (ref "C7") (pin "2") (pinfunction "2_2") (pintype "passive"))
      (node (ref "D42") (pin "1") (pinfunction "1_1") (pintype "passive"))
      (node (ref "D6") (pin "1") (pinfunction "K_1") (pintype "passive"))
      (node (ref "D7") (pin "2") (pinfunction "A_2") (pintype "passive"))
      (node (ref "F7") (pin "2") (pinfunction "2_2") (pintype "passive"))
      (node (ref "Q6") (pin "2") (pinfunction "S_2") (pintype "passive"))
      (node (ref "R13") (pin "2") (pinfunction "2_2") (pintype "passive"))
      (node (ref "R82") (pin "2") (pinfunction "2_2") (pintype "passive"))
    )
    (net (code "50") (name "CELL7") (class "Default")
      (node (ref "C7") (pin "1") (pinfunction "1_1") (pintype "passive"))
      (node (ref "C8") (pin "2") (pinfunction "2_2") (pintype "passive"))
      (node (ref "D41") (pin "1") (pinfunction "1_1") (pintype "passive"))
      (node (ref "D7") (pin "1") (pinfunction "K_1") (pintype "passive"))
      (node (ref "D8") (pin "2") (pinfunction "A_2") (pintype "passive"))
      (node (ref "F8") (pin "2") (pinfunction "2_2") (pintype "passive"))
      (node (ref "Q7") (pin "2") (pinfunction "S_2") (pintype "passive"))
      (node (ref "R15") (pin "2") (pinfunction "2_2") (pintype "passive"))
      (node (ref "R83") (pin "2") (pinfunction "2_2") (pintype "passive"))
    )
    (net (code "51") (name "CELL8") (class "Default")
      (node (ref "C8") (pin "1") (pinfunction "1_1") (pintype "passive"))
      (node (ref "C9") (pin "2") (pinfunction "2_2") (pintype "passive"))
      (node (ref "D40") (pin "1") (pinfunction "1_1") (pintype "passive"))
      (node (ref "D8") (pin "1") (pinfunction "K_1") (pintype "passive"))
      (node (ref "D9") (pin "2") (pinfunction "A_2") (pintype "passive"))
      (node (ref "F9") (pin "2") (pinfunction "2_2") (pintype "passive"))
      (node (ref "Q8") (pin "2") (pinfunction "S_2") (pintype "passive"))
      (node (ref "R17") (pin "2") (pinfunction "2_2") (pintype "passive"))
      (node (ref "R84") (pin "2") (pinfunction "2_2") (pintype "passive"))
    )
    (net (code "52") (name "CELL9") (class "Default")
      (node (ref "C10") (pin "2") (pinfunction "2_2") (pintype "passive"))
      (node (ref "C9") (pin "1") (pinfunction "1_1") (pintype "passive"))
      (node (ref "D10") (pin "2") (pinfunction "A_2") (pintype "passive"))
      (node (ref "D39") (pin "1") (pinfunction "1_1") (pintype "passive"))
      (node (ref "D9") (pin "1") (pinfunction "K_1") (pintype "passive"))
      (node (ref "F10") (pin "2") (pinfunction "2_2") (pintype "passive"))
      (node (ref "Q9") (pin "2") (pinfunction "S_2") (pintype "passive"))
      (node (ref "R19") (pin "2") (pinfunction "2_2") (pintype "passive"))
      (node (ref "R85") (pin "2") (pinfunction "2_2") (pintype "passive"))
    )
    (net (code "53") (name "CELL10") (class "Default")
      (node (ref "C10") (pin "1") (pinfunction "1_1") (pintype "passive"))
      (node (ref "C11") (pin "2") (pinfunction "2_2") (pintype "passive"))
      (node (ref "D10") (pin "1") (pinfunction "K_1") (pintype "passive"))
      (node (ref "D11") (pin "2") (pinfunction "A_2") (pintype "passive"))
      (node (ref "D38") (pin "1") (pinfunction "1_1") (pintype "passive"))
      (node (ref "F11") (pin "2") (pinfunction "2_2") (pintype "passive"))
      (node (ref "Q10") (pin "2") (pinfunction "S_2") (pintype "passive"))
      (node (ref "R21") (pin "2") (pinfunction "2_2") (pintype "passive"))
      (node (ref "R86") (pin "2") (pinfunction "2_2") (pintype "passive"))
    )
    (net (code "54") (name "CELL11") (class "Default")
      (node (ref "C11") (pin "1") (pinfunction "1_1") (pintype "passive"))
      (node (ref "C12") (pin "2") (pinfunction "2_2") (pintype "passive"))
      (node (ref "D11") (pin "1") (pinfunction "K_1") (pintype "passive"))
      (node (ref "D12") (pin "2") (pinfunction "A_2") (pintype "passive"))
      (node (ref "D37") (pin "1") (pinfunction "1_1") (pintype "passive"))
      (node (ref "F12") (pin "2") (pinfunction "2_2") (pintype "passive"))
      (node (ref "Q11") (pin "2") (pinfunction "S_2") (pintype "passive"))
      (node (ref "R23") (pin "2") (pinfunction "2_2") (pintype "passive"))
      (node (ref "R87") (pin "2") (pinfunction "2_2") (pintype "passive"))
    )
    (net (code "55") (name "CELL12") (class "Default")
      (node (ref "C12") (pin "1") (pinfunction "1_1") (pintype "passive"))
      (node (ref "C13") (pin "2") (pinfunction "2_2") (pintype "passive"))
      (node (ref "D12") (pin "1") (pinfunction "K_1") (pintype "passive"))
      (node (ref "D13") (pin "2") (pinfunction "A_2") (pintype "passive"))
      (node (ref "D36") (pin "1") (pinfunction "1_1") (pintype "passive"))
      (node (ref "F13") (pin "2") (pinfunction "2_2") (pintype "passive"))
      (node (ref "Q12") (pin "2") (pinfunction "S_2") (pintype "passive"))
      (node (ref "R101") (pin "2") (pinfunction "2_2") (pintype "passive"))
      (node (ref "R122") (pin "2") (pinfunction "2_2") (pintype "passive"))
      (node (ref "R25") (pin "2") (pinfunction "2_2") (pintype "passive"))
      (node (ref "R63") (pin "2") (pinfunction "2_2") (pintype "passive"))
      (node (ref "R88") (pin "2") (pinfunction "2_2") (pintype "passive"))
    )
    (net (code "56") (name "CELL13") (class "Default")
      (node (ref "C13") (pin "1") (pinfunction "1_1") (pintype "passive"))
      (node (ref "C14") (pin "2") (pinfunction "2_2") (pintype "passive"))
      (node (ref "D13") (pin "1") (pinfunction "K_1") (pintype "passive"))
      (node (ref "D14") (pin "2") (pinfunction "A_2") (pintype "passive"))
      (node (ref "D35") (pin "1") (pinfunction "1_1") (pintype "passive"))
      (node (ref "F14") (pin "2") (pinfunction "2_2") (pintype "passive"))
      (node (ref "Q13") (pin "2") (pinfunction "S_2") (pintype "passive"))
      (node (ref "R27") (pin "2") (pinfunction "2_2") (pintype "passive"))
      (node (ref "R89") (pin "2") (pinfunction "2_2") (pintype "passive"))
    )
    (net (code "57") (name "CELL14") (class "Default")
      (node (ref "C14") (pin "1") (pinfunction "1_1") (pintype "passive"))
      (node (ref "C15") (pin "2") (pinfunction "2_2") (pintype "passive"))
      (node (ref "D14") (pin "1") (pinfunction "K_1") (pintype "passive"))
      (node (ref "D15") (pin "2") (pinfunction "A_2") (pintype "passive"))
      (node (ref "D34") (pin "1") (pinfunction "1_1") (pintype "passive"))
      (node (ref "F15") (pin "2") (pinfunction "2_2") (pintype "passive"))
      (node (ref "Q14") (pin "2") (pinfunction "S_2") (pintype "passive"))
      (node (ref "R29") (pin "2") (pinfunction "2_2") (pintype "passive"))
      (node (ref "R90") (pin "2") (pinfunction "2_2") (pintype "passive"))
    )
    (net (code "58") (name "CELL15") (class "Default")
      (node (ref "C15") (pin "1") (pinfunction "1_1") (pintype "passive"))
      (node (ref "C16") (pin "2") (pinfunction "2_2") (pintype "passive"))
      (node (ref "D15") (pin "1") (pinfunction "K_1") (pintype "passive"))
      (node (ref "D16") (pin "2") (pinfunction "A_2") (pintype "passive"))
      (node (ref "D33") (pin "1") (pinfunction "1_1") (pintype "passive"))
      (node (ref "F16") (pin "2") (pinfunction "2_2") (pintype "passive"))
      (node (ref "Q15") (pin "2") (pinfunction "S_2") (pintype "passive"))
      (node (ref "R31") (pin "2") (pinfunction "2_2") (pintype "passive"))
      (node (ref "R91") (pin "2") (pinfunction "2_2") (pintype "passive"))
    )
    (net (code "59") (name "CELL16") (class "Default")
      (node (ref "C16") (pin "1") (pinfunction "1_1") (pintype "passive"))
      (node (ref "C17") (pin "2") (pinfunction "2_2") (pintype "passive"))
      (node (ref "D16") (pin "1") (pinfunction "K_1") (pintype "passive"))
      (node (ref "D17") (pin "2") (pinfunction "A_2") (pintype "passive"))
      (node (ref "D32") (pin "1") (pinfunction "1_1") (pintype "passive"))
      (node (ref "F17") (pin "2") (pinfunction "2_2") (pintype "passive"))
      (node (ref "Q16") (pin "2") (pinfunction "S_2") (pintype "passive"))
      (node (ref "R33") (pin "2") (pinfunction "2_2") (pintype "passive"))
      (node (ref "R92") (pin "2") (pinfunction "2_2") (pintype "passive"))
    )
    (net (code "60") (name "CELL17") (class "Default")
      (node (ref "C17") (pin "1") (pinfunction "1_1") (pintype "passive"))
      (node (ref "C18") (pin "2") (pinfunction "2_2") (pintype "passive"))
      (node (ref "D17") (pin "1") (pinfunction "K_1") (pintype "passive"))
      (node (ref "D18") (pin "2") (pinfunction "A_2") (pintype "passive"))
      (node (ref "D31") (pin "1") (pinfunction "1_1") (pintype "passive"))
      (node (ref "F18") (pin "2") (pinfunction "2_2") (pintype "passive"))
      (node (ref "Q17") (pin "2") (pinfunction "S_2") (pintype "passive"))
      (node (ref "R35") (pin "2") (pinfunction "2_2") (pintype "passive"))
      (node (ref "R93") (pin "2") (pinfunction "2_2") (pintype "passive"))
    )
    (net (code "61") (name "CELL18") (class "Default")
      (node (ref "C18") (pin "1") (pinfunction "1_1") (pintype "passive"))
      (node (ref "C19") (pin "2") (pinfunction "2_2") (pintype "passive"))
      (node (ref "D18") (pin "1") (pinfunction "K_1") (pintype "passive"))
      (node (ref "D19") (pin "2") (pinfunction "A_2") (pintype "passive"))
      (node (ref "D30") (pin "1") (pinfunction "1_1") (pintype "passive"))
      (node (ref "F19") (pin "2") (pinfunction "2_2") (pintype "passive"))
      (node (ref "Q18") (pin "2") (pinfunction "S_2") (pintype "passive"))
      (node (ref "R37") (pin "2") (pinfunction "2_2") (pintype "passive"))
      (node (ref "R94") (pin "2") (pinfunction "2_2") (pintype "passive"))
    )
    (net (code "62") (name "CELL19") (class "Default")
      (node (ref "C19") (pin "1") (pinfunction "1_1") (pintype "passive"))
      (node (ref "C20") (pin "2") (pinfunction "2_2") (pintype "passive"))
      (node (ref "D19") (pin "1") (pinfunction "K_1") (pintype "passive"))
      (node (ref "D20") (pin "2") (pinfunction "A_2") (pintype "passive"))
      (node (ref "D29") (pin "1") (pinfunction "1_1") (pintype "passive"))
      (node (ref "F20") (pin "2") (pinfunction "2_2") (pintype "passive"))
      (node (ref "Q19") (pin "2") (pinfunction "S_2") (pintype "passive"))
      (node (ref "R39") (pin "2") (pinfunction "2_2") (pintype "passive"))
      (node (ref "R95") (pin "2") (pinfunction "2_2") (pintype "passive"))
    )
    (net (code "63") (name "CELL20") (class "Default")
      (node (ref "C20") (pin "1") (pinfunction "1_1") (pintype "passive"))
      (node (ref "C21") (pin "2") (pinfunction "2_2") (pintype "passive"))
      (node (ref "D20") (pin "1") (pinfunction "K_1") (pintype "passive"))
      (node (ref "D21") (pin "2") (pinfunction "A_2") (pintype "passive"))
      (node (ref "D28") (pin "1") (pinfunction "1_1") (pintype "passive"))
      (node (ref "F21") (pin "2") (pinfunction "2_2") (pintype "passive"))
      (node (ref "Q20") (pin "2") (pinfunction "S_2") (pintype "passive"))
      (node (ref "R41") (pin "2") (pinfunction "2_2") (pintype "passive"))
      (node (ref "R96") (pin "2") (pinfunction "2_2") (pintype "passive"))
    )
    (net (code "64") (name "CELL21") (class "Default")
      (node (ref "C21") (pin "1") (pinfunction "1_1") (pintype "passive"))
      (node (ref "C22") (pin "2") (pinfunction "2_2") (pintype "passive"))
      (node (ref "D21") (pin "1") (pinfunction "K_1") (pintype "passive"))
      (node (ref "D22") (pin "2") (pinfunction "A_2") (pintype "passive"))
      (node (ref "D27") (pin "1") (pinfunction "1_1") (pintype "passive"))
      (node (ref "F22") (pin "2") (pinfunction "2_2") (pintype "passive"))
      (node (ref "Q21") (pin "2") (pinfunction "S_2") (pintype "passive"))
      (node (ref "R43") (pin "2") (pinfunction "2_2") (pintype "passive"))
      (node (ref "R97") (pin "2") (pinfunction "2_2") (pintype "passive"))
    )
    (net (code "65") (name "CELL22") (class "Default")
      (node (ref "C22") (pin "1") (pinfunction "1_1") (pintype "passive"))
      (node (ref "C23") (pin "2") (pinfunction "2_2") (pintype "passive"))
      (node (ref "D22") (pin "1") (pinfunction "K_1") (pintype "passive"))
      (node (ref "D23") (pin "2") (pinfunction "A_2") (pintype "passive"))
      (node (ref "D26") (pin "1") (pinfunction "1_1") (pintype "passive"))
      (node (ref "F23") (pin "2") (pinfunction "2_2") (pintype "passive"))
      (node (ref "Q22") (pin "2") (pinfunction "S_2") (pintype "passive"))
      (node (ref "R45") (pin "2") (pinfunction "2_2") (pintype "passive"))
      (node (ref "R98") (pin "2") (pinfunction "2_2") (pintype "passive"))
    )
    (net (code "66") (name "CELL23") (class "Default")
      (node (ref "C23") (pin "1") (pinfunction "1_1") (pintype "passive"))
      (node (ref "C24") (pin "2") (pinfunction "2_2") (pintype "passive"))
      (node (ref "D23") (pin "1") (pinfunction "K_1") (pintype "passive"))
      (node (ref "D24") (pin "2") (pinfunction "A_2") (pintype "passive"))
      (node (ref "D25") (pin "1") (pinfunction "1_1") (pintype "passive"))
      (node (ref "F24") (pin "2") (pinfunction "2_2") (pintype "passive"))
      (node (ref "Q23") (pin "2") (pinfunction "S_2") (pintype "passive"))
      (node (ref "R47") (pin "2") (pinfunction "2_2") (pintype "passive"))
      (node (ref "R99") (pin "2") (pinfunction "2_2") (pintype "passive"))
    )
    (net (code "67") (name "CELL24") (class "Default")
      (node (ref "C24") (pin "1") (pinfunction "1_1") (pintype "passive"))
      (node (ref "D24") (pin "1") (pinfunction "K_1") (pintype "passive"))
      (node (ref "F25") (pin "2") (pinfunction "2_2") (pintype "passive"))
      (node (ref "Q24") (pin "2") (pinfunction "S_2") (pintype "passive"))
      (node (ref "R100") (pin "2") (pinfunction "2_2") (pintype "passive"))
      (node (ref "R121") (pin "2") (pinfunction "2_2") (pintype "passive"))
      (node (ref "R49") (pin "2") (pinfunction "2_2") (pintype "passive"))
    )
    (net (code "68") (name "CELL_UF_0") (class "Default")
      (node (ref "F1") (pin "1") (pinfunction "1_1") (pintype "passive"))
      (node (ref "P1") (pin "3") (pinfunction "3_3") (pintype "passive"))
    )
    (net (code "69") (name "CELL_UF_1") (class "Default")
      (node (ref "F2") (pin "1") (pinfunction "1_1") (pintype "passive"))
      (node (ref "P1") (pin "4") (pinfunction "4_4") (pintype "passive"))
    )
    (net (code "70") (name "CELL_UF_2") (class "Default")
      (node (ref "F3") (pin "1") (pinfunction "1_1") (pintype "passive"))
      (node (ref "P1") (pin "12") (pinfunction "12_12") (pintype "passive"))
    )
    (net (code "71") (name "CELL_UF_3") (class "Default")
      (node (ref "F4") (pin "1") (pinfunction "1_1") (pintype "passive"))
      (node (ref "P1") (pin "11") (pinfunction "11_11") (pintype "passive"))
    )
    (net (code "72") (name "CELL_UF_4") (class "Default")
      (node (ref "F5") (pin "1") (pinfunction "1_1") (pintype "passive"))
      (node (ref "P1") (pin "10") (pinfunction "10_10") (pintype "passive"))
    )
    (net (code "73") (name "CELL_UF_5") (class "Default")
      (node (ref "F6") (pin "1") (pinfunction "1_1") (pintype "passive"))
      (node (ref "P1") (pin "9") (pinfunction "9_9") (pintype "passive"))
    )
    (net (code "74") (name "CELL_UF_6") (class "Default")
      (node (ref "F7") (pin "1") (pinfunction "1_1") (pintype "passive"))
      (node (ref "P1") (pin "8") (pinfunction "8_8") (pintype "passive"))
    )
    (net (code "75") (name "CELL_UF_7") (class "Default")
      (node (ref "F8") (pin "1") (pinfunction "1_1") (pintype "passive"))
      (node (ref "P1") (pin "7") (pinfunction "7_7") (pintype "passive"))
    )
    (net (code "76") (name "CELL_UF_8") (class "Default")
      (node (ref "F9") (pin "1") (pinfunction "1_1") (pintype "passive"))
      (node (ref "P1") (pin "6") (pinfunction "6_6") (pintype "passive"))
    )
    (net (code "77") (name "CELL_UF_9") (class "Default")
      (node (ref "F10") (pin "1") (pinfunction "1_1") (pintype "passive"))
      (node (ref "P1") (pin "5") (pinfunction "5_5") (pintype "passive"))
    )
    (net (code "78") (name "CELL_UF_10") (class "Default")
      (node (ref "F11") (pin "1") (pinfunction "1_1") (pintype "passive"))
      (node (ref "P1") (pin "1") (pinfunction "1_1") (pintype "passive"))
    )
    (net (code "79") (name "CELL_UF_11") (class "Default")
      (node (ref "F12") (pin "1") (pinfunction "1_1") (pintype "passive"))
      (node (ref "P1") (pin "2") (pinfunction "2_2") (pintype "passive"))
    )
    (net (code "80") (name "CELL_UF_12") (class "Default")
      (node (ref "F13") (pin "1") (pinfunction "1_1") (pintype "passive"))
      (node (ref "P2") (pin "4") (pinfunction "4_4") (pintype "passive"))
    )
    (net (code "81") (name "CELL_UF_13") (class "Default")
      (node (ref "F14") (pin "1") (pinfunction "1_1") (pintype "passive"))
      (node (ref "P2") (pin "5") (pinfunction "5_5") (pintype "passive"))
    )
    (net (code "82") (name "CELL_UF_14") (class "Default")
      (node (ref "F15") (pin "1") (pinfunction "1_1") (pintype "passive"))
      (node (ref "P2") (pin "6") (pinfunction "6_6") (pintype "passive"))
    )
    (net (code "83") (name "CELL_UF_15") (class "Default")
      (node (ref "F16") (pin "1") (pinfunction "1_1") (pintype "passive"))
      (node (ref "P2") (pin "16") (pinfunction "16_16") (pintype "passive"))
    )
    (net (code "84") (name "CELL_UF_16") (class "Default")
      (node (ref "F17") (pin "1") (pinfunction "1_1") (pintype "passive"))
      (node (ref "P2") (pin "15") (pinfunction "15_15") (pintype "passive"))
    )
    (net (code "85") (name "CELL_UF_17") (class "Default")
      (node (ref "F18") (pin "1") (pinfunction "1_1") (pintype "passive"))
      (node (ref "P2") (pin "14") (pinfunction "14_14") (pintype "passive"))
    )
    (net (code "86") (name "CELL_UF_18") (class "Default")
      (node (ref "F19") (pin "1") (pinfunction "1_1") (pintype "passive"))
      (node (ref "P2") (pin "13") (pinfunction "13_13") (pintype "passive"))
    )
    (net (code "87") (name "CELL_UF_19") (class "Default")
      (node (ref "F20") (pin "1") (pinfunction "1_1") (pintype "passive"))
      (node (ref "P2") (pin "12") (pinfunction "12_12") (pintype "passive"))
    )
    (net (code "88") (name "CELL_UF_20") (class "Default")
      (node (ref "F21") (pin "1") (pinfunction "1_1") (pintype "passive"))
      (node (ref "P2") (pin "11") (pinfunction "11_11") (pintype "passive"))
    )
    (net (code "89") (name "CELL_UF_21") (class "Default")
      (node (ref "F22") (pin "1") (pinfunction "1_1") (pintype "passive"))
      (node (ref "P2") (pin "10") (pinfunction "10_10") (pintype "passive"))
    )
    (net (code "90") (name "CELL_UF_22") (class "Default")
      (node (ref "F23") (pin "1") (pinfunction "1_1") (pintype "passive"))
      (node (ref "P2") (pin "9") (pinfunction "9_9") (pintype "passive"))
    )
    (net (code "91") (name "CELL_UF_23") (class "Default")
      (node (ref "F24") (pin "1") (pinfunction "1_1") (pintype "passive"))
      (node (ref "P2") (pin "8") (pinfunction "8_8") (pintype "passive"))
    )
    (net (code "92") (name "CELL_UF_24") (class "Default")
      (node (ref "F25") (pin "1") (pinfunction "1_1") (pintype "passive"))
      (node (ref "P2") (pin "7") (pinfunction "7_7") (pintype "passive"))
    )
    (net (code "93") (name "GNDA") (class "Default")
      (node (ref "C25") (pin "2") (pinfunction "2_2") (pintype "passive"))
      (node (ref "C26") (pin "2") (pinfunction "2_2") (pintype "passive"))
      (node (ref "C27") (pin "2") (pinfunction "2_2") (pintype "passive"))
      (node (ref "C28") (pin "2") (pinfunction "2_2") (pintype "passive"))
      (node (ref "C29") (pin "2") (pinfunction "2_2") (pintype "passive"))
      (node (ref "C30") (pin "2") (pinfunction "2_2") (pintype "passive"))
      (node (ref "C31") (pin "2") (pinfunction "2_2") (pintype "passive"))
      (node (ref "C32") (pin "2") (pinfunction "2_2") (pintype "passive"))
      (node (ref "C33") (pin "2") (pinfunction "2_2") (pintype "passive"))
      (node (ref "C34") (pin "2") (pinfunction "2_2") (pintype "passive"))
      (node (ref "C35") (pin "2") (pinfunction "2_2") (pintype "passive"))
      (node (ref "C36") (pin "2") (pinfunction "2_2") (pintype "passive"))
      (node (ref "C51") (pin "2") (pinfunction "2_2") (pintype "passive"))
      (node (ref "C53") (pin "2") (pinfunction "2_2") (pintype "passive"))
      (node (ref "C55") (pin "2") (pinfunction "2_2") (pintype "passive"))
      (node (ref "C57") (pin "2") (pinfunction "2_2") (pintype "passive"))
      (node (ref "C59") (pin "2") (pinfunction "2_2") (pintype "passive"))
      (node (ref "C61") (pin "2") (pinfunction "2_2") (pintype "passive"))
      (node (ref "C63") (pin "2") (pinfunction "2_2") (pintype "passive"))
      (node (ref "C65") (pin "2") (pinfunction "2_2") (pintype "passive"))
      (node (ref "C66") (pin "2") (pinfunction "2_2") (pintype "passive"))
      (node (ref "C68") (pin "2") (pinfunction "2_2") (pintype "passive"))
      (node (ref "C70") (pin "2") (pinfunction "2_2") (pintype "passive"))
      (node (ref "C74") (pin "2") (pinfunction "2_2") (pintype "passive"))
      (node (ref "C76") (pin "2") (pinfunction "2_2") (pintype "passive"))
      (node (ref "C77") (pin "2") (pinfunction "2_2") (pintype "passive"))
      (node (ref "J1") (pin "1") (pinfunction "1_1") (pintype "passive"))
      (node (ref "J1") (pin "3") (pinfunction "3_3") (pintype "passive"))
      (node (ref "J1") (pin "5") (pinfunction "5_5") (pintype "passive"))
      (node (ref "J1") (pin "7") (pinfunction "7_7") (pintype "passive"))
      (node (ref "J1") (pin "9") (pinfunction "9_9") (pintype "passive"))
      (node (ref "JP2") (pin "3") (pinfunction "3_3") (pintype "passive"))
      (node (ref "R118") (pin "2") (pinfunction "2_2") (pintype "passive"))
      (node (ref "R50") (pin "1") (pinfunction "1_1") (pintype "passive"))
      (node (ref "U1") (pin "30") (pinfunction "V-_1_30") (pintype "passive"))
      (node (ref "U1") (pin "31") (pinfunction "V-_2_31") (pintype "passive"))
    )
    (net (code "94") (name "GNDB") (class "Default")
      (node (ref "C37") (pin "2") (pinfunction "2_2") (pintype "passive"))
      (node (ref "C38") (pin "2") (pinfunction "2_2") (pintype "passive"))
      (node (ref "C39") (pin "2") (pinfunction "2_2") (pintype "passive"))
      (node (ref "C40") (pin "2") (pinfunction "2_2") (pintype "passive"))
      (node (ref "C41") (pin "2") (pinfunction "2_2") (pintype "passive"))
      (node (ref "C42") (pin "2") (pinfunction "2_2") (pintype "passive"))
      (node (ref "C43") (pin "2") (pinfunction "2_2") (pintype "passive"))
      (node (ref "C44") (pin "2") (pinfunction "2_2") (pintype "passive"))
      (node (ref "C45") (pin "2") (pinfunction "2_2") (pintype "passive"))
      (node (ref "C46") (pin "2") (pinfunction "2_2") (pintype "passive"))
      (node (ref "C47") (pin "2") (pinfunction "2_2") (pintype "passive"))
      (node (ref "C48") (pin "2") (pinfunction "2_2") (pintype "passive"))
      (node (ref "C49") (pin "2") (pinfunction "2_2") (pintype "passive"))
      (node (ref "C50") (pin "2") (pinfunction "2_2") (pintype "passive"))
      (node (ref "C52") (pin "2") (pinfunction "2_2") (pintype "passive"))
      (node (ref "C54") (pin "2") (pinfunction "2_2") (pintype "passive"))
      (node (ref "C56") (pin "2") (pinfunction "2_2") (pintype "passive"))
      (node (ref "C58") (pin "2") (pinfunction "2_2") (pintype "passive"))
      (node (ref "C60") (pin "2") (pinfunction "2_2") (pintype "passive"))
      (node (ref "C62") (pin "2") (pinfunction "2_2") (pintype "passive"))
      (node (ref "C64") (pin "2") (pinfunction "2_2") (pintype "passive"))
      (node (ref "C67") (pin "2") (pinfunction "2_2") (pintype "passive"))
      (node (ref "C69") (pin "2") (pinfunction "2_2") (pintype "passive"))
      (node (ref "C71") (pin "2") (pinfunction "2_2") (pintype "passive"))
      (node (ref "C75") (pin "2") (pinfunction "2_2") (pintype "passive"))
      (node (ref "J2") (pin "1") (pinfunction "1_1") (pintype "passive"))
      (node (ref "J2") (pin "3") (pinfunction "3_3") (pintype "passive"))
      (node (ref "J2") (pin "5") (pinfunction "5_5") (pintype "passive"))
      (node (ref "J2") (pin "7") (pinfunction "7_7") (pintype "passive"))
      (node (ref "J2") (pin "9") (pinfunction "9_9") (pintype "passive"))
      (node (ref "JP1") (pin "3") (pinfunction "3_3") (pintype "passive"))
      (node (ref "R117") (pin "2") (pinfunction "2_2") (pintype "passive"))
      (node (ref "R63") (pin "1") (pinfunction "1_1") (pintype "passive"))
      (node (ref "U2") (pin "30") (pinfunction "V-_1_30") (pintype "passive"))
      (node (ref "U2") (pin "31") (pinfunction "V-_2_31") (pintype "passive"))
    )
    (net (code "95") (name "Net-(C49-Pad1)") (class "Default")
      (node (ref "C49") (pin "1") (pinfunction "1_1") (pintype "passive"))
      (node (ref "R112") (pin "1") (pinfunction "1_1") (pintype "passive"))
      (node (ref "R114") (pin "2") (pinfunction "2_2") (pintype "passive"))
    )
    (net (code "96") (name "Net-(C65-Pad1)") (class "Default")
      (node (ref "C65") (pin "1") (pinfunction "1_1") (pintype "passive"))
      (node (ref "R119") (pin "2") (pinfunction "2_2") (pintype "passive"))
      (node (ref "R120") (pin "2") (pinfunction "2_2") (pintype "passive"))
    )
    (net (code "97") (name "Net-(C71-Pad1)") (class "Default")
      (node (ref "C71") (pin "1") (pinfunction "1_1") (pintype "passive"))
      (node (ref "R123") (pin "1") (pinfunction "1_1") (pintype "passive"))
      (node (ref "R124") (pin "2") (pinfunction "2_2") (pintype "passive"))
    )
    (net (code "98") (name "Net-(C74-Pad1)") (class "Default")
      (node (ref "C74") (pin "1") (pinfunction "1_1") (pintype "passive"))
      (node (ref "R115") (pin "2") (pinfunction "2_2") (pintype "passive"))
      (node (ref "R125") (pin "1") (pinfunction "1_1") (pintype "passive"))
    )
    (net (code "99") (name "Net-(D25-Pad2)") (class "Default")
      (node (ref "D25") (pin "2") (pinfunction "2_2") (pintype "passive"))
      (node (ref "R75") (pin "1") (pinfunction "1_1") (pintype "passive"))
    )
    (net (code "100") (name "Net-(D26-Pad2)") (class "Default")
      (node (ref "D26") (pin "2") (pinfunction "2_2") (pintype "passive"))
      (node (ref "R74") (pin "1") (pinfunction "1_1") (pintype "passive"))
    )
    (net (code "101") (name "Net-(D27-Pad2)") (class "Default")
      (node (ref "D27") (pin "2") (pinfunction "2_2") (pintype "passive"))
      (node (ref "R73") (pin "1") (pinfunction "1_1") (pintype "passive"))
    )
    (net (code "102") (name "Net-(D28-Pad2)") (class "Default")
      (node (ref "D28") (pin "2") (pinfunction "2_2") (pintype "passive"))
      (node (ref "R72") (pin "1") (pinfunction "1_1") (pintype "passive"))
    )
    (net (code "103") (name "Net-(D29-Pad2)") (class "Default")
      (node (ref "D29") (pin "2") (pinfunction "2_2") (pintype "passive"))
      (node (ref "R71") (pin "1") (pinfunction "1_1") (pintype "passive"))
    )
    (net (code "104") (name "Net-(D30-Pad2)") (class "Default")
      (node (ref "D30") (pin "2") (pinfunction "2_2") (pintype "passive"))
      (node (ref "R70") (pin "1") (pinfunction "1_1") (pintype "passive"))
    )
    (net (code "105") (name "Net-(D31-Pad2)") (class "Default")
      (node (ref "D31") (pin "2") (pinfunction "2_2") (pintype "passive"))
      (node (ref "R69") (pin "1") (pinfunction "1_1") (pintype "passive"))
    )
    (net (code "106") (name "Net-(D32-Pad2)") (class "Default")
      (node (ref "D32") (pin "2") (pinfunction "2_2") (pintype "passive"))
      (node (ref "R68") (pin "1") (pinfunction "1_1") (pintype "passive"))
    )
    (net (code "107") (name "Net-(D33-Pad2)") (class "Default")
      (node (ref "D33") (pin "2") (pinfunction "2_2") (pintype "passive"))
      (node (ref "R67") (pin "1") (pinfunction "1_1") (pintype "passive"))
    )
    (net (code "108") (name "Net-(D34-Pad2)") (class "Default")
      (node (ref "D34") (pin "2") (pinfunction "2_2") (pintype "passive"))
      (node (ref "R66") (pin "1") (pinfunction "1_1") (pintype "passive"))
    )
    (net (code "109") (name "Net-(D35-Pad2)") (class "Default")
      (node (ref "D35") (pin "2") (pinfunction "2_2") (pintype "passive"))
      (node (ref "R65") (pin "1") (pinfunction "1_1") (pintype "passive"))
    )
    (net (code "110") (name "Net-(D36-Pad2)") (class "Default")
      (node (ref "D36") (pin "2") (pinfunction "2_2") (pintype "passive"))
      (node (ref "R64") (pin "1") (pinfunction "1_1") (pintype "passive"))
    )
    (net (code "111") (name "Net-(D37-Pad2)") (class "Default")
      (node (ref "D37") (pin "2") (pinfunction "2_2") (pintype "passive"))
      (node (ref "R62") (pin "1") (pinfunction "1_1") (pintype "passive"))
    )
    (net (code "112") (name "Net-(D38-Pad2)") (class "Default")
      (node (ref "D38") (pin "2") (pinfunction "2_2") (pintype "passive"))
      (node (ref "R61") (pin "1") (pinfunction "1_1") (pintype "passive"))
    )
    (net (code "113") (name "Net-(D39-Pad2)") (class "Default")
      (node (ref "D39") (pin "2") (pinfunction "2_2") (pintype "passive"))
      (node (ref "R60") (pin "1") (pinfunction "1_1") (pintype "passive"))
    )
    (net (code "114") (name "Net-(D40-Pad2)") (class "Default")
      (node (ref "D40") (pin "2") (pinfunction "2_2") (pintype "passive"))
      (node (ref "R59") (pin "1") (pinfunction "1_1") (pintype "passive"))
    )
    (net (code "115") (name "Net-(D41-Pad2)") (class "Default")
      (node (ref "D41") (pin "2") (pinfunction "2_2") (pintype "passive"))
      (node (ref "R58") (pin "1") (pinfunction "1_1") (pintype "passive"))
    )
    (net (code "116") (name "Net-(D42-Pad2)") (class "Default")
      (node (ref "D42") (pin "2") (pinfunction "2_2") (pintype "passive"))
      (node (ref "R57") (pin "1") (pinfunction "1_1") (pintype "passive"))
    )
    (net (code "117") (name "Net-(D43-Pad2)") (class "Default")
      (node (ref "D43") (pin "2") (pinfunction "2_2") (pintype "passive"))
      (node (ref "R56") (pin "1") (pinfunction "1_1") (pintype "passive"))
    )
    (net (code "118") (name "Net-(D44-Pad2)") (class "Default")
      (node (ref "D44") (pin "2") (pinfunction "2_2") (pintype "passive"))
      (node (ref "R55") (pin "1") (pinfunction "1_1") (pintype "passive"))
    )
    (net (code "119") (name "Net-(D45-Pad2)") (class "Default")
      (node (ref "D45") (pin "2") (pinfunction "2_2") (pintype "passive"))
      (node (ref "R54") (pin "1") (pinfunction "1_1") (pintype "passive"))
    )
    (net (code "120") (name "Net-(D46-Pad2)") (class "Default")
      (node (ref "D46") (pin "2") (pinfunction "2_2") (pintype "passive"))
      (node (ref "R53") (pin "1") (pinfunction "1_1") (pintype "passive"))
    )
    (net (code "121") (name "Net-(D47-Pad2)") (class "Default")
      (node (ref "D47") (pin "2") (pinfunction "2_2") (pintype "passive"))
      (node (ref "R52") (pin "1") (pinfunction "1_1") (pintype "passive"))
    )
    (net (code "122") (name "Net-(D48-Pad2)") (class "Default")
      (node (ref "D48") (pin "2") (pinfunction "2_2") (pintype "passive"))
      (node (ref "R51") (pin "1") (pinfunction "1_1") (pintype "passive"))
    )
    (net (code "123") (name "Net-(D49-Pad2)") (class "Default")
      (node (ref "D49") (pin "2") (pinfunction "2_2") (pintype "passive"))
      (node (ref "JP3") (pin "1") (pinfunction "1_1") (pintype "passive"))
      (node (ref "R121") (pin "1") (pinfunction "1_1") (pintype "passive"))
    )
    (net (code "124") (name "Net-(D50-Pad2)") (class "Default")
      (node (ref "D50") (pin "2") (pinfunction "2_2") (pintype "passive"))
      (node (ref "JP4") (pin "1") (pinfunction "1_1") (pintype "passive"))
      (node (ref "R122") (pin "1") (pinfunction "1_1") (pintype "passive"))
    )
    (net (code "125") (name "Net-(Q1-D)") (class "Default")
      (node (ref "Q1") (pin "3") (pinfunction "D_3") (pintype "passive"))
      (node (ref "R51") (pin "2") (pinfunction "2_2") (pintype "passive"))
      (node (ref "R76") (pin "1") (pinfunction "1_1") (pintype "passive"))
    )
    (net (code "126") (name "Net-(Q1-G)") (class "Default")
      (node (ref "Q1") (pin "1") (pinfunction "G_1") (pintype "passive"))
      (node (ref "R2") (pin "2") (pinfunction "2_2") (pintype "passive"))
    )
    (net (code "127") (name "Net-(Q2-D)") (class "Default")
      (node (ref "Q2") (pin "3") (pinfunction "D_3") (pintype "passive"))
      (node (ref "R52") (pin "2") (pinfunction "2_2") (pintype "passive"))
      (node (ref "R77") (pin "1") (pinfunction "1_1") (pintype "passive"))
    )
    (net (code "128") (name "Net-(Q2-G)") (class "Default")
      (node (ref "Q2") (pin "1") (pinfunction "G_1") (pintype "passive"))
      (node (ref "R4") (pin "2") (pinfunction "2_2") (pintype "passive"))
    )
    (net (code "129") (name "Net-(Q3-D)") (class "Default")
      (node (ref "Q3") (pin "3") (pinfunction "D_3") (pintype "passive"))
      (node (ref "R53") (pin "2") (pinfunction "2_2") (pintype "passive"))
      (node (ref "R78") (pin "1") (pinfunction "1_1") (pintype "passive"))
    )
    (net (code "130") (name "Net-(Q3-G)") (class "Default")
      (node (ref "Q3") (pin "1") (pinfunction "G_1") (pintype "passive"))
      (node (ref "R6") (pin "2") (pinfunction "2_2") (pintype "passive"))
    )
    (net (code "131") (name "Net-(Q4-D)") (class "Default")
      (node (ref "Q4") (pin "3") (pinfunction "D_3") (pintype "passive"))
      (node (ref "R54") (pin "2") (pinfunction "2_2") (pintype "passive"))
      (node (ref "R79") (pin "1") (pinfunction "1_1") (pintype "passive"))
    )
    (net (code "132") (name "Net-(Q4-G)") (class "Default")
      (node (ref "Q4") (pin "1") (pinfunction "G_1") (pintype "passive"))
      (node (ref "R8") (pin "2") (pinfunction "2_2") (pintype "passive"))
    )
    (net (code "133") (name "Net-(Q5-D)") (class "Default")
      (node (ref "Q5") (pin "3") (pinfunction "D_3") (pintype "passive"))
      (node (ref "R55") (pin "2") (pinfunction "2_2") (pintype "passive"))
      (node (ref "R80") (pin "1") (pinfunction "1_1") (pintype "passive"))
    )
    (net (code "134") (name "Net-(Q5-G)") (class "Default")
      (node (ref "Q5") (pin "1") (pinfunction "G_1") (pintype "passive"))
      (node (ref "R10") (pin "2") (pinfunction "2_2") (pintype "passive"))
    )
    (net (code "135") (name "Net-(Q6-D)") (class "Default")
      (node (ref "Q6") (pin "3") (pinfunction "D_3") (pintype "passive"))
      (node (ref "R56") (pin "2") (pinfunction "2_2") (pintype "passive"))
      (node (ref "R81") (pin "1") (pinfunction "1_1") (pintype "passive"))
    )
    (net (code "136") (name "Net-(Q6-G)") (class "Default")
      (node (ref "Q6") (pin "1") (pinfunction "G_1") (pintype "passive"))
      (node (ref "R12") (pin "2") (pinfunction "2_2") (pintype "passive"))
    )
    (net (code "137") (name "Net-(Q7-D)") (class "Default")
      (node (ref "Q7") (pin "3") (pinfunction "D_3") (pintype "passive"))
      (node (ref "R57") (pin "2") (pinfunction "2_2") (pintype "passive"))
      (node (ref "R82") (pin "1") (pinfunction "1_1") (pintype "passive"))
    )
    (net (code "138") (name "Net-(Q7-G)") (class "Default")
      (node (ref "Q7") (pin "1") (pinfunction "G_1") (pintype "passive"))
      (node (ref "R14") (pin "2") (pinfunction "2_2") (pintype "passive"))
    )
    (net (code "139") (name "Net-(Q8-D)") (class "Default")
      (node (ref "Q8") (pin "3") (pinfunction "D_3") (pintype "passive"))
      (node (ref "R58") (pin "2") (pinfunction "2_2") (pintype "passive"))
      (node (ref "R83") (pin "1") (pinfunction "1_1") (pintype "passive"))
    )
    (net (code "140") (name "Net-(Q8-G)") (class "Default")
      (node (ref "Q8") (pin "1") (pinfunction "G_1") (pintype "passive"))
      (node (ref "R16") (pin "2") (pinfunction "2_2") (pintype "passive"))
    )
    (net (code "141") (name "Net-(Q9-D)") (class "Default")
      (node (ref "Q9") (pin "3") (pinfunction "D_3") (pintype "passive"))
      (node (ref "R59") (pin "2") (pinfunction "2_2") (pintype "passive"))
      (node (ref "R84") (pin "1") (pinfunction "1_1") (pintype "passive"))
    )
    (net (code "142") (name "Net-(Q9-G)") (class "Default")
      (node (ref "Q9") (pin "1") (pinfunction "G_1") (pintype "passive"))
      (node (ref "R18") (pin "2") (pinfunction "2_2") (pintype "passive"))
    )
    (net (code "143") (name "Net-(Q10-D)") (class "Default")
      (node (ref "Q10") (pin "3") (pinfunction "D_3") (pintype "passive"))
      (node (ref "R60") (pin "2") (pinfunction "2_2") (pintype "passive"))
      (node (ref "R85") (pin "1") (pinfunction "1_1") (pintype "passive"))
    )
    (net (code "144") (name "Net-(Q10-G)") (class "Default")
      (node (ref "Q10") (pin "1") (pinfunction "G_1") (pintype "passive"))
      (node (ref "R20") (pin "2") (pinfunction "2_2") (pintype "passive"))
    )
    (net (code "145") (name "Net-(Q11-D)") (class "Default")
      (node (ref "Q11") (pin "3") (pinfunction "D_3") (pintype "passive"))
      (node (ref "R61") (pin "2") (pinfunction "2_2") (pintype "passive"))
      (node (ref "R86") (pin "1") (pinfunction "1_1") (pintype "passive"))
    )
    (net (code "146") (name "Net-(Q11-G)") (class "Default")
      (node (ref "Q11") (pin "1") (pinfunction "G_1") (pintype "passive"))
      (node (ref "R22") (pin "2") (pinfunction "2_2") (pintype "passive"))
    )
    (net (code "147") (name "Net-(Q12-D)") (class "Default")
      (node (ref "Q12") (pin "3") (pinfunction "D_3") (pintype "passive"))
      (node (ref "R62") (pin "2") (pinfunction "2_2") (pintype "passive"))
      (node (ref "R87") (pin "1") (pinfunction "1_1") (pintype "passive"))
    )
    (net (code "148") (name "Net-(Q12-G)") (class "Default")
      (node (ref "Q12") (pin "1") (pinfunction "G_1") (pintype "passive"))
      (node (ref "R24") (pin "2") (pinfunction "2_2") (pintype "passive"))
    )
    (net (code "149") (name "Net-(Q13-D)") (class "Default")
      (node (ref "Q13") (pin "3") (pinfunction "D_3") (pintype "passive"))
      (node (ref "R64") (pin "2") (pinfunction "2_2") (pintype "passive"))
      (node (ref "R88") (pin "1") (pinfunction "1_1") (pintype "passive"))
    )
    (net (code "150") (name "Net-(Q13-G)") (class "Default")
      (node (ref "Q13") (pin "1") (pinfunction "G_1") (pintype "passive"))
      (node (ref "R26") (pin "2") (pinfunction "2_2") (pintype "passive"))
    )
    (net (code "151") (name "Net-(Q14-D)") (class "Default")
      (node (ref "Q14") (pin "3") (pinfunction "D_3") (pintype "passive"))
      (node (ref "R65") (pin "2") (pinfunction "2_2") (pintype "passive"))
      (node (ref "R89") (pin "1") (pinfunction "1_1") (pintype "passive"))
    )
    (net (code "152") (name "Net-(Q14-G)") (class "Default")
      (node (ref "Q14") (pin "1") (pinfunction "G_1") (pintype "passive"))
      (node (ref "R28") (pin "2") (pinfunction "2_2") (pintype "passive"))
    )
    (net (code "153") (name "Net-(Q15-D)") (class "Default")
      (node (ref "Q15") (pin "3") (pinfunction "D_3") (pintype "passive"))
      (node (ref "R66") (pin "2") (pinfunction "2_2") (pintype "passive"))
      (node (ref "R90") (pin "1") (pinfunction "1_1") (pintype "passive"))
    )
    (net (code "154") (name "Net-(Q15-G)") (class "Default")
      (node (ref "Q15") (pin "1") (pinfunction "G_1") (pintype "passive"))
      (node (ref "R30") (pin "2") (pinfunction "2_2") (pintype "passive"))
    )
    (net (code "155") (name "Net-(Q16-D)") (class "Default")
      (node (ref "Q16") (pin "3") (pinfunction "D_3") (pintype "passive"))
      (node (ref "R67") (pin "2") (pinfunction "2_2") (pintype "passive"))
      (node (ref "R91") (pin "1") (pinfunction "1_1") (pintype "passive"))
    )
    (net (code "156") (name "Net-(Q16-G)") (class "Default")
      (node (ref "Q16") (pin "1") (pinfunction "G_1") (pintype "passive"))
      (node (ref "R32") (pin "2") (pinfunction "2_2") (pintype "passive"))
    )
    (net (code "157") (name "Net-(Q17-D)") (class "Default")
      (node (ref "Q17") (pin "3") (pinfunction "D_3") (pintype "passive"))
      (node (ref "R68") (pin "2") (pinfunction "2_2") (pintype "passive"))
      (node (ref "R92") (pin "1") (pinfunction "1_1") (pintype "passive"))
    )
    (net (code "158") (name "Net-(Q17-G)") (class "Default")
      (node (ref "Q17") (pin "1") (pinfunction "G_1") (pintype "passive"))
      (node (ref "R34") (pin "2") (pinfunction "2_2") (pintype "passive"))
    )
    (net (code "159") (name "Net-(Q18-D)") (class "Default")
      (node (ref "Q18") (pin "3") (pinfunction "D_3") (pintype "passive"))
      (node (ref "R69") (pin "2") (pinfunction "2_2") (pintype "passive"))
      (node (ref "R93") (pin "1") (pinfunction "1_1") (pintype "passive"))
    )
    (net (code "160") (name "Net-(Q18-G)") (class "Default")
      (node (ref "Q18") (pin "1") (pinfunction "G_1") (pintype "passive"))
      (node (ref "R36") (pin "2") (pinfunction "2_2") (pintype "passive"))
    )
    (net (code "161") (name "Net-(Q19-D)") (class "Default")
      (node (ref "Q19") (pin "3") (pinfunction "D_3") (pintype "passive"))
      (node (ref "R70") (pin "2") (pinfunction "2_2") (pintype "passive"))
      (node (ref "R94") (pin "1") (pinfunction "1_1") (pintype "passive"))
    )
    (net (code "162") (name "Net-(Q19-G)") (class "Default")
      (node (ref "Q19") (pin "1") (pinfunction "G_1") (pintype "passive"))
      (node (ref "R38") (pin "2") (pinfunction "2_2") (pintype "passive"))
    )
    (net (code "163") (name "Net-(Q20-D)") (class "Default")
      (node (ref "Q20") (pin "3") (pinfunction "D_3") (pintype "passive"))
      (node (ref "R71") (pin "2") (pinfunction "2_2") (pintype "passive"))
      (node (ref "R95") (pin "1") (pinfunction "1_1") (pintype "passive"))
    )
    (net (code "164") (name "Net-(Q20-G)") (class "Default")
      (node (ref "Q20") (pin "1") (pinfunction "G_1") (pintype "passive"))
      (node (ref "R40") (pin "2") (pinfunction "2_2") (pintype "passive"))
    )
    (net (code "165") (name "Net-(Q21-D)") (class "Default")
      (node (ref "Q21") (pin "3") (pinfunction "D_3") (pintype "passive"))
      (node (ref "R72") (pin "2") (pinfunction "2_2") (pintype "passive"))
      (node (ref "R96") (pin "1") (pinfunction "1_1") (pintype "passive"))
    )
    (net (code "166") (name "Net-(Q21-G)") (class "Default")
      (node (ref "Q21") (pin "1") (pinfunction "G_1") (pintype "passive"))
      (node (ref "R42") (pin "2") (pinfunction "2_2") (pintype "passive"))
    )
    (net (code "167") (name "Net-(Q22-D)") (class "Default")
      (node (ref "Q22") (pin "3") (pinfunction "D_3") (pintype "passive"))
      (node (ref "R73") (pin "2") (pinfunction "2_2") (pintype "passive"))
      (node (ref "R97") (pin "1") (pinfunction "1_1") (pintype "passive"))
    )
    (net (code "168") (name "Net-(Q22-G)") (class "Default")
      (node (ref "Q22") (pin "1") (pinfunction "G_1") (pintype "passive"))
      (node (ref "R44") (pin "2") (pinfunction "2_2") (pintype "passive"))
    )
    (net (code "169") (name "Net-(Q23-D)") (class "Default")
      (node (ref "Q23") (pin "3") (pinfunction "D_3") (pintype "passive"))
      (node (ref "R74") (pin "2") (pinfunction "2_2") (pintype "passive"))
      (node (ref "R98") (pin "1") (pinfunction "1_1") (pintype "passive"))
    )
    (net (code "170") (name "Net-(Q23-G)") (class "Default")
      (node (ref "Q23") (pin "1") (pinfunction "G_1") (pintype "passive"))
      (node (ref "R46") (pin "2") (pinfunction "2_2") (pintype "passive"))
    )
    (net (code "171") (name "Net-(Q24-D)") (class "Default")
      (node (ref "Q24") (pin "3") (pinfunction "D_3") (pintype "passive"))
      (node (ref "R75") (pin "2") (pinfunction "2_2") (pintype "passive"))
      (node (ref "R99") (pin "1") (pinfunction "1_1") (pintype "passive"))
    )
    (net (code "172") (name "Net-(Q24-G)") (class "Default")
      (node (ref "Q24") (pin "1") (pinfunction "G_1") (pintype "passive"))
      (node (ref "R48") (pin "2") (pinfunction "2_2") (pintype "passive"))
    )
    (net (code "173") (name "Net-(Q25-B)") (class "Default")
      (node (ref "Q25") (pin "1") (pinfunction "B_1") (pintype "passive"))
      (node (ref "U2") (pin "38") (pinfunction "DRIVE_38") (pintype "passive"))
    )
    (net (code "174") (name "Net-(Q25-C)") (class "Default")
      (node (ref "C69") (pin "1") (pinfunction "1_1") (pintype "passive"))
      (node (ref "D49") (pin "1") (pinfunction "1_1") (pintype "passive"))
      (node (ref "JP3") (pin "2") (pinfunction "2_2") (pintype "passive"))
      (node (ref "JP3") (pin "3") (pinfunction "3_3") (pintype "passive"))
      (node (ref "Q25") (pin "3") (pinfunction "C_3") (pintype "passive"))
    )
    (net (code "175") (name "Net-(Q25-E)") (class "Default")
      (node (ref "C67") (pin "1") (pinfunction "1_1") (pintype "passive"))
      (node (ref "JP1") (pin "1") (pinfunction "1_1") (pintype "passive"))
      (node (ref "Q25") (pin "2") (pinfunction "E_2") (pintype "passive"))
      (node (ref "U2") (pin "37") (pinfunction "VREG_37") (pintype "passive"))
      (node (ref "U2") (pin "40") (pinfunction "ISOMD_40") (pintype "passive"))
    )
    (net (code "176") (name "Net-(Q26-B)") (class "Default")
      (node (ref "Q26") (pin "1") (pinfunction "B_1") (pintype "passive"))
      (node (ref "U1") (pin "38") (pinfunction "DRIVE_38") (pintype "passive"))
    )
    (net (code "177") (name "Net-(Q26-C)") (class "Default")
      (node (ref "C70") (pin "1") (pinfunction "1_1") (pintype "passive"))
      (node (ref "D50") (pin "1") (pinfunction "1_1") (pintype "passive"))
      (node (ref "JP4") (pin "2") (pinfunction "2_2") (pintype "passive"))
      (node (ref "JP4") (pin "3") (pinfunction "3_3") (pintype "passive"))
      (node (ref "Q26") (pin "3") (pinfunction "C_3") (pintype "passive"))
    )
    (net (code "178") (name "Net-(T1-CMT_2)") (class "Default")
      (node (ref "C76") (pin "1") (pinfunction "1_1") (pintype "passive"))
      (node (ref "T1") (pin "15") (pinfunction "CMT_2_15") (pintype "passive"))
    )
    (net (code "179") (name "Net-(T1-TCT)") (class "Default")
      (node (ref "C103") (pin "1") (pinfunction "1_1") (pintype "passive"))
      (node (ref "T1") (pin "2") (pinfunction "TCT_2") (pintype "passive"))
    )
    (net (code "180") (name "Net-(T2-CMT_2)") (class "Default")
      (node (ref "C75") (pin "1") (pinfunction "1_1") (pintype "passive"))
      (node (ref "T2") (pin "15") (pinfunction "CMT_2_15") (pintype "passive"))
    )
    (net (code "181") (name "Net-(T2-TCT)") (class "Default")
      (node (ref "C102") (pin "1") (pinfunction "1_1") (pintype "passive"))
      (node (ref "T2") (pin "2") (pinfunction "TCT_2") (pintype "passive"))
    )
    (net (code "182") (name "Net-(U1-DTEN)") (class "Default")
      (node (ref "JP2") (pin "2") (pinfunction "2_2") (pintype "passive"))
      (node (ref "U1") (pin "36") (pinfunction "DTEN_36") (pintype "passive"))
    )
    (net (code "183") (name "Net-(U1-GPIO1)") (class "Default")
      (node (ref "C61") (pin "1") (pinfunction "1_1") (pintype "passive"))
      (node (ref "J1") (pin "2") (pinfunction "2_2") (pintype "passive"))
      (node (ref "R111") (pin "1") (pinfunction "1_1") (pintype "passive"))
      (node (ref "U1") (pin "27") (pinfunction "GPIO1_27") (pintype "passive"))
    )
    (net (code "184") (name "Net-(U1-GPIO2)") (class "Default")
      (node (ref "C59") (pin "1") (pinfunction "1_1") (pintype "passive"))
      (node (ref "J1") (pin "4") (pinfunction "4_4") (pintype "passive"))
      (node (ref "R109") (pin "1") (pinfunction "1_1") (pintype "passive"))
      (node (ref "U1") (pin "28") (pinfunction "GPIO2_28") (pintype "passive"))
    )
    (net (code "185") (name "Net-(U1-GPIO3)") (class "Default")
      (node (ref "C57") (pin "1") (pinfunction "1_1") (pintype "passive"))
      (node (ref "J1") (pin "6") (pinfunction "6_6") (pintype "passive"))
      (node (ref "R107") (pin "1") (pinfunction "1_1") (pintype "passive"))
      (node (ref "U1") (pin "29") (pinfunction "GPIO3_29") (pintype "passive"))
    )
    (net (code "186") (name "Net-(U1-GPIO4)") (class "Default")
      (node (ref "C55") (pin "1") (pinfunction "1_1") (pintype "passive"))
      (node (ref "J1") (pin "8") (pinfunction "8_8") (pintype "passive"))
      (node (ref "R105") (pin "1") (pinfunction "1_1") (pintype "passive"))
      (node (ref "U1") (pin "32") (pinfunction "GPIO4_32") (pintype "passive"))
    )
    (net (code "187") (name "Net-(U1-GPIO5)") (class "Default")
      (node (ref "C53") (pin "1") (pinfunction "1_1") (pintype "passive"))
      (node (ref "J1") (pin "10") (pinfunction "10_10") (pintype "passive"))
      (node (ref "R103") (pin "1") (pinfunction "1_1") (pintype "passive"))
      (node (ref "U1") (pin "33") (pinfunction "GPIO5_33") (pintype "passive"))
    )
    (net (code "188") (name "Net-(U1-IBIAS)") (class "Default")
      (node (ref "R116") (pin "1") (pinfunction "1_1") (pintype "passive"))
      (node (ref "U1") (pin "45") (pinfunction "IBIAS_45") (pintype "passive"))
    )
    (net (code "189") (name "Net-(U1-ICMP)") (class "Default")
      (node (ref "R116") (pin "2") (pinfunction "2_2") (pintype "passive"))
      (node (ref "R118") (pin "1") (pinfunction "1_1") (pintype "passive"))
      (node (ref "U1") (pin "46") (pinfunction "ICMP_46") (pintype "passive"))
    )
    (net (code "190") (name "Net-(U1-V+)") (class "Default")
      (node (ref "C51") (pin "1") (pinfunction "1_1") (pintype "passive"))
      (node (ref "R101") (pin "1") (pinfunction "1_1") (pintype "passive"))
      (node (ref "U1") (pin "1") (pinfunction "V+_1") (pintype "passive"))
    )
    (net (code "191") (name "Net-(U1-VREF1)") (class "Default")
      (node (ref "C66") (pin "1") (pinfunction "1_1") (pintype "passive"))
      (node (ref "U1") (pin "35") (pinfunction "VREF1_35") (pintype "passive"))
    )
    (net (code "192") (name "Net-(U1-VREF2)") (class "Default")
      (node (ref "C63") (pin "1") (pinfunction "1_1") (pintype "passive"))
      (node (ref "R103") (pin "2") (pinfunction "2_2") (pintype "passive"))
      (node (ref "R105") (pin "2") (pinfunction "2_2") (pintype "passive"))
      (node (ref "R107") (pin "2") (pinfunction "2_2") (pintype "passive"))
      (node (ref "R109") (pin "2") (pinfunction "2_2") (pintype "passive"))
      (node (ref "R111") (pin "2") (pinfunction "2_2") (pintype "passive"))
      (node (ref "U1") (pin "34") (pinfunction "VREF2_34") (pintype "passive"))
    )
    (net (code "193") (name "Net-(U2-DTEN)") (class "Default")
      (node (ref "JP1") (pin "2") (pinfunction "2_2") (pintype "passive"))
      (node (ref "U2") (pin "36") (pinfunction "DTEN_36") (pintype "passive"))
    )
    (net (code "194") (name "Net-(U2-GPIO1)") (class "Default")
      (node (ref "C60") (pin "1") (pinfunction "1_1") (pintype "passive"))
      (node (ref "J2") (pin "2") (pinfunction "2_2") (pintype "passive"))
      (node (ref "R110") (pin "1") (pinfunction "1_1") (pintype "passive"))
      (node (ref "U2") (pin "27") (pinfunction "GPIO1_27") (pintype "passive"))
    )
    (net (code "195") (name "Net-(U2-GPIO2)") (class "Default")
      (node (ref "C58") (pin "1") (pinfunction "1_1") (pintype "passive"))
      (node (ref "J2") (pin "4") (pinfunction "4_4") (pintype "passive"))
      (node (ref "R108") (pin "1") (pinfunction "1_1") (pintype "passive"))
      (node (ref "U2") (pin "28") (pinfunction "GPIO2_28") (pintype "passive"))
    )
    (net (code "196") (name "Net-(U2-GPIO3)") (class "Default")
      (node (ref "C56") (pin "1") (pinfunction "1_1") (pintype "passive"))
      (node (ref "J2") (pin "6") (pinfunction "6_6") (pintype "passive"))
      (node (ref "R106") (pin "1") (pinfunction "1_1") (pintype "passive"))
      (node (ref "U2") (pin "29") (pinfunction "GPIO3_29") (pintype "passive"))
    )
    (net (code "197") (name "Net-(U2-GPIO4)") (class "Default")
      (node (ref "C54") (pin "1") (pinfunction "1_1") (pintype "passive"))
      (node (ref "J2") (pin "8") (pinfunction "8_8") (pintype "passive"))
      (node (ref "R104") (pin "1") (pinfunction "1_1") (pintype "passive"))
      (node (ref "U2") (pin "32") (pinfunction "GPIO4_32") (pintype "passive"))
    )
    (net (code "198") (name "Net-(U2-GPIO5)") (class "Default")
      (node (ref "C52") (pin "1") (pinfunction "1_1") (pintype "passive"))
      (node (ref "J2") (pin "10") (pinfunction "10_10") (pintype "passive"))
      (node (ref "R102") (pin "1") (pinfunction "1_1") (pintype "passive"))
      (node (ref "U2") (pin "33") (pinfunction "GPIO5_33") (pintype "passive"))
    )
    (net (code "199") (name "Net-(U2-IBIAS)") (class "Default")
      (node (ref "R113") (pin "1") (pinfunction "1_1") (pintype "passive"))
      (node (ref "U2") (pin "45") (pinfunction "IBIAS_45") (pintype "passive"))
    )
    (net (code "200") (name "Net-(U2-ICMP)") (class "Default")
      (node (ref "R113") (pin "2") (pinfunction "2_2") (pintype "passive"))
      (node (ref "R117") (pin "1") (pinfunction "1_1") (pintype "passive"))
      (node (ref "U2") (pin "46") (pinfunction "ICMP_46") (pintype "passive"))
    )
    (net (code "201") (name "Net-(U2-V+)") (class "Default")
      (node (ref "C50") (pin "1") (pinfunction "1_1") (pintype "passive"))
      (node (ref "R100") (pin "1") (pinfunction "1_1") (pintype "passive"))
      (node (ref "U2") (pin "1") (pinfunction "V+_1") (pintype "passive"))
    )
    (net (code "202") (name "Net-(U2-VREF1)") (class "Default")
      (node (ref "C64") (pin "1") (pinfunction "1_1") (pintype "passive"))
      (node (ref "U2") (pin "35") (pinfunction "VREF1_35") (pintype "passive"))
    )
    (net (code "203") (name "Net-(U2-VREF2)") (class "Default")
      (node (ref "C62") (pin "1") (pinfunction "1_1") (pintype "passive"))
      (node (ref "R102") (pin "2") (pinfunction "2_2") (pintype "passive"))
      (node (ref "R104") (pin "2") (pinfunction "2_2") (pintype "passive"))
      (node (ref "R106") (pin "2") (pinfunction "2_2") (pintype "passive"))
      (node (ref "R108") (pin "2") (pinfunction "2_2") (pintype "passive"))
      (node (ref "R110") (pin "2") (pinfunction "2_2") (pintype "passive"))
      (node (ref "U2") (pin "34") (pinfunction "VREF2_34") (pintype "passive"))
    )
    (net (code "204") (name "S1") (class "Default")
      (node (ref "R2") (pin "1") (pinfunction "1_1") (pintype "passive"))
      (node (ref "U1") (pin "25") (pinfunction "S1_25") (pintype "passive"))
    )
    (net (code "205") (name "S2") (class "Default")
      (node (ref "R4") (pin "1") (pinfunction "1_1") (pintype "passive"))
      (node (ref "U1") (pin "23") (pinfunction "S2_23") (pintype "passive"))
    )
    (net (code "206") (name "S3") (class "Default")
      (node (ref "R6") (pin "1") (pinfunction "1_1") (pintype "passive"))
      (node (ref "U1") (pin "21") (pinfunction "S3_21") (pintype "passive"))
    )
    (net (code "207") (name "S4") (class "Default")
      (node (ref "R8") (pin "1") (pinfunction "1_1") (pintype "passive"))
      (node (ref "U1") (pin "19") (pinfunction "S4_19") (pintype "passive"))
    )
    (net (code "208") (name "S5") (class "Default")
      (node (ref "R10") (pin "1") (pinfunction "1_1") (pintype "passive"))
      (node (ref "U1") (pin "17") (pinfunction "S5_17") (pintype "passive"))
    )
    (net (code "209") (name "S6") (class "Default")
      (node (ref "R12") (pin "1") (pinfunction "1_1") (pintype "passive"))
      (node (ref "U1") (pin "15") (pinfunction "S6_15") (pintype "passive"))
    )
    (net (code "210") (name "S7") (class "Default")
      (node (ref "R14") (pin "1") (pinfunction "1_1") (pintype "passive"))
      (node (ref "U1") (pin "13") (pinfunction "S7_13") (pintype "passive"))
    )
    (net (code "211") (name "S8") (class "Default")
      (node (ref "R16") (pin "1") (pinfunction "1_1") (pintype "passive"))
      (node (ref "U1") (pin "11") (pinfunction "S8_11") (pintype "passive"))
    )
    (net (code "212") (name "S9") (class "Default")
      (node (ref "R18") (pin "1") (pinfunction "1_1") (pintype "passive"))
      (node (ref "U1") (pin "9") (pinfunction "S9_9") (pintype "passive"))
    )
    (net (code "213") (name "S10") (class "Default")
      (node (ref "R20") (pin "1") (pinfunction "1_1") (pintype "passive"))
      (node (ref "U1") (pin "7") (pinfunction "S10_7") (pintype "passive"))
    )
    (net (code "214") (name "S11") (class "Default")
      (node (ref "R22") (pin "1") (pinfunction "1_1") (pintype "passive"))
      (node (ref "U1") (pin "5") (pinfunction "S11_5") (pintype "passive"))
    )
    (net (code "215") (name "S12") (class "Default")
      (node (ref "R24") (pin "1") (pinfunction "1_1") (pintype "passive"))
      (node (ref "U1") (pin "3") (pinfunction "S12_3") (pintype "passive"))
    )
    (net (code "216") (name "S13") (class "Default")
      (node (ref "R26") (pin "1") (pinfunction "1_1") (pintype "passive"))
      (node (ref "U2") (pin "25") (pinfunction "S1_25") (pintype "passive"))
    )
    (net (code "217") (name "S14") (class "Default")
      (node (ref "R28") (pin "1") (pinfunction "1_1") (pintype "passive"))
      (node (ref "U2") (pin "23") (pinfunction "S2_23") (pintype "passive"))
    )
    (net (code "218") (name "S15") (class "Default")
      (node (ref "R30") (pin "1") (pinfunction "1_1") (pintype "passive"))
      (node (ref "U2") (pin "21") (pinfunction "S3_21") (pintype "passive"))
    )
    (net (code "219") (name "S16") (class "Default")
      (node (ref "R32") (pin "1") (pinfunction "1_1") (pintype "passive"))
      (node (ref "U2") (pin "19") (pinfunction "S4_19") (pintype "passive"))
    )
    (net (code "220") (name "S17") (class "Default")
      (node (ref "R34") (pin "1") (pinfunction "1_1") (pintype "passive"))
      (node (ref "U2") (pin "17") (pinfunction "S5_17") (pintype "passive"))
    )
    (net (code "221") (name "S18") (class "Default")
      (node (ref "R36") (pin "1") (pinfunction "1_1") (pintype "passive"))
      (node (ref "U2") (pin "15") (pinfunction "S6_15") (pintype "passive"))
    )
    (net (code "222") (name "S19") (class "Default")
      (node (ref "R38") (pin "1") (pinfunction "1_1") (pintype "passive"))
      (node (ref "U2") (pin "13") (pinfunction "S7_13") (pintype "passive"))
    )
    (net (code "223") (name "S20") (class "Default")
      (node (ref "R40") (pin "1") (pinfunction "1_1") (pintype "passive"))
      (node (ref "U2") (pin "11") (pinfunction "S8_11") (pintype "passive"))
    )
    (net (code "224") (name "S21") (class "Default")
      (node (ref "R42") (pin "1") (pinfunction "1_1") (pintype "passive"))
      (node (ref "U2") (pin "9") (pinfunction "S9_9") (pintype "passive"))
    )
    (net (code "225") (name "S22") (class "Default")
      (node (ref "R44") (pin "1") (pinfunction "1_1") (pintype "passive"))
      (node (ref "U2") (pin "7") (pinfunction "S10_7") (pintype "passive"))
    )
    (net (code "226") (name "S23") (class "Default")
      (node (ref "R46") (pin "1") (pinfunction "1_1") (pintype "passive"))
      (node (ref "U2") (pin "5") (pinfunction "S11_5") (pintype "passive"))
    )
    (net (code "227") (name "S24") (class "Default")
      (node (ref "R48") (pin "1") (pinfunction "1_1") (pintype "passive"))
      (node (ref "U2") (pin "3") (pinfunction "S12_3") (pintype "passive"))
    )
    (net (code "228") (name "unconnected-(J1-Pad11)") (class "Default")
      (node (ref "J1") (pin "11") (pinfunction "11_11") (pintype "passive"))
    )
    (net (code "229") (name "unconnected-(J1-Pad12)") (class "Default")
      (node (ref "J1") (pin "12") (pinfunction "12_12") (pintype "passive"))
    )
    (net (code "230") (name "unconnected-(J2-Pad11)") (class "Default")
      (node (ref "J2") (pin "11") (pinfunction "11_11") (pintype "passive"))
    )
    (net (code "231") (name "unconnected-(J2-Pad12)") (class "Default")
      (node (ref "J2") (pin "12") (pinfunction "12_12") (pintype "passive"))
    )
    (net (code "232") (name "unconnected-(J3-Pad3)") (class "Default")
      (node (ref "J3") (pin "3") (pinfunction "3_3") (pintype "passive"))
    )
    (net (code "233") (name "unconnected-(J3-Pad4)") (class "Default")
      (node (ref "J3") (pin "4") (pinfunction "4_4") (pintype "passive"))
    )
    (net (code "234") (name "unconnected-(J3-Pad5)") (class "Default")
      (node (ref "J3") (pin "5") (pinfunction "5_5") (pintype "passive"))
    )
    (net (code "235") (name "unconnected-(J3-Pad6)") (class "Default")
      (node (ref "J3") (pin "6") (pinfunction "6_6") (pintype "passive"))
    )
    (net (code "236") (name "unconnected-(J3-Pad7)") (class "Default")
      (node (ref "J3") (pin "7") (pinfunction "7_7") (pintype "passive"))
    )
    (net (code "237") (name "unconnected-(J3-Pad8)") (class "Default")
      (node (ref "J3") (pin "8") (pinfunction "8_8") (pintype "passive"))
    )
    (net (code "238") (name "unconnected-(J4-Pad3)") (class "Default")
      (node (ref "J4") (pin "3") (pinfunction "3_3") (pintype "passive"))
    )
    (net (code "239") (name "unconnected-(J4-Pad4)") (class "Default")
      (node (ref "J4") (pin "4") (pinfunction "4_4") (pintype "passive"))
    )
    (net (code "240") (name "unconnected-(J4-Pad5)") (class "Default")
      (node (ref "J4") (pin "5") (pinfunction "5_5") (pintype "passive"))
    )
    (net (code "241") (name "unconnected-(J4-Pad6)") (class "Default")
      (node (ref "J4") (pin "6") (pinfunction "6_6") (pintype "passive"))
    )
    (net (code "242") (name "unconnected-(J4-Pad7)") (class "Default")
      (node (ref "J4") (pin "7") (pinfunction "7_7") (pintype "passive"))
    )
    (net (code "243") (name "unconnected-(J4-Pad8)") (class "Default")
      (node (ref "J4") (pin "8") (pinfunction "8_8") (pintype "passive"))
    )
    (net (code "244") (name "unconnected-(P2-Pad1)") (class "Default")
      (node (ref "P2") (pin "1") (pinfunction "1_1") (pintype "passive"))
    )
    (net (code "245") (name "unconnected-(P2-Pad2)") (class "Default")
      (node (ref "P2") (pin "2") (pinfunction "2_2") (pintype "passive"))
    )
    (net (code "246") (name "unconnected-(P2-Pad3)") (class "Default")
      (node (ref "P2") (pin "3") (pinfunction "3_3") (pintype "passive"))
    )
    (net (code "247") (name "unconnected-(T1-CMT_1-Pad10)") (class "Default")
      (node (ref "T1") (pin "10") (pinfunction "CMT_1_10") (pintype "passive"))
    )
    (net (code "248") (name "unconnected-(T1-NC_1-Pad4)") (class "Default")
      (node (ref "T1") (pin "4") (pinfunction "NC_1_4") (pintype "passive"))
    )
    (net (code "249") (name "unconnected-(T1-NC_2-Pad5)") (class "Default")
      (node (ref "T1") (pin "5") (pinfunction "NC_2_5") (pintype "passive"))
    )
    (net (code "250") (name "unconnected-(T1-NC_3-Pad12)") (class "Default")
      (node (ref "T1") (pin "12") (pinfunction "NC_3_12") (pintype "passive"))
    )
    (net (code "251") (name "unconnected-(T1-NC_4-Pad13)") (class "Default")
      (node (ref "T1") (pin "13") (pinfunction "NC_4_13") (pintype "passive"))
    )
    (net (code "252") (name "unconnected-(T1-RCT-Pad7)") (class "Default")
      (node (ref "T1") (pin "7") (pinfunction "RCT_7") (pintype "passive"))
    )
    (net (code "253") (name "unconnected-(T1-RD+-Pad6)") (class "Default")
      (node (ref "T1") (pin "6") (pinfunction "RD+_6") (pintype "passive"))
    )
    (net (code "254") (name "unconnected-(T1-RD--Pad8)") (class "Default")
      (node (ref "T1") (pin "8") (pinfunction "RD-_8") (pintype "passive"))
    )
    (net (code "255") (name "unconnected-(T1-RX+-Pad11)") (class "Default")
      (node (ref "T1") (pin "11") (pinfunction "RX+_11") (pintype "passive"))
    )
    (net (code "256") (name "unconnected-(T1-RX--Pad9)") (class "Default")
      (node (ref "T1") (pin "9") (pinfunction "RX-_9") (pintype "passive"))
    )
    (net (code "257") (name "unconnected-(T2-CMT_1-Pad10)") (class "Default")
      (node (ref "T2") (pin "10") (pinfunction "CMT_1_10") (pintype "passive"))
    )
    (net (code "258") (name "unconnected-(T2-NC_1-Pad4)") (class "Default")
      (node (ref "T2") (pin "4") (pinfunction "NC_1_4") (pintype "passive"))
    )
    (net (code "259") (name "unconnected-(T2-NC_2-Pad5)") (class "Default")
      (node (ref "T2") (pin "5") (pinfunction "NC_2_5") (pintype "passive"))
    )
    (net (code "260") (name "unconnected-(T2-NC_3-Pad12)") (class "Default")
      (node (ref "T2") (pin "12") (pinfunction "NC_3_12") (pintype "passive"))
    )
    (net (code "261") (name "unconnected-(T2-NC_4-Pad13)") (class "Default")
      (node (ref "T2") (pin "13") (pinfunction "NC_4_13") (pintype "passive"))
    )
    (net (code "262") (name "unconnected-(T2-RCT-Pad7)") (class "Default")
      (node (ref "T2") (pin "7") (pinfunction "RCT_7") (pintype "passive"))
    )
    (net (code "263") (name "unconnected-(T2-RD+-Pad6)") (class "Default")
      (node (ref "T2") (pin "6") (pinfunction "RD+_6") (pintype "passive"))
    )
    (net (code "264") (name "unconnected-(T2-RD--Pad8)") (class "Default")
      (node (ref "T2") (pin "8") (pinfunction "RD-_8") (pintype "passive"))
    )
    (net (code "265") (name "unconnected-(T2-RX+-Pad11)") (class "Default")
      (node (ref "T2") (pin "11") (pinfunction "RX+_11") (pintype "passive"))
    )
    (net (code "266") (name "unconnected-(T2-RX--Pad9)") (class "Default")
      (node (ref "T2") (pin "9") (pinfunction "RX-_9") (pintype "passive"))
    )
    (net (code "267") (name "unconnected-(U1-SDI_(NC)*-Pad43)") (class "Default")
      (node (ref "U1") (pin "43") (pinfunction "SDI_(NC)*_43") (pintype "passive"))
    )
    (net (code "268") (name "unconnected-(U1-SDO_(NC)*-Pad44)") (class "Default")
      (node (ref "U1") (pin "44") (pinfunction "SDO_(NC)*_44") (pintype "passive"))
    )
    (net (code "269") (name "unconnected-(U1-WDT-Pad39)") (class "Default")
      (node (ref "U1") (pin "39") (pinfunction "WDT_39") (pintype "passive"))
    )
    (net (code "270") (name "unconnected-(U2-SDI_(NC)*-Pad43)") (class "Default")
      (node (ref "U2") (pin "43") (pinfunction "SDI_(NC)*_43") (pintype "passive"))
    )
    (net (code "271") (name "unconnected-(U2-SDO_(NC)*-Pad44)") (class "Default")
      (node (ref "U2") (pin "44") (pinfunction "SDO_(NC)*_44") (pintype "passive"))
    )
    (net (code "272") (name "unconnected-(U2-WDT-Pad39)") (class "Default")
      (node (ref "U2") (pin "39") (pinfunction "WDT_39") (pintype "passive"))
    )
  )
)
